# 100-677-01-00_BCB.net
KiCad netlist of a schematic drawn in Altium Designer
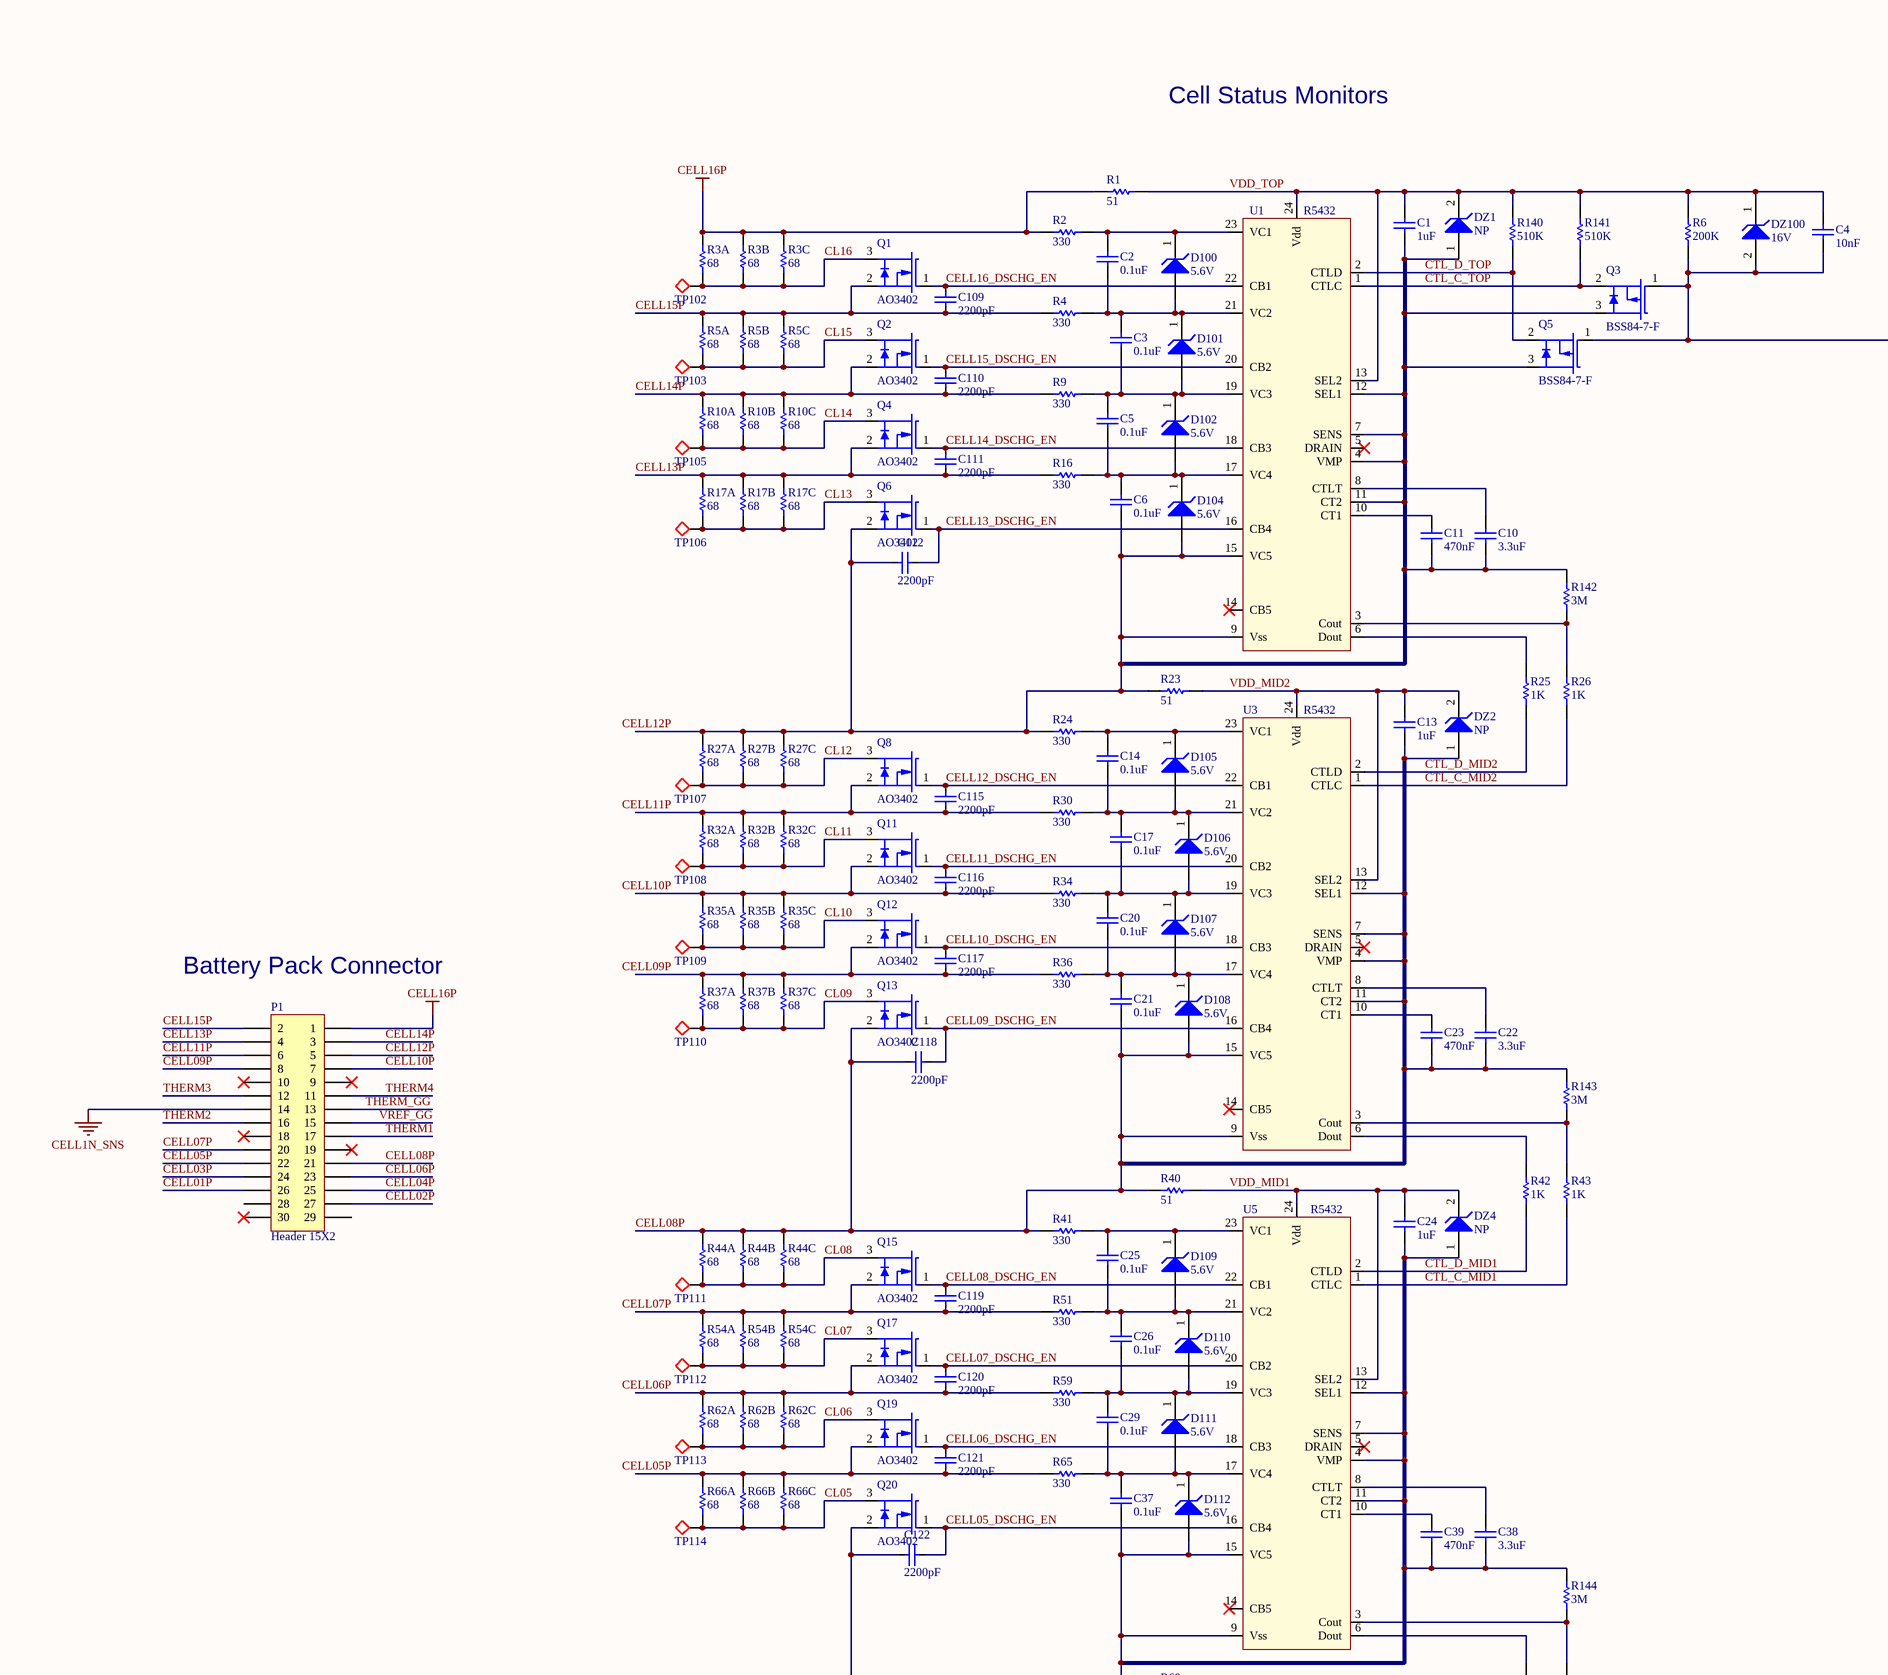
[diagram p0: 100-677-01-00 BCB.SchDoc, top left]
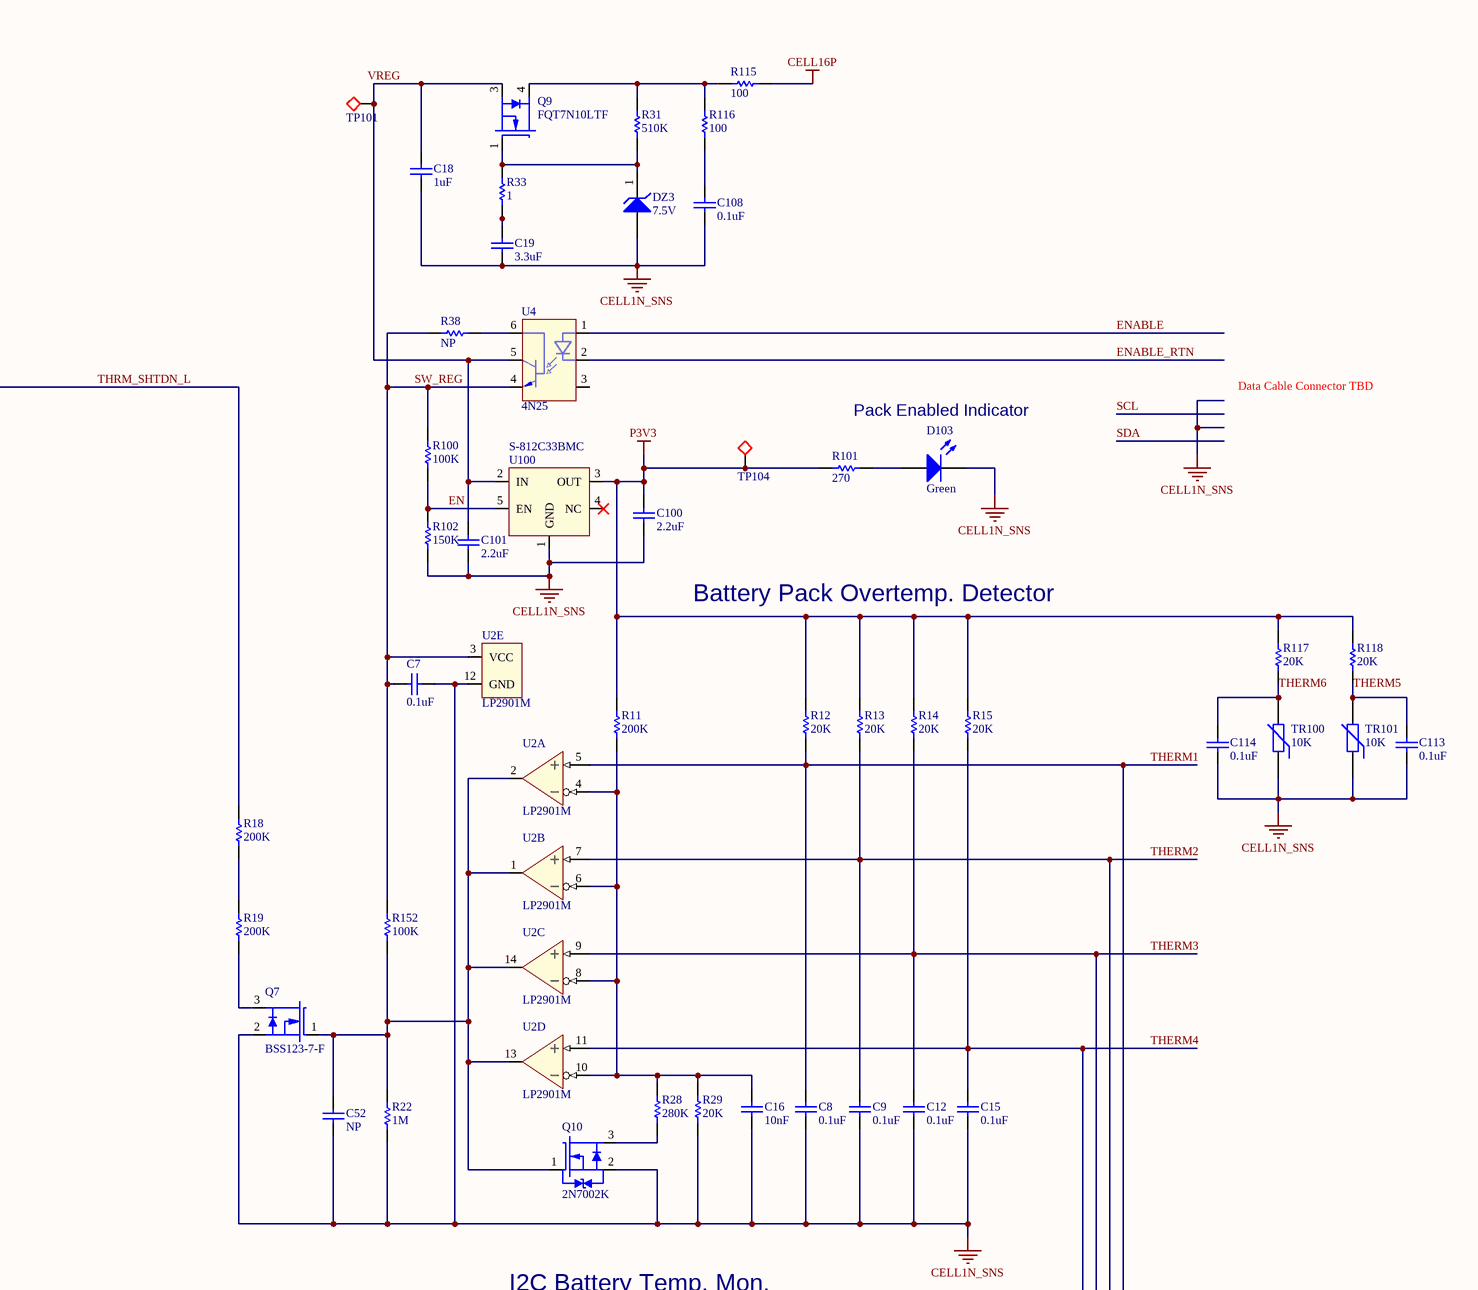
[diagram p1: 100-677-01-00 BCB.SchDoc, top middle]
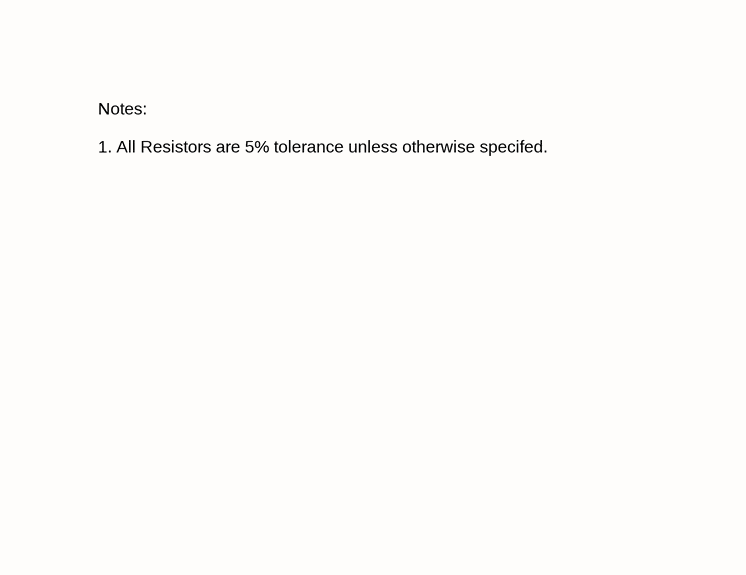
[diagram p2: 100-677-01-00 BCB.SchDoc, top right]
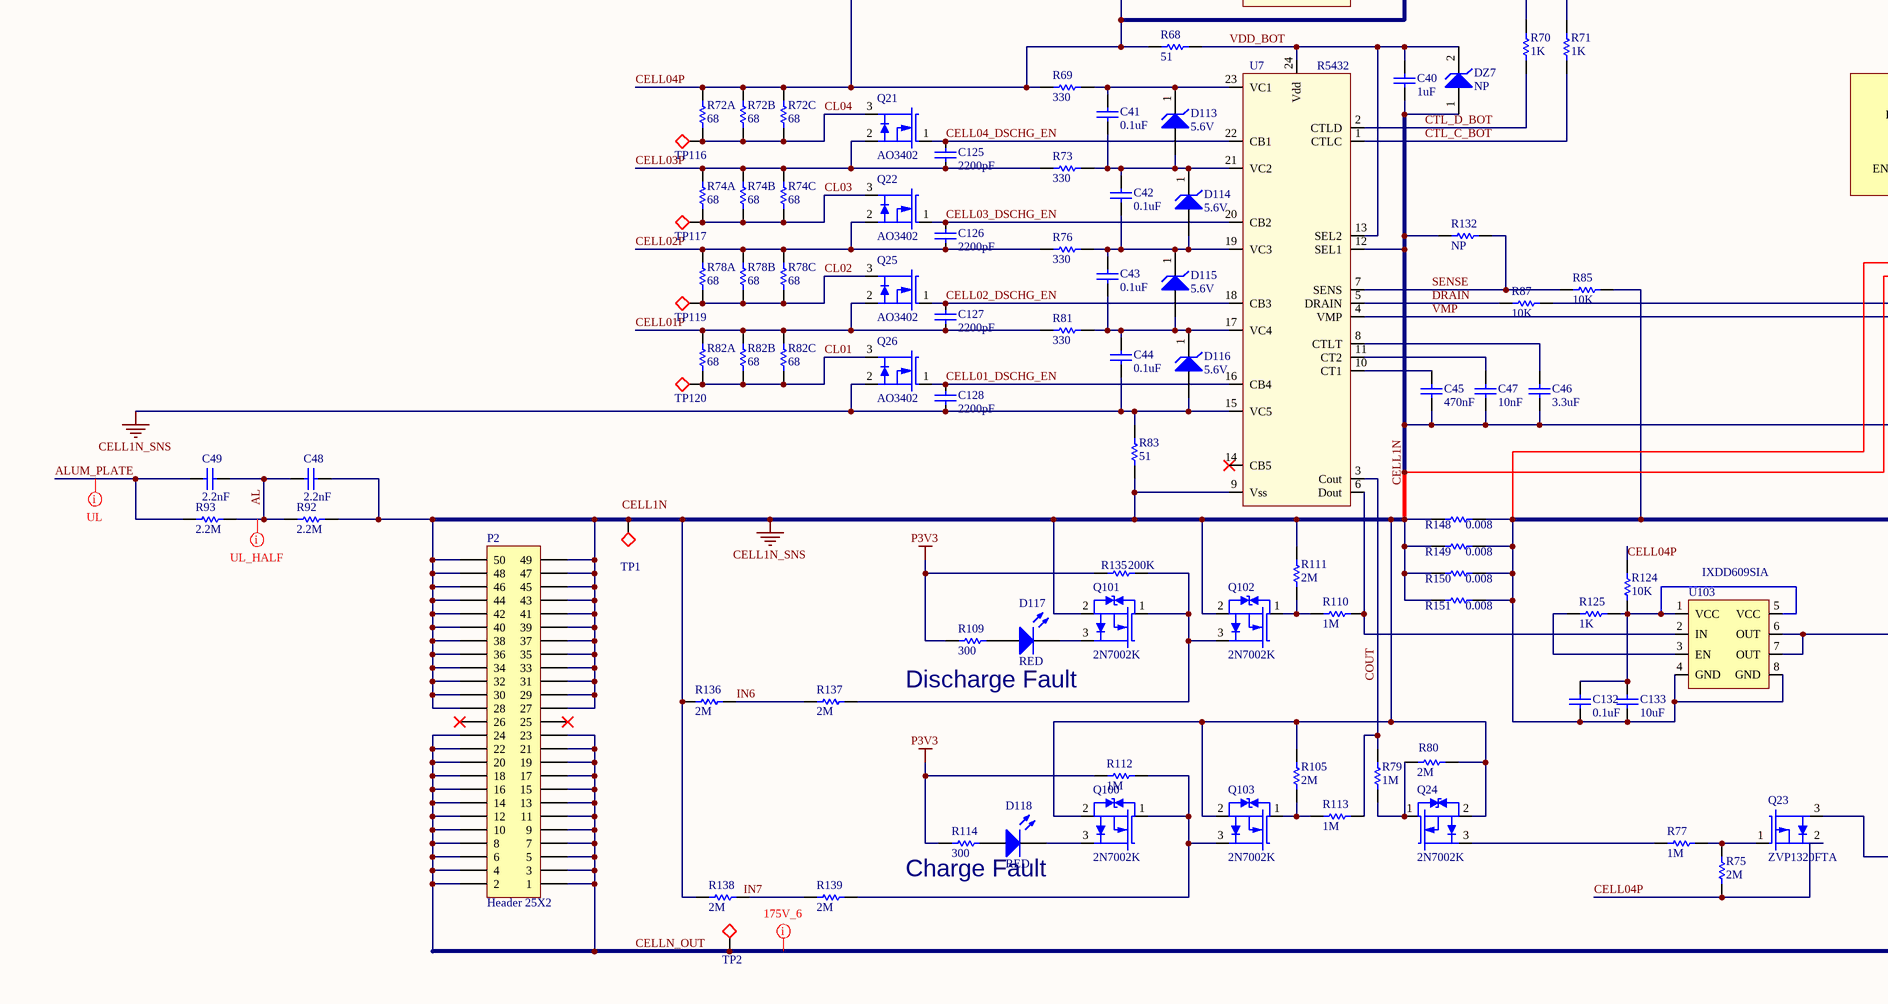
[diagram p3: 100-677-01-00 BCB.SchDoc, bottom left]
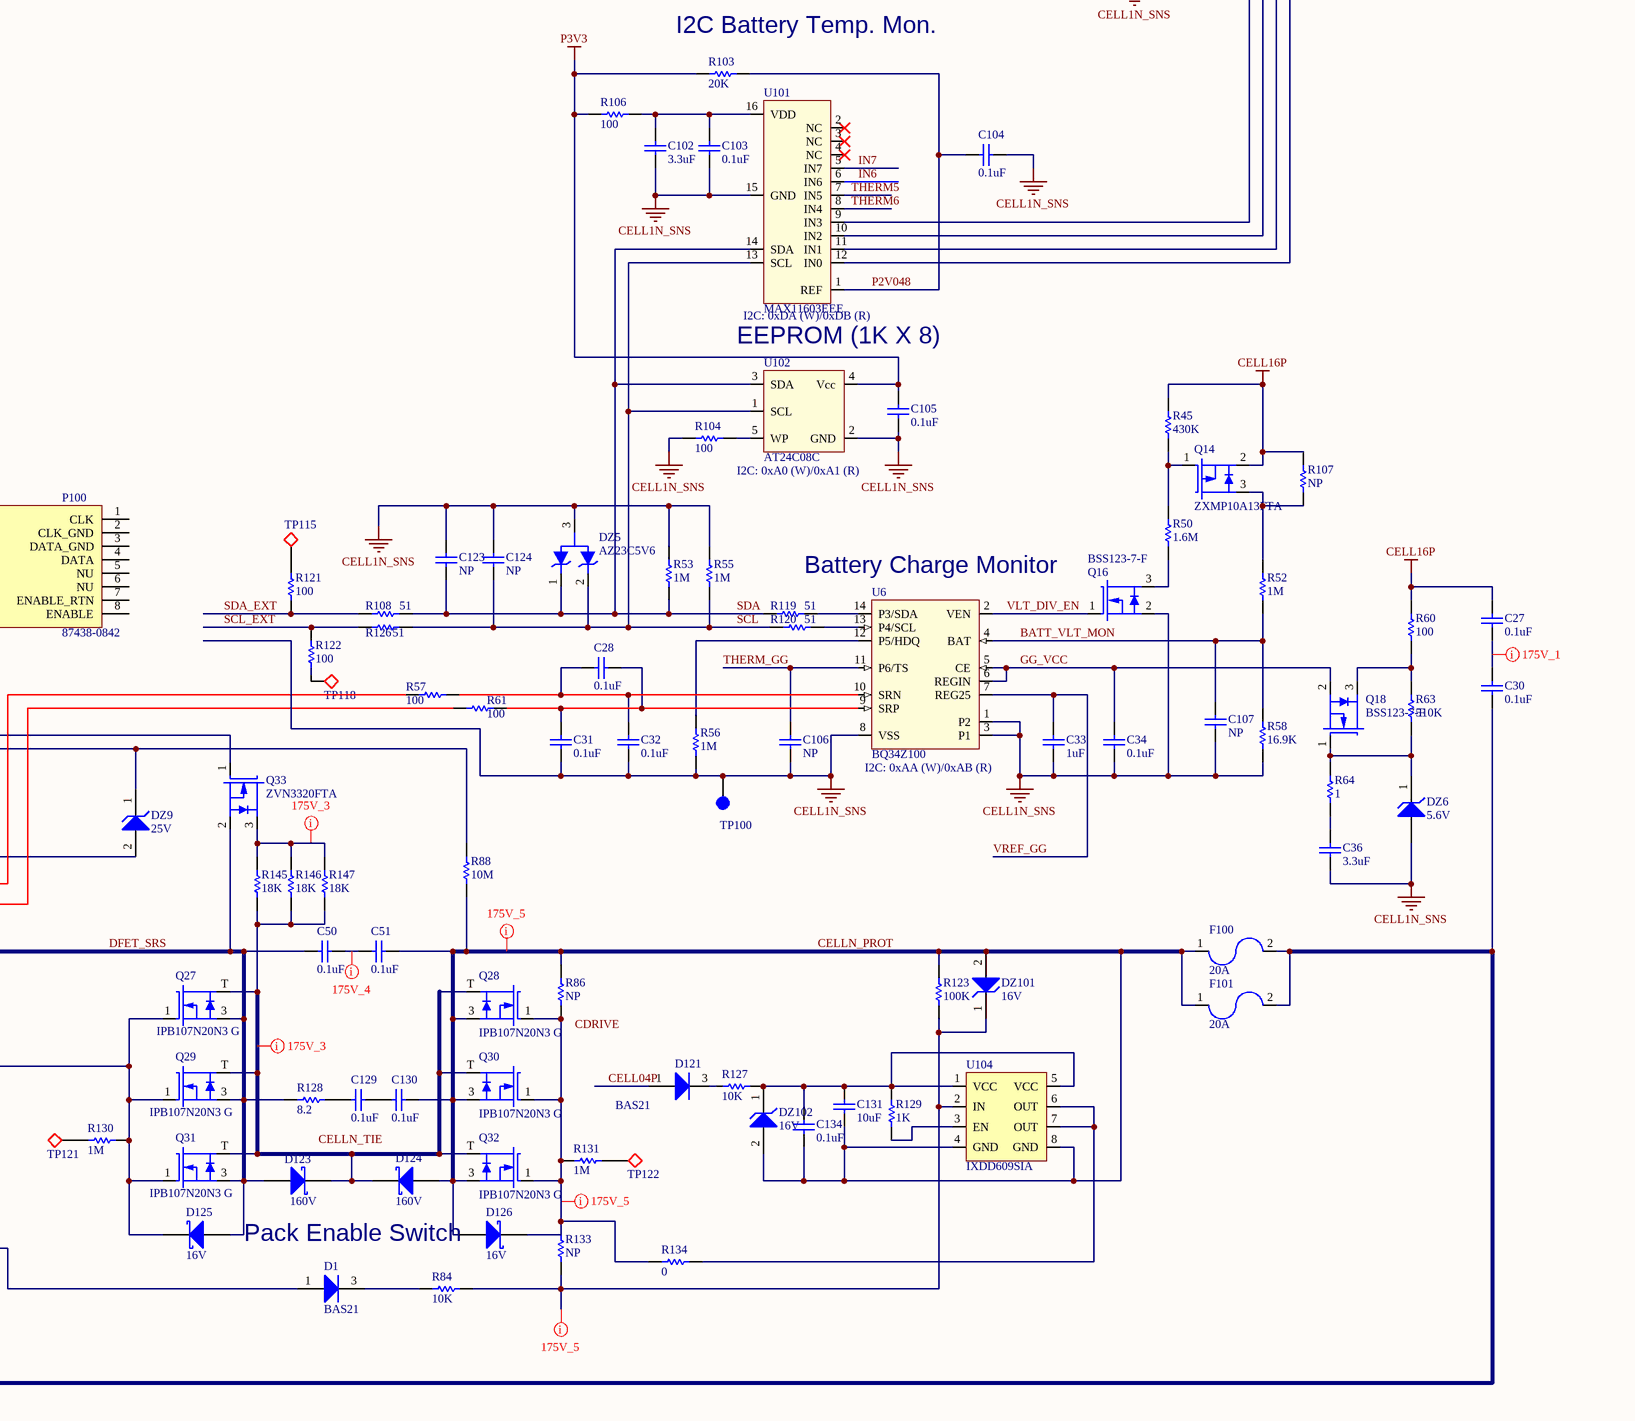
[diagram p4: 100-677-01-00 BCB.SchDoc, bottom middle]

(export (version "E")
  (design (tool "Eeschema 10.0.6"))
  (components
    (comp (ref "C1")
      (value "1uF")
      (footprint "6-0805_N")
      (description "CAP MLCC 1UF 25V X7R 10% SM0805 ROHS")
      (fields
        (field (name "MANUFACTURER") "TDK Corporation")
        (field (name "MANUFACTURER PART NUMBER") "C2012X7R1E105K125AB")
      )
      (libsource (lib "TenergyLibrary") (part "Cap 1uF 0805"))
    )
    (comp (ref "C2")
      (value "0.1uF")
      (footprint "1608[0603]")
      (description "CAP CER 0.1UF 25V 10% X7R 0603")
      (fields (field (name "TOLERANCE") "¡À10%"))
      (libsource (lib "TenergyLibrary") (part "Cap 0.1uF 0603"))
    )
    (comp (ref "C3")
      (value "0.1uF")
      (footprint "1608[0603]")
      (description "CAP CER 0.1UF 25V 10% X7R 0603")
      (fields (field (name "TOLERANCE") "¡À10%"))
      (libsource (lib "TenergyLibrary") (part "Cap 0.1uF 0603"))
    )
    (comp (ref "C4")
      (value "10nF")
      (footprint "1608[0603]")
      (description "CAP MLCC 10NF 25V X7R 10% SM0603 ROHS")
      (fields
        (field (name "MANUFACTURER") "TDK Corporation")
        (field (name "MANUFACTURER PART NUMBER") "C1608X7R1E103K080AA")
      )
      (libsource (lib "TenergyLibrary") (part "Cap 10nF 0603"))
    )
    (comp (ref "C5")
      (value "0.1uF")
      (footprint "1608[0603]")
      (description "CAP CER 0.1UF 25V 10% X7R 0603")
      (fields (field (name "TOLERANCE") "¡À10%"))
      (libsource (lib "TenergyLibrary") (part "Cap 0.1uF 0603"))
    )
    (comp (ref "C6")
      (value "0.1uF")
      (footprint "1608[0603]")
      (description "CAP CER 0.1UF 25V 10% X7R 0603")
      (fields (field (name "TOLERANCE") "¡À10%"))
      (libsource (lib "TenergyLibrary") (part "Cap 0.1uF 0603"))
    )
    (comp (ref "C7")
      (value "0.1uF")
      (footprint "1608[0603]")
      (description "CAP CER 0.1UF 25V 10% X7R 0603")
      (fields (field (name "TOLERANCE") "¡À10%"))
      (libsource (lib "TenergyLibrary") (part "Cap 0.1uF 0603"))
    )
    (comp (ref "C8")
      (value "0.1uF")
      (footprint "1608[0603]")
      (description "CAP CER 0.1UF 25V 10% X7R 0603")
      (fields (field (name "TOLERANCE") "¡À10%"))
      (libsource (lib "TenergyLibrary") (part "Cap 0.1uF 0603"))
    )
    (comp (ref "C9")
      (value "0.1uF")
      (footprint "1608[0603]")
      (description "CAP CER 0.1UF 25V 10% X7R 0603")
      (fields (field (name "TOLERANCE") "¡À10%"))
      (libsource (lib "TenergyLibrary") (part "Cap 0.1uF 0603"))
    )
    (comp (ref "C10")
      (value "3.3uF")
      (footprint "6-0805_M")
      (description "CAP MLCC 3.3UF 16V X5R 20% SM0805 ROHS")
      (fields
        (field (name "MANUFACTURER") "TDK Corporation")
        (field (name "MANUFACTURER PART NUMBER") "C2012X7R1C335K125AB")
      )
      (libsource (lib "TenergyLibrary") (part "Cap 3.3uF 0805"))
    )
    (comp (ref "C11")
      (value "470nF")
      (footprint "1608[0603]")
      (description "CAP MLCC 0.47UF 25V X5R 10% SM0603 ROHS")
      (fields
        (field (name "MANUFACTURER") "TDK Corporation")
        (field (name "MANUFACTURER PART NUMBER") "C1608X5R1E474K080AC")
      )
      (libsource (lib "TenergyLibrary") (part "Cap 0.47uF 0603"))
    )
    (comp (ref "C12")
      (value "0.1uF")
      (footprint "1608[0603]")
      (description "CAP CER 0.1UF 25V 10% X7R 0603")
      (fields (field (name "TOLERANCE") "¡À10%"))
      (libsource (lib "TenergyLibrary") (part "Cap 0.1uF 0603"))
    )
    (comp (ref "C13")
      (value "1uF")
      (footprint "6-0805_N")
      (description "CAP MLCC 1UF 25V X7R 10% SM0805 ROHS")
      (fields
        (field (name "MANUFACTURER") "TDK Corporation")
        (field (name "MANUFACTURER PART NUMBER") "C2012X7R1E105K125AB")
      )
      (libsource (lib "TenergyLibrary") (part "Cap 1uF 0805"))
    )
    (comp (ref "C14")
      (value "0.1uF")
      (footprint "1608[0603]")
      (description "CAP CER 0.1UF 25V 10% X7R 0603")
      (fields (field (name "TOLERANCE") "¡À10%"))
      (libsource (lib "TenergyLibrary") (part "Cap 0.1uF 0603"))
    )
    (comp (ref "C15")
      (value "0.1uF")
      (footprint "1608[0603]")
      (description "CAP CER 0.1UF 25V 10% X7R 0603")
      (fields (field (name "TOLERANCE") "¡À10%"))
      (libsource (lib "TenergyLibrary") (part "Cap 0.1uF 0603"))
    )
    (comp (ref "C16")
      (value "10nF")
      (footprint "1608[0603]")
      (description "CAP MLCC 10NF 25V X7R 10% SM0603 ROHS")
      (fields
        (field (name "MANUFACTURER") "TDK Corporation")
        (field (name "MANUFACTURER PART NUMBER") "C1608X7R1E103K080AA")
      )
      (libsource (lib "TenergyLibrary") (part "Cap 10nF 0603"))
    )
    (comp (ref "C17")
      (value "0.1uF")
      (footprint "1608[0603]")
      (description "CAP CER 0.1UF 25V 10% X7R 0603")
      (fields (field (name "TOLERANCE") "¡À10%"))
      (libsource (lib "TenergyLibrary") (part "Cap 0.1uF 0603"))
    )
    (comp (ref "C18")
      (value "1uF")
      (footprint "1608[0603]")
      (description "CAP, CERAMIC, 1UF, 16V, X7R, 0603")
      (libsource (lib "TenergyLibrary") (part "Cap 1uF 0603"))
    )
    (comp (ref "C19")
      (value "3.3uF")
      (footprint "6-0805_M")
      (description "CAP MLCC 3.3UF 16V X5R 20% SM0805 ROHS")
      (fields
        (field (name "MANUFACTURER") "TDK Corporation")
        (field (name "MANUFACTURER PART NUMBER") "C2012X7R1C335K125AB")
      )
      (libsource (lib "TenergyLibrary") (part "Cap 3.3uF 0805"))
    )
    (comp (ref "C20")
      (value "0.1uF")
      (footprint "1608[0603]")
      (description "CAP CER 0.1UF 25V 10% X7R 0603")
      (fields (field (name "TOLERANCE") "¡À10%"))
      (libsource (lib "TenergyLibrary") (part "Cap 0.1uF 0603"))
    )
    (comp (ref "C21")
      (value "0.1uF")
      (footprint "1608[0603]")
      (description "CAP CER 0.1UF 25V 10% X7R 0603")
      (fields (field (name "TOLERANCE") "¡À10%"))
      (libsource (lib "TenergyLibrary") (part "Cap 0.1uF 0603"))
    )
    (comp (ref "C22")
      (value "3.3uF")
      (footprint "6-0805_M")
      (description "CAP MLCC 3.3UF 16V X5R 20% SM0805 ROHS")
      (fields
        (field (name "MANUFACTURER") "TDK Corporation")
        (field (name "MANUFACTURER PART NUMBER") "C2012X7R1C335K125AB")
      )
      (libsource (lib "TenergyLibrary") (part "Cap 3.3uF 0805"))
    )
    (comp (ref "C23")
      (value "470nF")
      (footprint "1608[0603]")
      (description "CAP MLCC 0.47UF 25V X5R 10% SM0603 ROHS")
      (fields
        (field (name "MANUFACTURER") "TDK Corporation")
        (field (name "MANUFACTURER PART NUMBER") "C1608X5R1E474K080AC")
      )
      (libsource (lib "TenergyLibrary") (part "Cap 0.47uF 0603"))
    )
    (comp (ref "C24")
      (value "1uF")
      (footprint "6-0805_N")
      (description "CAP MLCC 1UF 25V X7R 10% SM0805 ROHS")
      (fields
        (field (name "MANUFACTURER") "TDK Corporation")
        (field (name "MANUFACTURER PART NUMBER") "C2012X7R1E105K125AB")
      )
      (libsource (lib "TenergyLibrary") (part "Cap 1uF 0805"))
    )
    (comp (ref "C25")
      (value "0.1uF")
      (footprint "1608[0603]")
      (description "CAP CER 0.1UF 25V 10% X7R 0603")
      (fields (field (name "TOLERANCE") "¡À10%"))
      (libsource (lib "TenergyLibrary") (part "Cap 0.1uF 0603"))
    )
    (comp (ref "C26")
      (value "0.1uF")
      (footprint "1608[0603]")
      (description "CAP CER 0.1UF 25V 10% X7R 0603")
      (fields (field (name "TOLERANCE") "¡À10%"))
      (libsource (lib "TenergyLibrary") (part "Cap 0.1uF 0603"))
    )
    (comp (ref "C27")
      (value "0.1uF")
      (footprint "C1206")
      (description "CAP MLCC 0.1UF 250V 10% X7R 1206")
      (fields
        (field (name "MANUFACTURER") "TDK Corporation")
        (field (name "MANUFACTURER PART NUMBER") "C3216X7R2E104K160AA")
      )
      (libsource (lib "TenergyLibrary") (part "Cap 0.1uF 1206"))
    )
    (comp (ref "C28")
      (value "0.1uF")
      (footprint "1608[0603]")
      (description "CAP CER 0.1UF 25V 10% X7R 0603")
      (fields (field (name "TOLERANCE") "¡À10%"))
      (libsource (lib "TenergyLibrary") (part "Cap 0.1uF 0603"))
    )
    (comp (ref "C29")
      (value "0.1uF")
      (footprint "1608[0603]")
      (description "CAP CER 0.1UF 25V 10% X7R 0603")
      (fields (field (name "TOLERANCE") "¡À10%"))
      (libsource (lib "TenergyLibrary") (part "Cap 0.1uF 0603"))
    )
    (comp (ref "C30")
      (value "0.1uF")
      (footprint "C1206")
      (description "CAP MLCC 0.1UF 250V 10% X7R 1206")
      (fields
        (field (name "MANUFACTURER") "TDK Corporation")
        (field (name "MANUFACTURER PART NUMBER") "C3216X7R2E104K160AA")
      )
      (libsource (lib "TenergyLibrary") (part "Cap 0.1uF 1206"))
    )
    (comp (ref "C31")
      (value "0.1uF")
      (footprint "1608[0603]")
      (description "CAP CER 0.1UF 25V 10% X7R 0603")
      (fields (field (name "TOLERANCE") "¡À10%"))
      (libsource (lib "TenergyLibrary") (part "Cap 0.1uF 0603"))
    )
    (comp (ref "C32")
      (value "0.1uF")
      (footprint "1608[0603]")
      (description "CAP CER 0.1UF 25V 10% X7R 0603")
      (fields (field (name "TOLERANCE") "¡À10%"))
      (libsource (lib "TenergyLibrary") (part "Cap 0.1uF 0603"))
    )
    (comp (ref "C33")
      (value "1uF")
      (footprint "6-0805_N")
      (description "CAP MLCC 1UF 25V X7R 10% SM0805 ROHS")
      (fields
        (field (name "MANUFACTURER") "TDK Corporation")
        (field (name "MANUFACTURER PART NUMBER") "C2012X7R1E105K125AB")
      )
      (libsource (lib "TenergyLibrary") (part "Cap 1uF 0805"))
    )
    (comp (ref "C34")
      (value "0.1uF")
      (footprint "1608[0603]")
      (description "CAP CER 0.1UF 25V 10% X7R 0603")
      (fields (field (name "TOLERANCE") "¡À10%"))
      (libsource (lib "TenergyLibrary") (part "Cap 0.1uF 0603"))
    )
    (comp (ref "C36")
      (value "3.3uF")
      (footprint "6-0805_M")
      (description "CAP MLCC 3.3UF 16V X5R 20% SM0805 ROHS")
      (fields
        (field (name "MANUFACTURER") "TDK Corporation")
        (field (name "MANUFACTURER PART NUMBER") "C2012X7R1C335K125AB")
      )
      (libsource (lib "TenergyLibrary") (part "Cap 3.3uF 0805"))
    )
    (comp (ref "C37")
      (value "0.1uF")
      (footprint "1608[0603]")
      (description "CAP CER 0.1UF 25V 10% X7R 0603")
      (fields (field (name "TOLERANCE") "¡À10%"))
      (libsource (lib "TenergyLibrary") (part "Cap 0.1uF 0603"))
    )
    (comp (ref "C38")
      (value "3.3uF")
      (footprint "6-0805_M")
      (description "CAP MLCC 3.3UF 16V X5R 20% SM0805 ROHS")
      (fields
        (field (name "MANUFACTURER") "TDK Corporation")
        (field (name "MANUFACTURER PART NUMBER") "C2012X7R1C335K125AB")
      )
      (libsource (lib "TenergyLibrary") (part "Cap 3.3uF 0805"))
    )
    (comp (ref "C39")
      (value "470nF")
      (footprint "1608[0603]")
      (description "CAP MLCC 0.47UF 25V X5R 10% SM0603 ROHS")
      (fields
        (field (name "MANUFACTURER") "TDK Corporation")
        (field (name "MANUFACTURER PART NUMBER") "C1608X5R1E474K080AC")
      )
      (libsource (lib "TenergyLibrary") (part "Cap 0.47uF 0603"))
    )
    (comp (ref "C40")
      (value "1uF")
      (footprint "6-0805_N")
      (description "CAP MLCC 1UF 25V X7R 10% SM0805 ROHS")
      (fields
        (field (name "MANUFACTURER") "TDK Corporation")
        (field (name "MANUFACTURER PART NUMBER") "C2012X7R1E105K125AB")
      )
      (libsource (lib "TenergyLibrary") (part "Cap 1uF 0805"))
    )
    (comp (ref "C41")
      (value "0.1uF")
      (footprint "1608[0603]")
      (description "CAP CER 0.1UF 25V 10% X7R 0603")
      (fields (field (name "TOLERANCE") "¡À10%"))
      (libsource (lib "TenergyLibrary") (part "Cap 0.1uF 0603"))
    )
    (comp (ref "C42")
      (value "0.1uF")
      (footprint "1608[0603]")
      (description "CAP CER 0.1UF 25V 10% X7R 0603")
      (fields (field (name "TOLERANCE") "¡À10%"))
      (libsource (lib "TenergyLibrary") (part "Cap 0.1uF 0603"))
    )
    (comp (ref "C43")
      (value "0.1uF")
      (footprint "1608[0603]")
      (description "CAP CER 0.1UF 25V 10% X7R 0603")
      (fields (field (name "TOLERANCE") "¡À10%"))
      (libsource (lib "TenergyLibrary") (part "Cap 0.1uF 0603"))
    )
    (comp (ref "C44")
      (value "0.1uF")
      (footprint "1608[0603]")
      (description "CAP CER 0.1UF 25V 10% X7R 0603")
      (fields (field (name "TOLERANCE") "¡À10%"))
      (libsource (lib "TenergyLibrary") (part "Cap 0.1uF 0603"))
    )
    (comp (ref "C45")
      (value "470nF")
      (footprint "1608[0603]")
      (description "CAP MLCC 0.47UF 25V X5R 10% SM0603 ROHS")
      (fields
        (field (name "MANUFACTURER") "TDK Corporation")
        (field (name "MANUFACTURER PART NUMBER") "C1608X5R1E474K080AC")
      )
      (libsource (lib "TenergyLibrary") (part "Cap 0.47uF 0603"))
    )
    (comp (ref "C46")
      (value "3.3uF")
      (footprint "6-0805_M")
      (description "CAP MLCC 3.3UF 16V X5R 20% SM0805 ROHS")
      (fields
        (field (name "MANUFACTURER") "TDK Corporation")
        (field (name "MANUFACTURER PART NUMBER") "C2012X7R1C335K125AB")
      )
      (libsource (lib "TenergyLibrary") (part "Cap 3.3uF 0805"))
    )
    (comp (ref "C47")
      (value "10nF")
      (footprint "1608[0603]")
      (description "CAP MLCC 10NF 25V X7R 10% SM0603 ROHS")
      (fields
        (field (name "MANUFACTURER") "TDK Corporation")
        (field (name "MANUFACTURER PART NUMBER") "C1608X7R1E103K080AA")
      )
      (libsource (lib "TenergyLibrary") (part "Cap 10nF 0603"))
    )
    (comp (ref "C48")
      (value "2.2nF")
      (footprint "1812")
      (description "CAP MLCC 2.2NF 2KV 10% SM1812 ROHS")
      (fields
        (field (name "MANUFACTURER") "TDK Corporation")
        (field (name "MANUFACTURER PART NUMBER") "C4532X7R3D222K130KA")
      )
      (libsource (lib "TenergyLibrary") (part "Cap 2.2nF 1812"))
    )
    (comp (ref "C49")
      (value "2.2nF")
      (footprint "1812")
      (description "CAP MLCC 2.2NF 2KV 10% SM1812 ROHS")
      (fields
        (field (name "MANUFACTURER") "TDK Corporation")
        (field (name "MANUFACTURER PART NUMBER") "C4532X7R3D222K130KA")
      )
      (libsource (lib "TenergyLibrary") (part "Cap 2.2nF 1812"))
    )
    (comp (ref "C50")
      (value "0.1uF")
      (footprint "C1206")
      (description "CAP MLCC 0.1UF 250V 10% X7R 1206")
      (fields
        (field (name "MANUFACTURER") "TDK Corporation")
        (field (name "MANUFACTURER PART NUMBER") "C3216X7R2E104K160AA")
      )
      (libsource (lib "TenergyLibrary") (part "Cap 0.1uF 1206"))
    )
    (comp (ref "C51")
      (value "0.1uF")
      (footprint "C1206")
      (description "CAP MLCC 0.1UF 250V 10% X7R 1206")
      (fields
        (field (name "MANUFACTURER") "TDK Corporation")
        (field (name "MANUFACTURER PART NUMBER") "C3216X7R2E104K160AA")
      )
      (libsource (lib "TenergyLibrary") (part "Cap 0.1uF 1206"))
    )
    (comp (ref "C52")
      (value "NP")
      (footprint "1608[0603]")
      (description "Do not Populate")
      (libsource (lib "TenergyLibrary") (part "Cap NP 0603"))
    )
    (comp (ref "C100")
      (value "2.2uF")
      (footprint "6-0805_M")
      (description "CAP CER 2.2UF 6.3V 20% X5R 0805")
      (fields
        (field (name "TOLERANCE") "¡À20%")
        (field (name "MANUFACTURER PART NUMBER") "C2012X5R0J225M085AA")
      )
      (libsource (lib "TenergyLibrary") (part "Cap 2.2uF 0805"))
    )
    (comp (ref "C101")
      (value "2.2uF")
      (footprint "6-0805_M")
      (description "CAP CER 2.2UF 6.3V 20% X5R 0805")
      (fields
        (field (name "TOLERANCE") "¡À20%")
        (field (name "MANUFACTURER PART NUMBER") "C2012X5R0J225M085AA")
      )
      (libsource (lib "TenergyLibrary") (part "Cap 2.2uF 0805"))
    )
    (comp (ref "C102")
      (value "3.3uF")
      (footprint "6-0805_M")
      (description "CAP MLCC 3.3UF 16V X5R 20% SM0805 ROHS")
      (fields
        (field (name "MANUFACTURER") "TDK Corporation")
        (field (name "MANUFACTURER PART NUMBER") "C2012X7R1C335K125AB")
      )
      (libsource (lib "TenergyLibrary") (part "Cap 3.3uF 0805"))
    )
    (comp (ref "C103")
      (value "0.1uF")
      (footprint "1608[0603]")
      (description "CAP CER 0.1UF 25V 10% X7R 0603")
      (fields (field (name "TOLERANCE") "¡À10%"))
      (libsource (lib "TenergyLibrary") (part "Cap 0.1uF 0603"))
    )
    (comp (ref "C104")
      (value "0.1uF")
      (footprint "1608[0603]")
      (description "CAP CER 0.1UF 25V 10% X7R 0603")
      (fields (field (name "TOLERANCE") "¡À10%"))
      (libsource (lib "TenergyLibrary") (part "Cap 0.1uF 0603"))
    )
    (comp (ref "C105")
      (value "0.1uF")
      (footprint "1608[0603]")
      (description "CAP CER 0.1UF 25V 10% X7R 0603")
      (fields (field (name "TOLERANCE") "¡À10%"))
      (libsource (lib "TenergyLibrary") (part "Cap 0.1uF 0603"))
    )
    (comp (ref "C106")
      (value "NP")
      (footprint "1608[0603]")
      (description "Do not Populate")
      (libsource (lib "TenergyLibrary") (part "Cap NP 0603"))
    )
    (comp (ref "C107")
      (value "NP")
      (footprint "1608[0603]")
      (description "Do not Populate")
      (libsource (lib "TenergyLibrary") (part "Cap NP 0603"))
    )
    (comp (ref "C108")
      (value "0.1uF")
      (footprint "1608[0603]")
      (description "CAP CER 0.1UF 25V 10% X7R 0603")
      (fields (field (name "TOLERANCE") "¡À10%"))
      (libsource (lib "TenergyLibrary") (part "Cap 0.1uF 0603"))
    )
    (comp (ref "C109")
      (value "2200pF")
      (footprint "1608[0603]")
      (description "ACap 2200PF 100V, X7R, 10%, 0603")
      (fields (field (name "MANUFACTURER PART NUMBER") "06031C222KAT2A"))
      (libsource (lib "TenergyLibrary") (part "Cap 2200pF 0603"))
    )
    (comp (ref "C110")
      (value "2200pF")
      (footprint "1608[0603]")
      (description "ACap 2200PF 100V, X7R, 10%, 0603")
      (fields (field (name "MANUFACTURER PART NUMBER") "06031C222KAT2A"))
      (libsource (lib "TenergyLibrary") (part "Cap 2200pF 0603"))
    )
    (comp (ref "C111")
      (value "2200pF")
      (footprint "1608[0603]")
      (description "ACap 2200PF 100V, X7R, 10%, 0603")
      (fields (field (name "MANUFACTURER PART NUMBER") "06031C222KAT2A"))
      (libsource (lib "TenergyLibrary") (part "Cap 2200pF 0603"))
    )
    (comp (ref "C112")
      (value "2200pF")
      (footprint "1608[0603]")
      (description "ACap 2200PF 100V, X7R, 10%, 0603")
      (fields (field (name "MANUFACTURER PART NUMBER") "06031C222KAT2A"))
      (libsource (lib "TenergyLibrary") (part "Cap 2200pF 0603"))
    )
    (comp (ref "C113")
      (value "0.1uF")
      (footprint "1608[0603]")
      (description "CAP CER 0.1UF 25V 10% X7R 0603")
      (fields (field (name "TOLERANCE") "¡À10%"))
      (libsource (lib "TenergyLibrary") (part "Cap 0.1uF 0603"))
    )
    (comp (ref "C114")
      (value "0.1uF")
      (footprint "1608[0603]")
      (description "CAP CER 0.1UF 25V 10% X7R 0603")
      (fields (field (name "TOLERANCE") "¡À10%"))
      (libsource (lib "TenergyLibrary") (part "Cap 0.1uF 0603"))
    )
    (comp (ref "C115")
      (value "2200pF")
      (footprint "1608[0603]")
      (description "ACap 2200PF 100V, X7R, 10%, 0603")
      (fields (field (name "MANUFACTURER PART NUMBER") "06031C222KAT2A"))
      (libsource (lib "TenergyLibrary") (part "Cap 2200pF 0603"))
    )
    (comp (ref "C116")
      (value "2200pF")
      (footprint "1608[0603]")
      (description "ACap 2200PF 100V, X7R, 10%, 0603")
      (fields (field (name "MANUFACTURER PART NUMBER") "06031C222KAT2A"))
      (libsource (lib "TenergyLibrary") (part "Cap 2200pF 0603"))
    )
    (comp (ref "C117")
      (value "2200pF")
      (footprint "1608[0603]")
      (description "ACap 2200PF 100V, X7R, 10%, 0603")
      (fields (field (name "MANUFACTURER PART NUMBER") "06031C222KAT2A"))
      (libsource (lib "TenergyLibrary") (part "Cap 2200pF 0603"))
    )
    (comp (ref "C118")
      (value "2200pF")
      (footprint "1608[0603]")
      (description "ACap 2200PF 100V, X7R, 10%, 0603")
      (fields (field (name "MANUFACTURER PART NUMBER") "06031C222KAT2A"))
      (libsource (lib "TenergyLibrary") (part "Cap 2200pF 0603"))
    )
    (comp (ref "C119")
      (value "2200pF")
      (footprint "1608[0603]")
      (description "ACap 2200PF 100V, X7R, 10%, 0603")
      (fields (field (name "MANUFACTURER PART NUMBER") "06031C222KAT2A"))
      (libsource (lib "TenergyLibrary") (part "Cap 2200pF 0603"))
    )
    (comp (ref "C120")
      (value "2200pF")
      (footprint "1608[0603]")
      (description "ACap 2200PF 100V, X7R, 10%, 0603")
      (fields (field (name "MANUFACTURER PART NUMBER") "06031C222KAT2A"))
      (libsource (lib "TenergyLibrary") (part "Cap 2200pF 0603"))
    )
    (comp (ref "C121")
      (value "2200pF")
      (footprint "1608[0603]")
      (description "ACap 2200PF 100V, X7R, 10%, 0603")
      (fields (field (name "MANUFACTURER PART NUMBER") "06031C222KAT2A"))
      (libsource (lib "TenergyLibrary") (part "Cap 2200pF 0603"))
    )
    (comp (ref "C122")
      (value "2200pF")
      (footprint "1608[0603]")
      (description "ACap 2200PF 100V, X7R, 10%, 0603")
      (fields (field (name "MANUFACTURER PART NUMBER") "06031C222KAT2A"))
      (libsource (lib "TenergyLibrary") (part "Cap 2200pF 0603"))
    )
    (comp (ref "C123")
      (value "NP")
      (footprint "1608[0603]")
      (description "Do not Populate")
      (libsource (lib "TenergyLibrary") (part "Cap NP 0603"))
    )
    (comp (ref "C124")
      (value "NP")
      (footprint "1608[0603]")
      (description "Do not Populate")
      (libsource (lib "TenergyLibrary") (part "Cap NP 0603"))
    )
    (comp (ref "C125")
      (value "2200pF")
      (footprint "1608[0603]")
      (description "ACap 2200PF 100V, X7R, 10%, 0603")
      (fields (field (name "MANUFACTURER PART NUMBER") "06031C222KAT2A"))
      (libsource (lib "TenergyLibrary") (part "Cap 2200pF 0603"))
    )
    (comp (ref "C126")
      (value "2200pF")
      (footprint "1608[0603]")
      (description "ACap 2200PF 100V, X7R, 10%, 0603")
      (fields (field (name "MANUFACTURER PART NUMBER") "06031C222KAT2A"))
      (libsource (lib "TenergyLibrary") (part "Cap 2200pF 0603"))
    )
    (comp (ref "C127")
      (value "2200pF")
      (footprint "1608[0603]")
      (description "ACap 2200PF 100V, X7R, 10%, 0603")
      (fields (field (name "MANUFACTURER PART NUMBER") "06031C222KAT2A"))
      (libsource (lib "TenergyLibrary") (part "Cap 2200pF 0603"))
    )
    (comp (ref "C128")
      (value "2200pF")
      (footprint "1608[0603]")
      (description "ACap 2200PF 100V, X7R, 10%, 0603")
      (fields (field (name "MANUFACTURER PART NUMBER") "06031C222KAT2A"))
      (libsource (lib "TenergyLibrary") (part "Cap 2200pF 0603"))
    )
    (comp (ref "C129")
      (value "0.1uF")
      (footprint "C1206")
      (description "CAP MLCC 0.1UF 250V 10% X7R 1206")
      (fields (field (name "MANUFACTURER") "TDK Corporation") (field (name "TOLERANCE") "?0%"))
      (libsource (lib "TenergyLibrary") (part "Cap 0.1uF 1206"))
    )
    (comp (ref "C130")
      (value "0.1uF")
      (footprint "C1206")
      (description "CAP MLCC 0.1UF 250V 10% X7R 1206")
      (fields (field (name "MANUFACTURER") "TDK Corporation") (field (name "TOLERANCE") "?0%"))
      (libsource (lib "TenergyLibrary") (part "Cap 0.1uF 1206"))
    )
    (comp (ref "C131")
      (value "10uF")
      (footprint "C1206")
      (description "CAP CER 10UF 25V 10% X5R 1206")
      (fields (field (name "TOLERANCE") "¡À10%") (field (name "MANUFACTURER PART NUMBER") "C1206C106K3PACTU"))
      (libsource (lib "TenergyLibrary") (part "Cap 10uF 1206"))
    )
    (comp (ref "C132")
      (value "0.1uF")
      (footprint "1608[0603]")
      (description "CAP CER 0.1UF 25V 10% X7R 0603")
      (fields (field (name "TOLERANCE") "¡À10%"))
      (libsource (lib "TenergyLibrary") (part "Cap 0.1uF 0603"))
    )
    (comp (ref "C133")
      (value "10uF")
      (footprint "C1206")
      (description "CAP CER 10UF 25V 10% X5R 1206")
      (fields (field (name "TOLERANCE") "¡À10%") (field (name "MANUFACTURER PART NUMBER") "C1206C106K3PACTU"))
      (libsource (lib "TenergyLibrary") (part "Cap 10uF 1206"))
    )
    (comp (ref "C134")
      (value "0.1uF")
      (footprint "1608[0603]")
      (description "CAP CER 0.1UF 25V 10% X7R 0603")
      (fields (field (name "TOLERANCE") "¡À10%"))
      (libsource (lib "TenergyLibrary") (part "Cap 0.1uF 0603"))
    )
    (comp (ref "D1")
      (value "BAS21")
      (footprint "SOT23_N")
      (description "DIODE, 200mA, 250V, SOT-23")
      (libsource (lib "TenergyLibrary") (part "Diode Standard SOT-23"))
    )
    (comp (ref "D100")
      (value "5.6V")
      (footprint "BZT52H (SOD123F)")
      (description "DIODE ZENER 5.6V 500MW SOD-123")
      (fields (field (name "MANUFACTURER PART NUMBER") "MMSZ4690T1G") (field (name "TOLERANCE") "±5%"))
      (libsource (lib "TenergyLibrary") (part "Diode Zener 5.6V SOD123"))
    )
    (comp (ref "D101")
      (value "5.6V")
      (footprint "BZT52H (SOD123F)")
      (description "DIODE ZENER 5.6V 500MW SOD-123")
      (fields (field (name "MANUFACTURER PART NUMBER") "MMSZ4690T1G") (field (name "TOLERANCE") "±5%"))
      (libsource (lib "TenergyLibrary") (part "Diode Zener 5.6V SOD123"))
    )
    (comp (ref "D102")
      (value "5.6V")
      (footprint "BZT52H (SOD123F)")
      (description "DIODE ZENER 5.6V 500MW SOD-123")
      (fields (field (name "MANUFACTURER PART NUMBER") "MMSZ4690T1G") (field (name "TOLERANCE") "±5%"))
      (libsource (lib "TenergyLibrary") (part "Diode Zener 5.6V SOD123"))
    )
    (comp (ref "D103")
      (value "Green")
      (footprint "LED SM REVERSE-GRN")
      (description "LED YELLOW-GREEN CLR 572NM 1206")
      (fields (field (name "MANUFACTURER PART NUMBER") "597-6501-607F"))
      (libsource (lib "TenergyLibrary") (part "LED Green"))
    )
    (comp (ref "D104")
      (value "5.6V")
      (footprint "BZT52H (SOD123F)")
      (description "DIODE ZENER 5.6V 500MW SOD-123")
      (fields (field (name "MANUFACTURER PART NUMBER") "MMSZ4690T1G") (field (name "TOLERANCE") "±5%"))
      (libsource (lib "TenergyLibrary") (part "Diode Zener 5.6V SOD123"))
    )
    (comp (ref "D105")
      (value "5.6V")
      (footprint "BZT52H (SOD123F)")
      (description "DIODE ZENER 5.6V 500MW SOD-123")
      (fields (field (name "MANUFACTURER PART NUMBER") "MMSZ4690T1G") (field (name "TOLERANCE") "±5%"))
      (libsource (lib "TenergyLibrary") (part "Diode Zener 5.6V SOD123"))
    )
    (comp (ref "D106")
      (value "5.6V")
      (footprint "BZT52H (SOD123F)")
      (description "DIODE ZENER 5.6V 500MW SOD-123")
      (fields (field (name "MANUFACTURER PART NUMBER") "MMSZ4690T1G") (field (name "TOLERANCE") "±5%"))
      (libsource (lib "TenergyLibrary") (part "Diode Zener 5.6V SOD123"))
    )
    (comp (ref "D107")
      (value "5.6V")
      (footprint "BZT52H (SOD123F)")
      (description "DIODE ZENER 5.6V 500MW SOD-123")
      (fields (field (name "MANUFACTURER PART NUMBER") "MMSZ4690T1G") (field (name "TOLERANCE") "±5%"))
      (libsource (lib "TenergyLibrary") (part "Diode Zener 5.6V SOD123"))
    )
    (comp (ref "D108")
      (value "5.6V")
      (footprint "BZT52H (SOD123F)")
      (description "DIODE ZENER 5.6V 500MW SOD-123")
      (fields (field (name "MANUFACTURER PART NUMBER") "MMSZ4690T1G") (field (name "TOLERANCE") "±5%"))
      (libsource (lib "TenergyLibrary") (part "Diode Zener 5.6V SOD123"))
    )
    (comp (ref "D109")
      (value "5.6V")
      (footprint "BZT52H (SOD123F)")
      (description "DIODE ZENER 5.6V 500MW SOD-123")
      (fields (field (name "MANUFACTURER PART NUMBER") "MMSZ4690T1G") (field (name "TOLERANCE") "±5%"))
      (libsource (lib "TenergyLibrary") (part "Diode Zener 5.6V SOD123"))
    )
    (comp (ref "D110")
      (value "5.6V")
      (footprint "BZT52H (SOD123F)")
      (description "DIODE ZENER 5.6V 500MW SOD-123")
      (fields (field (name "MANUFACTURER PART NUMBER") "MMSZ4690T1G") (field (name "TOLERANCE") "±5%"))
      (libsource (lib "TenergyLibrary") (part "Diode Zener 5.6V SOD123"))
    )
    (comp (ref "D111")
      (value "5.6V")
      (footprint "BZT52H (SOD123F)")
      (description "DIODE ZENER 5.6V 500MW SOD-123")
      (fields (field (name "MANUFACTURER PART NUMBER") "MMSZ4690T1G") (field (name "TOLERANCE") "±5%"))
      (libsource (lib "TenergyLibrary") (part "Diode Zener 5.6V SOD123"))
    )
    (comp (ref "D112")
      (value "5.6V")
      (footprint "BZT52H (SOD123F)")
      (description "DIODE ZENER 5.6V 500MW SOD-123")
      (fields (field (name "MANUFACTURER PART NUMBER") "MMSZ4690T1G") (field (name "TOLERANCE") "±5%"))
      (libsource (lib "TenergyLibrary") (part "Diode Zener 5.6V SOD123"))
    )
    (comp (ref "D113")
      (value "5.6V")
      (footprint "BZT52H (SOD123F)")
      (description "DIODE ZENER 5.6V 500MW SOD-123")
      (fields (field (name "MANUFACTURER PART NUMBER") "MMSZ4690T1G") (field (name "TOLERANCE") "±5%"))
      (libsource (lib "TenergyLibrary") (part "Diode Zener 5.6V SOD123"))
    )
    (comp (ref "D114")
      (value "5.6V")
      (footprint "BZT52H (SOD123F)")
      (description "DIODE ZENER 5.6V 500MW SOD-123")
      (fields (field (name "MANUFACTURER PART NUMBER") "MMSZ4690T1G") (field (name "TOLERANCE") "±5%"))
      (libsource (lib "TenergyLibrary") (part "Diode Zener 5.6V SOD123"))
    )
    (comp (ref "D115")
      (value "5.6V")
      (footprint "BZT52H (SOD123F)")
      (description "DIODE ZENER 5.6V 500MW SOD-123")
      (fields (field (name "MANUFACTURER PART NUMBER") "MMSZ4690T1G") (field (name "TOLERANCE") "±5%"))
      (libsource (lib "TenergyLibrary") (part "Diode Zener 5.6V SOD123"))
    )
    (comp (ref "D116")
      (value "5.6V")
      (footprint "BZT52H (SOD123F)")
      (description "DIODE ZENER 5.6V 500MW SOD-123")
      (fields (field (name "MANUFACTURER PART NUMBER") "MMSZ4690T1G") (field (name "TOLERANCE") "±5%"))
      (libsource (lib "TenergyLibrary") (part "Diode Zener 5.6V SOD123"))
    )
    (comp (ref "D117")
      (value "RED")
      (footprint "LED SM REVERSE-RED")
      (description "LED RED CLR SM1206 REVERSE")
      (fields
        (field (name "MANUFACTURER") "Dialight")
        (field (name "MANUFACTURER PART NUMBER") "597-6001-607F")
      )
      (libsource (lib "TenergyLibrary") (part "LED Red"))
    )
    (comp (ref "D118")
      (value "RED")
      (footprint "LED SM REVERSE-RED")
      (description "LED RED CLR SM1206 REVERSE")
      (fields
        (field (name "MANUFACTURER") "Dialight")
        (field (name "MANUFACTURER PART NUMBER") "597-6001-607F")
      )
      (libsource (lib "TenergyLibrary") (part "LED Red"))
    )
    (comp (ref "D121")
      (value "BAS21")
      (footprint "SOT23_N")
      (description "DIODE, 200mA, 250V, SOT-23")
      (libsource (lib "TenergyLibrary") (part "Diode Standard SOT-23"))
    )
    (comp (ref "D123")
      (value "160V")
      (footprint "SMB")
      (description "DIODE TVS 160V 600W UNI 5% SMB")
      (fields (field (name "MANUFACTURER PART NUMBER") "SMBJ160A"))
      (libsource (lib "TenergyLibrary") (part "Diode TVS 160V SMB"))
    )
    (comp (ref "D124")
      (value "160V")
      (footprint "SMB")
      (description "DIODE TVS 160V 600W UNI 5% SMB")
      (fields (field (name "MANUFACTURER PART NUMBER") "SMBJ160A"))
      (libsource (lib "TenergyLibrary") (part "Diode TVS 160V SMB"))
    )
    (comp (ref "D125")
      (value "16V")
      (footprint "SMB")
      (description "DIODE TVS 16V 600W UNIDIR 5% SMB")
      (libsource (lib "TenergyLibrary") (part "Diode TVS 16V SMB"))
    )
    (comp (ref "D126")
      (value "16V")
      (footprint "SMB")
      (description "DIODE TVS 16V 600W UNIDIR 5% SMB")
      (libsource (lib "TenergyLibrary") (part "Diode TVS 16V SMB"))
    )
    (comp (ref "DZ1")
      (value "NP")
      (footprint "BZT52H (SOD123F)")
      (description "DIODE DNP SOD123")
      (libsource (lib "TenergyLibrary") (part "Diode Zener DNP SOD123"))
    )
    (comp (ref "DZ2")
      (value "NP")
      (footprint "BZT52H (SOD123F)")
      (description "DIODE DNP SOD123")
      (libsource (lib "TenergyLibrary") (part "Diode Zener DNP SOD123"))
    )
    (comp (ref "DZ3")
      (value "7.5V")
      (footprint "BZT52H (SOD123F)")
      (description "DIODE ZENER 7.5V 500MW SOD123")
      (fields (field (name "TOLERANCE") "±5%") (field (name "MANUFACTURER PART NUMBER") "MMSZ4693T1G"))
      (libsource (lib "TenergyLibrary") (part "Diode Zener 7.5V SOD123"))
    )
    (comp (ref "DZ4")
      (value "NP")
      (footprint "BZT52H (SOD123F)")
      (description "DIODE DNP SOD123")
      (libsource (lib "TenergyLibrary") (part "Diode Zener DNP SOD123"))
    )
    (comp (ref "DZ5")
      (value "AZ23C5V6")
      (footprint "AZ23C5V6 SOT23-3")
      (description "DIODE ZENER DUAL 5.6V SOT23")
      (fields
        (field (name "MANUFACTURER") "Diodes Inc")
        (field (name "MANUFACTURER PART NUMBER") "AZ23C5V6-7-F")
      )
      (libsource (lib "TenergyLibrary") (part "Diode Zener 5.6V Dual SOT23"))
    )
    (comp (ref "DZ6")
      (value "5.6V")
      (footprint "BZT52H (SOD123F)")
      (description "DIODE ZENER 5.6V 500MW SOD-123")
      (fields (field (name "TOLERANCE") "±5%") (field (name "MANUFACTURER PART NUMBER") "MMSZ4690T1G"))
      (libsource (lib "TenergyLibrary") (part "Diode Zener 5.6V SOD123"))
    )
    (comp (ref "DZ7")
      (value "NP")
      (footprint "BZT52H (SOD123F)")
      (description "DIODE DNP SOD123")
      (libsource (lib "TenergyLibrary") (part "Diode Zener DNP SOD123"))
    )
    (comp (ref "DZ9")
      (value "25V")
      (footprint "MMS52xxxT1G (SOD-123)")
      (description "DIODE ZENER 25V 500MW SOD-123")
      (fields (field (name "TOLERANCE") "±5%"))
      (libsource (lib "TenergyLibrary") (part "Diode Zener 25V SOD123"))
    )
    (comp (ref "DZ100")
      (value "16V")
      (footprint "MMS52xxxT1G (SOD-123)")
      (description "DIODE ZENER 16V 500MW SOD123")
      (fields (field (name "MANUFACTURER PART NUMBER") "MMSZ4703T1G"))
      (libsource (lib "TenergyLibrary") (part "Diode Zener 16V SOD123"))
    )
    (comp (ref "DZ101")
      (value "16V")
      (footprint "MMS52xxxT1G (SOD-123)")
      (description "DIODE ZENER 16V 500MW SOD123")
      (fields (field (name "MANUFACTURER PART NUMBER") "MMSZ4703T1G"))
      (libsource (lib "TenergyLibrary") (part "Diode Zener 16V SOD123"))
    )
    (comp (ref "DZ102")
      (value "16V")
      (footprint "MMS52xxxT1G (SOD-123)")
      (description "DIODE ZENER 16V 500MW SOD123")
      (fields (field (name "MANUFACTURER PART NUMBER") "MMSZ4703T1G"))
      (libsource (lib "TenergyLibrary") (part "Diode Zener 16V SOD123"))
    )
    (comp (ref "F100")
      (value "20A")
      (footprint "FUSE 3AB W/PIGTAIL-SURFACE MOUNT 90DEG")
      (description "FUSE 20A 3AB CARTRIDGE")
      (fields
        (field (name "MANUFACTURER") "Littelfuse Inc")
        (field (name "MANUFACTURER PART NUMBER") "0324020.HXP")
      )
      (libsource (lib "TenergyLibrary") (part "FUSE 25A M-BLOW 72VDC SM3812"))
    )
    (comp (ref "F101")
      (value "20A")
      (footprint "FUSE 3AB W/PIGTAIL-SURFACE MOUNT 90DEG")
      (description "FUSE 20A 3AB CARTRIDGE")
      (fields
        (field (name "MANUFACTURER") "Littelfuse Inc")
        (field (name "MANUFACTURER PART NUMBER") "0324020.HXP")
      )
      (libsource (lib "TenergyLibrary") (part "FUSE 25A M-BLOW 72VDC SM3812"))
    )
    (comp (ref "P1")
      (value "Header 15X2")
      (footprint "HDR 2X15 0.1\" CTRS TH SHROUDED W/PCB ALG PIN")
      (description "CONN, HDR 2X15P 0.1\" SHROUDED SM W/PCB ALGN")
      (fields
        (field (name "MANUFACTURER") "SAMTEC")
        (field (name "MANUFACTURER PART NUMBER") "TSSH-115-01-L-DV-A")
      )
      (libsource (lib "TenergyLibrary") (part "Header 15X2"))
    )
    (comp (ref "P2")
      (value "Header 25X2")
      (footprint "HDR 2X25 0.1\" CTRS TH SHROUDED W/PCB LOC PIN")
      (description "CONN, HDR 2X25 0.1\" SHROUDED SM W/PCB ALGN")
      (fields
        (field (name "MANUFACTURER") "SAMTEC")
        (field (name "MANUFACTURER PART NUMBER") "TSSH-125-01-L-DV-A")
      )
      (libsource (lib "TenergyLibrary") (part "Header 25X2"))
    )
    (comp (ref "P100")
      (value "87438-0842")
      (footprint "HDR1X8")
      (description "MOLEX - 87438-0842 - HEADER, 1.5MM, R/A, 8WAY")
      (libsource (lib "TenergyLibrary") (part "Header 8x1 1.55mm"))
    )
    (comp (ref "Q1")
      (value "AO3402")
      (footprint "NDS331N (SOT23-3)")
      (description "XSTR, MOSFET, N-CH, 20V, 1.3A, SOT-23")
      (libsource (lib "TenergyLibrary") (part "MOSFET N 20V 1.3A"))
    )
    (comp (ref "Q2")
      (value "AO3402")
      (footprint "NDS331N (SOT23-3)")
      (description "XSTR, MOSFET, N-CH, 20V, 1.3A, SOT-23")
      (libsource (lib "TenergyLibrary") (part "MOSFET N 20V 1.3A"))
    )
    (comp (ref "Q3")
      (value "BSS84-7-F")
      (footprint "ZVP1320F (SOT23-3)")
      (description "MOSFET P-CH 50V 130MA SOT23-3")
      (libsource (lib "TenergyLibrary") (part "MOSFET P 50V 130MA SOT23-3"))
    )
    (comp (ref "Q4")
      (value "AO3402")
      (footprint "NDS331N (SOT23-3)")
      (description "XSTR, MOSFET, N-CH, 20V, 1.3A, SOT-23")
      (libsource (lib "TenergyLibrary") (part "MOSFET N 20V 1.3A"))
    )
    (comp (ref "Q5")
      (value "BSS84-7-F")
      (footprint "ZVP1320F (SOT23-3)")
      (description "MOSFET P-CH 50V 130MA SOT23-3")
      (libsource (lib "TenergyLibrary") (part "MOSFET P 50V 130MA SOT23-3"))
    )
    (comp (ref "Q6")
      (value "AO3402")
      (footprint "NDS331N (SOT23-3)")
      (description "XSTR, MOSFET, N-CH, 20V, 1.3A, SOT-23")
      (libsource (lib "TenergyLibrary") (part "MOSFET N 20V 1.3A"))
    )
    (comp (ref "Q7")
      (value "BSS123-7-F")
      (footprint "BSS123-7-F (SOT23-3)")
      (description "XSTR, MOSFET, N-CH, 100V, 0.17A, SOT-23")
      (fields (field (name "MANUFACTURER") "Diodes Inc"))
      (libsource (lib "TenergyLibrary") (part "BSS123-7-F"))
    )
    (comp (ref "Q8")
      (value "AO3402")
      (footprint "NDS331N (SOT23-3)")
      (description "XSTR, MOSFET, N-CH, 20V, 1.3A, SOT-23")
      (libsource (lib "TenergyLibrary") (part "MOSFET N 20V 1.3A"))
    )
    (comp (ref "Q9")
      (value "FQT7N10LTF")
      (footprint "FT7N10L (SOT230P700X180-4N)")
      (description "XSTR, MOSFET, N-CH, 100V, 1.7A, SOT-223")
      (fields (field (name "MANUFACTURER") "Fairchild Semiconductor"))
      (libsource (lib "TenergyLibrary") (part "MOSFET N 100V 1.7A SOT223"))
    )
    (comp (ref "Q10")
      (value "2N7002K")
      (footprint "2N7002K (SOT23-3)")
      (description "XSTR, MOSFET, N-CH, 60V, 115MA, SOT-23")
      (fields
        (field (name "MANUFACTURER") "ON Semiconductor")
        (field (name "MANUFACTURER PART NUMBER") "2N7002LT3G")
      )
      (libsource (lib "TenergyLibrary") (part "MOSFET N 60V 115MA SOT-23"))
    )
    (comp (ref "Q11")
      (value "AO3402")
      (footprint "NDS331N (SOT23-3)")
      (description "XSTR, MOSFET, N-CH, 20V, 1.3A, SOT-23")
      (libsource (lib "TenergyLibrary") (part "MOSFET N 20V 1.3A"))
    )
    (comp (ref "Q12")
      (value "AO3402")
      (footprint "NDS331N (SOT23-3)")
      (description "XSTR, MOSFET, N-CH, 20V, 1.3A, SOT-23")
      (libsource (lib "TenergyLibrary") (part "MOSFET N 20V 1.3A"))
    )
    (comp (ref "Q13")
      (value "AO3402")
      (footprint "NDS331N (SOT23-3)")
      (description "XSTR, MOSFET, N-CH, 20V, 1.3A, SOT-23")
      (libsource (lib "TenergyLibrary") (part "MOSFET N 20V 1.3A"))
    )
    (comp (ref "Q14")
      (value "ZXMP10A13FTA")
      (footprint "BSS84 (SOT23-3)")
      (description "MOSFET P-CH 100V 600MA SOT23-3")
      (fields (field (name "MANUFACTURER") "Diodes Inc"))
      (libsource (lib "TenergyLibrary") (part "MOSFET P 100V 600MA"))
    )
    (comp (ref "Q15")
      (value "AO3402")
      (footprint "NDS331N (SOT23-3)")
      (description "XSTR, MOSFET, N-CH, 20V, 1.3A, SOT-23")
      (libsource (lib "TenergyLibrary") (part "MOSFET N 20V 1.3A"))
    )
    (comp (ref "Q16")
      (value "BSS123-7-F")
      (footprint "BSS123-7-F (SOT23-3)")
      (description "XSTR, MOSFET, N-CH, 100V, 0.17A, SOT-23")
      (fields (field (name "MANUFACTURER") "Diodes Inc"))
      (libsource (lib "TenergyLibrary") (part "BSS123-7-F"))
    )
    (comp (ref "Q17")
      (value "AO3402")
      (footprint "NDS331N (SOT23-3)")
      (description "XSTR, MOSFET, N-CH, 20V, 1.3A, SOT-23")
      (libsource (lib "TenergyLibrary") (part "MOSFET N 20V 1.3A"))
    )
    (comp (ref "Q18")
      (value "BSS123-7-F")
      (footprint "BSS123-7-F (SOT23-3)")
      (description "XSTR, MOSFET, N-CH, 100V, 0.17A, SOT-23")
      (fields (field (name "MANUFACTURER") "Diodes Inc"))
      (libsource (lib "TenergyLibrary") (part "BSS123-7-F"))
    )
    (comp (ref "Q19")
      (value "AO3402")
      (footprint "NDS331N (SOT23-3)")
      (description "XSTR, MOSFET, N-CH, 20V, 1.3A, SOT-23")
      (libsource (lib "TenergyLibrary") (part "MOSFET N 20V 1.3A"))
    )
    (comp (ref "Q20")
      (value "AO3402")
      (footprint "NDS331N (SOT23-3)")
      (description "XSTR, MOSFET, N-CH, 20V, 1.3A, SOT-23")
      (libsource (lib "TenergyLibrary") (part "MOSFET N 20V 1.3A"))
    )
    (comp (ref "Q21")
      (value "AO3402")
      (footprint "NDS331N (SOT23-3)")
      (description "XSTR, MOSFET, N-CH, 20V, 1.3A, SOT-23")
      (libsource (lib "TenergyLibrary") (part "MOSFET N 20V 1.3A"))
    )
    (comp (ref "Q22")
      (value "AO3402")
      (footprint "NDS331N (SOT23-3)")
      (description "XSTR, MOSFET, N-CH, 20V, 1.3A, SOT-23")
      (libsource (lib "TenergyLibrary") (part "MOSFET N 20V 1.3A"))
    )
    (comp (ref "Q23")
      (value "ZVP1320FTA")
      (footprint "ZVP1320F (SOT23-3)")
      (description "XSTR MOSFET P-CH 200V 35MA SOT23-3")
      (fields (field (name "MANUFACTURER") "Diodes Inc"))
      (libsource (lib "TenergyLibrary") (part "MOSFET P 200V 35MA"))
    )
    (comp (ref "Q24")
      (value "2N7002K")
      (footprint "2N7002K (SOT23-3)")
      (description "XSTR, MOSFET, N-CH, 60V, 115MA, SOT-23")
      (fields
        (field (name "MANUFACTURER") "ON Semiconductor")
        (field (name "MANUFACTURER PART NUMBER") "2N7002LT3G")
      )
      (libsource (lib "TenergyLibrary") (part "MOSFET N 60V 115MA SOT-23"))
    )
    (comp (ref "Q25")
      (value "AO3402")
      (footprint "NDS331N (SOT23-3)")
      (description "XSTR, MOSFET, N-CH, 20V, 1.3A, SOT-23")
      (libsource (lib "TenergyLibrary") (part "MOSFET N 20V 1.3A"))
    )
    (comp (ref "Q26")
      (value "AO3402")
      (footprint "NDS331N (SOT23-3)")
      (description "XSTR, MOSFET, N-CH, 20V, 1.3A, SOT-23")
      (libsource (lib "TenergyLibrary") (part "MOSFET N 20V 1.3A"))
    )
    (comp (ref "Q27")
      (value "IPB107N20N3 G")
      (footprint "IPB107N20N3 G (PG-TO263-3)")
      (description "XSTR, MOSFET, N-CH, 200V, 88A, SM TO-263-3")
      (fields (field (name "MANUFACTURER") "Infineon Technologies"))
      (libsource (lib "TenergyLibrary") (part "MOSFET N 200V 88A SM-TO263-3"))
    )
    (comp (ref "Q28")
      (value "IPB107N20N3 G")
      (footprint "IPB107N20N3 G (PG-TO263-3)")
      (description "XSTR, MOSFET, N-CH, 200V, 88A, SM TO-263-3")
      (fields (field (name "MANUFACTURER") "Infineon Technologies"))
      (libsource (lib "TenergyLibrary") (part "MOSFET N 200V 88A SM-TO263-3"))
    )
    (comp (ref "Q29")
      (value "IPB107N20N3 G")
      (footprint "IPB107N20N3 G (PG-TO263-3)")
      (description "XSTR, MOSFET, N-CH, 200V, 88A, SM TO-263-3")
      (fields (field (name "MANUFACTURER") "Infineon Technologies"))
      (libsource (lib "TenergyLibrary") (part "MOSFET N 200V 88A SM-TO263-3"))
    )
    (comp (ref "Q30")
      (value "IPB107N20N3 G")
      (footprint "IPB107N20N3 G (PG-TO263-3)")
      (description "XSTR, MOSFET, N-CH, 200V, 88A, SM TO-263-3")
      (fields (field (name "MANUFACTURER") "Infineon Technologies"))
      (libsource (lib "TenergyLibrary") (part "MOSFET N 200V 88A SM-TO263-3"))
    )
    (comp (ref "Q31")
      (value "IPB107N20N3 G")
      (footprint "IPB107N20N3 G (PG-TO263-3)")
      (description "XSTR, MOSFET, N-CH, 200V, 88A, SM TO-263-3")
      (fields (field (name "MANUFACTURER") "Infineon Technologies"))
      (libsource (lib "TenergyLibrary") (part "MOSFET N 200V 88A SM-TO263-3"))
    )
    (comp (ref "Q32")
      (value "IPB107N20N3 G")
      (footprint "IPB107N20N3 G (PG-TO263-3)")
      (description "XSTR, MOSFET, N-CH, 200V, 88A, SM TO-263-3")
      (fields (field (name "MANUFACTURER") "Infineon Technologies"))
      (libsource (lib "TenergyLibrary") (part "MOSFET N 200V 88A SM-TO263-3"))
    )
    (comp (ref "Q33")
      (value "ZVN3320FTA")
      (footprint "BSS123-7-F (SOT23-3)")
      (description "XSTR MOSFET N-CH 200V 60MA SOT23-3")
      (fields (field (name "MANUFACTURER") "Diodes Inc"))
      (libsource (lib "TenergyLibrary") (part "MOSFET N 200V 60MA"))
    )
    (comp (ref "Q100")
      (value "2N7002K")
      (footprint "2N7002K (SOT23-3)")
      (description "XSTR, MOSFET, N-CH, 60V, 115MA, SOT-23")
      (fields
        (field (name "MANUFACTURER") "ON Semiconductor")
        (field (name "MANUFACTURER PART NUMBER") "2N7002LT3G")
      )
      (libsource (lib "TenergyLibrary") (part "MOSFET N 60V 115MA SOT-23"))
    )
    (comp (ref "Q101")
      (value "2N7002K")
      (footprint "2N7002K (SOT23-3)")
      (description "XSTR, MOSFET, N-CH, 60V, 115MA, SOT-23")
      (fields
        (field (name "MANUFACTURER") "ON Semiconductor")
        (field (name "MANUFACTURER PART NUMBER") "2N7002LT3G")
      )
      (libsource (lib "TenergyLibrary") (part "MOSFET N 60V 115MA SOT-23"))
    )
    (comp (ref "Q102")
      (value "2N7002K")
      (footprint "2N7002K (SOT23-3)")
      (description "XSTR, MOSFET, N-CH, 60V, 115MA, SOT-23")
      (fields
        (field (name "MANUFACTURER") "ON Semiconductor")
        (field (name "MANUFACTURER PART NUMBER") "2N7002LT3G")
      )
      (libsource (lib "TenergyLibrary") (part "MOSFET N 60V 115MA SOT-23"))
    )
    (comp (ref "Q103")
      (value "2N7002K")
      (footprint "2N7002K (SOT23-3)")
      (description "XSTR, MOSFET, N-CH, 60V, 115MA, SOT-23")
      (fields
        (field (name "MANUFACTURER") "ON Semiconductor")
        (field (name "MANUFACTURER PART NUMBER") "2N7002LT3G")
      )
      (libsource (lib "TenergyLibrary") (part "MOSFET N 60V 115MA SOT-23"))
    )
    (comp (ref "R1")
      (value "51")
      (footprint "1608[0603]")
      (description "RES 51 OHM 1/10W 5% SM0603")
      (fields
        (field (name "MANUFACTURER") "Yageo")
        (field (name "MANUFACTURER PART NUMBER") "RC0603JR-0751RL")
      )
      (libsource (lib "TenergyLibrary") (part "Res 51 0603"))
    )
    (comp (ref "R2")
      (value "330")
      (footprint "1608[0603]")
      (description "RES 330 OHM 1/10W 5% 0603 SMD")
      (fields
        (field (name "MANUFACTURER") "Yageo")
        (field (name "MANUFACTURER PART NUMBER") "RC0603JR-07330RL")
      )
      (libsource (lib "TenergyLibrary") (part "Res 330 0603"))
    )
    (comp (ref "R3A")
      (value "68")
      (footprint "RES SM2512 W/ HEATSINK")
      (description "RES 68 OHM 1W 5% 2512 SMD")
      (fields
        (field (name "MANUFACTURER") "Panasonic Electronic Components")
        (field (name "MANUFACTURER PART NUMBER") "ERJ-1TYJ680U")
      )
      (libsource (lib "TenergyLibrary") (part "Res 68 2512"))
    )
    (comp (ref "R3B")
      (value "68")
      (footprint "RES SM2512 W/ HEATSINK")
      (description "RES 68 OHM 1W 5% 2512 SMD")
      (fields
        (field (name "MANUFACTURER") "Panasonic Electronic Components")
        (field (name "MANUFACTURER PART NUMBER") "ERJ-1TYJ680U")
      )
      (libsource (lib "TenergyLibrary") (part "Res 68 2512"))
    )
    (comp (ref "R3C")
      (value "68")
      (footprint "RES SM2512 W/ HEATSINK")
      (description "RES 68 OHM 1W 5% 2512 SMD")
      (fields
        (field (name "MANUFACTURER") "Panasonic Electronic Components")
        (field (name "MANUFACTURER PART NUMBER") "ERJ-1TYJ680U")
      )
      (libsource (lib "TenergyLibrary") (part "Res 68 2512"))
    )
    (comp (ref "R4")
      (value "330")
      (footprint "1608[0603]")
      (description "RES 330 OHM 1/10W 5% 0603 SMD")
      (fields
        (field (name "MANUFACTURER") "Yageo")
        (field (name "MANUFACTURER PART NUMBER") "RC0603JR-07330RL")
      )
      (libsource (lib "TenergyLibrary") (part "Res 330 0603"))
    )
    (comp (ref "R5A")
      (value "68")
      (footprint "RES SM2512 W/ HEATSINK")
      (description "RES 68 OHM 1W 5% 2512 SMD")
      (fields
        (field (name "MANUFACTURER") "Panasonic Electronic Components")
        (field (name "MANUFACTURER PART NUMBER") "ERJ-1TYJ680U")
      )
      (libsource (lib "TenergyLibrary") (part "Res 68 2512"))
    )
    (comp (ref "R5B")
      (value "68")
      (footprint "RES SM2512 W/ HEATSINK")
      (description "RES 68 OHM 1W 5% 2512 SMD")
      (fields
        (field (name "MANUFACTURER") "Panasonic Electronic Components")
        (field (name "MANUFACTURER PART NUMBER") "ERJ-1TYJ680U")
      )
      (libsource (lib "TenergyLibrary") (part "Res 68 2512"))
    )
    (comp (ref "R5C")
      (value "68")
      (footprint "RES SM2512 W/ HEATSINK")
      (description "RES 68 OHM 1W 5% 2512 SMD")
      (fields
        (field (name "MANUFACTURER") "Panasonic Electronic Components")
        (field (name "MANUFACTURER PART NUMBER") "ERJ-1TYJ680U")
      )
      (libsource (lib "TenergyLibrary") (part "Res 68 2512"))
    )
    (comp (ref "R6")
      (value "200K")
      (footprint "1608[0603]")
      (description "RES 200K OHM 1/10W 1% 0603 SMD")
      (fields (field (name "TOLERANCE") "¡À1%"))
      (libsource (lib "TenergyLibrary") (part "Res 200K 0603"))
    )
    (comp (ref "R9")
      (value "330")
      (footprint "1608[0603]")
      (description "RES 330 OHM 1/10W 5% 0603 SMD")
      (fields
        (field (name "MANUFACTURER") "Yageo")
        (field (name "MANUFACTURER PART NUMBER") "RC0603JR-07330RL")
      )
      (libsource (lib "TenergyLibrary") (part "Res 330 0603"))
    )
    (comp (ref "R10A")
      (value "68")
      (footprint "RES SM2512 W/ HEATSINK")
      (description "RES 68 OHM 1W 5% 2512 SMD")
      (fields
        (field (name "MANUFACTURER") "Panasonic Electronic Components")
        (field (name "MANUFACTURER PART NUMBER") "ERJ-1TYJ680U")
      )
      (libsource (lib "TenergyLibrary") (part "Res 68 2512"))
    )
    (comp (ref "R10B")
      (value "68")
      (footprint "RES SM2512 W/ HEATSINK")
      (description "RES 68 OHM 1W 5% 2512 SMD")
      (fields
        (field (name "MANUFACTURER") "Panasonic Electronic Components")
        (field (name "MANUFACTURER PART NUMBER") "ERJ-1TYJ680U")
      )
      (libsource (lib "TenergyLibrary") (part "Res 68 2512"))
    )
    (comp (ref "R10C")
      (value "68")
      (footprint "RES SM2512 W/ HEATSINK")
      (description "RES 68 OHM 1W 5% 2512 SMD")
      (fields
        (field (name "MANUFACTURER") "Panasonic Electronic Components")
        (field (name "MANUFACTURER PART NUMBER") "ERJ-1TYJ680U")
      )
      (libsource (lib "TenergyLibrary") (part "Res 68 2512"))
    )
    (comp (ref "R11")
      (value "200K")
      (footprint "1608[0603]")
      (description "RES 200K OHM 1/10W 1% 0603 SMD")
      (fields (field (name "TOLERANCE") "¡À1%"))
      (libsource (lib "TenergyLibrary") (part "Res 200K 0603"))
    )
    (comp (ref "R12")
      (value "20K")
      (footprint "1608[0603]")
      (description "RES 20.0K OHM 1/10W 1% 0603 SMD")
      (fields (field (name "TOLERANCE") "¡À1%"))
      (libsource (lib "TenergyLibrary") (part "Res 20K 0603"))
    )
    (comp (ref "R13")
      (value "20K")
      (footprint "1608[0603]")
      (description "RES 20.0K OHM 1/10W 1% 0603 SMD")
      (fields (field (name "TOLERANCE") "¡À1%"))
      (libsource (lib "TenergyLibrary") (part "Res 20K 0603"))
    )
    (comp (ref "R14")
      (value "20K")
      (footprint "1608[0603]")
      (description "RES 20.0K OHM 1/10W 1% 0603 SMD")
      (fields (field (name "TOLERANCE") "¡À1%"))
      (libsource (lib "TenergyLibrary") (part "Res 20K 0603"))
    )
    (comp (ref "R15")
      (value "20K")
      (footprint "1608[0603]")
      (description "RES 20.0K OHM 1/10W 1% 0603 SMD")
      (fields (field (name "TOLERANCE") "¡À1%"))
      (libsource (lib "TenergyLibrary") (part "Res 20K 0603"))
    )
    (comp (ref "R16")
      (value "330")
      (footprint "1608[0603]")
      (description "RES 330 OHM 1/10W 5% 0603 SMD")
      (fields
        (field (name "MANUFACTURER") "Yageo")
        (field (name "MANUFACTURER PART NUMBER") "RC0603JR-07330RL")
      )
      (libsource (lib "TenergyLibrary") (part "Res 330 0603"))
    )
    (comp (ref "R17A")
      (value "68")
      (footprint "RES SM2512 W/ HEATSINK")
      (description "RES 68 OHM 1W 5% 2512 SMD")
      (fields
        (field (name "MANUFACTURER") "Panasonic Electronic Components")
        (field (name "MANUFACTURER PART NUMBER") "ERJ-1TYJ680U")
      )
      (libsource (lib "TenergyLibrary") (part "Res 68 2512"))
    )
    (comp (ref "R17B")
      (value "68")
      (footprint "RES SM2512 W/ HEATSINK")
      (description "RES 68 OHM 1W 5% 2512 SMD")
      (fields
        (field (name "MANUFACTURER") "Panasonic Electronic Components")
        (field (name "MANUFACTURER PART NUMBER") "ERJ-1TYJ680U")
      )
      (libsource (lib "TenergyLibrary") (part "Res 68 2512"))
    )
    (comp (ref "R17C")
      (value "68")
      (footprint "RES SM2512 W/ HEATSINK")
      (description "RES 68 OHM 1W 5% 2512 SMD")
      (fields
        (field (name "MANUFACTURER") "Panasonic Electronic Components")
        (field (name "MANUFACTURER PART NUMBER") "ERJ-1TYJ680U")
      )
      (libsource (lib "TenergyLibrary") (part "Res 68 2512"))
    )
    (comp (ref "R18")
      (value "200K")
      (footprint "1608[0603]")
      (description "RES 200K OHM 1/10W 1% 0603 SMD")
      (fields (field (name "TOLERANCE") "¡À1%"))
      (libsource (lib "TenergyLibrary") (part "Res 200K 0603"))
    )
    (comp (ref "R19")
      (value "200K")
      (footprint "1608[0603]")
      (description "RES 200K OHM 1/10W 1% 0603 SMD")
      (fields (field (name "TOLERANCE") "¡À1%"))
      (libsource (lib "TenergyLibrary") (part "Res 200K 0603"))
    )
    (comp (ref "R22")
      (value "1M")
      (footprint "1608[0603]")
      (description "RES 1.0M OHM 1/10W 5% 0603 SMD")
      (fields (field (name "TOLERANCE") "±5%"))
      (libsource (lib "TenergyLibrary") (part "Res 1M 0603 5%"))
    )
    (comp (ref "R23")
      (value "51")
      (footprint "1608[0603]")
      (description "RES 51 OHM 1/10W 5% SM0603")
      (fields
        (field (name "MANUFACTURER") "Yageo")
        (field (name "MANUFACTURER PART NUMBER") "RC0603JR-0751RL")
      )
      (libsource (lib "TenergyLibrary") (part "Res 51 0603"))
    )
    (comp (ref "R24")
      (value "330")
      (footprint "1608[0603]")
      (description "RES 330 OHM 1/10W 5% 0603 SMD")
      (fields
        (field (name "MANUFACTURER") "Yageo")
        (field (name "MANUFACTURER PART NUMBER") "RC0603JR-07330RL")
      )
      (libsource (lib "TenergyLibrary") (part "Res 330 0603"))
    )
    (comp (ref "R25")
      (value "1K")
      (footprint "1608[0603]")
      (description "RES 1.00K OHM 1/10W 1% 0603 SMD")
      (fields (field (name "TOLERANCE") "¡À1%") (field (name "MANUFACTURER PART NUMBER") "RC0603FR-071KL"))
      (libsource (lib "TenergyLibrary") (part "Res 1K 0603"))
    )
    (comp (ref "R26")
      (value "1K")
      (footprint "1608[0603]")
      (description "RES 1.00K OHM 1/10W 1% 0603 SMD")
      (fields (field (name "TOLERANCE") "¡À1%") (field (name "MANUFACTURER PART NUMBER") "RC0603FR-071KL"))
      (libsource (lib "TenergyLibrary") (part "Res 1K 0603"))
    )
    (comp (ref "R27A")
      (value "68")
      (footprint "RES SM2512 W/ HEATSINK")
      (description "RES 68 OHM 1W 5% 2512 SMD")
      (fields
        (field (name "MANUFACTURER") "Panasonic Electronic Components")
        (field (name "MANUFACTURER PART NUMBER") "ERJ-1TYJ680U")
      )
      (libsource (lib "TenergyLibrary") (part "Res 68 2512"))
    )
    (comp (ref "R27B")
      (value "68")
      (footprint "RES SM2512 W/ HEATSINK")
      (description "RES 68 OHM 1W 5% 2512 SMD")
      (fields
        (field (name "MANUFACTURER") "Panasonic Electronic Components")
        (field (name "MANUFACTURER PART NUMBER") "ERJ-1TYJ680U")
      )
      (libsource (lib "TenergyLibrary") (part "Res 68 2512"))
    )
    (comp (ref "R27C")
      (value "68")
      (footprint "RES SM2512 W/ HEATSINK")
      (description "RES 68 OHM 1W 5% 2512 SMD")
      (fields
        (field (name "MANUFACTURER") "Panasonic Electronic Components")
        (field (name "MANUFACTURER PART NUMBER") "ERJ-1TYJ680U")
      )
      (libsource (lib "TenergyLibrary") (part "Res 68 2512"))
    )
    (comp (ref "R28")
      (value "280K")
      (footprint "1608[0603]")
      (description "RES 280K OHM 1/10W 1% 0603 SMD")
      (fields (field (name "TOLERANCE") "¡À1%"))
      (libsource (lib "TenergyLibrary") (part "Res 280K  0603"))
    )
    (comp (ref "R29")
      (value "20K")
      (footprint "1608[0603]")
      (description "RES 20.0K OHM 1/10W 1% 0603 SMD")
      (fields (field (name "TOLERANCE") "¡À1%"))
      (libsource (lib "TenergyLibrary") (part "Res 20K 0603"))
    )
    (comp (ref "R30")
      (value "330")
      (footprint "1608[0603]")
      (description "RES 330 OHM 1/10W 5% 0603 SMD")
      (fields
        (field (name "MANUFACTURER") "Yageo")
        (field (name "MANUFACTURER PART NUMBER") "RC0603JR-07330RL")
      )
      (libsource (lib "TenergyLibrary") (part "Res 330 0603"))
    )
    (comp (ref "R31")
      (value "510K")
      (footprint "6-0805_N")
      (description "RES 510K OHM 1/8W 5% SM0805")
      (fields
        (field (name "MANUFACTURER") "Yageo")
        (field (name "MANUFACTURER PART NUMBER") "RC0805JR-07510KL")
      )
      (libsource (lib "TenergyLibrary") (part "Res 510K 0805"))
    )
    (comp (ref "R32A")
      (value "68")
      (footprint "RES SM2512 W/ HEATSINK")
      (description "RES 68 OHM 1W 5% 2512 SMD")
      (fields
        (field (name "MANUFACTURER") "Panasonic Electronic Components")
        (field (name "MANUFACTURER PART NUMBER") "ERJ-1TYJ680U")
      )
      (libsource (lib "TenergyLibrary") (part "Res 68 2512"))
    )
    (comp (ref "R32B")
      (value "68")
      (footprint "RES SM2512 W/ HEATSINK")
      (description "RES 68 OHM 1W 5% 2512 SMD")
      (fields
        (field (name "MANUFACTURER") "Panasonic Electronic Components")
        (field (name "MANUFACTURER PART NUMBER") "ERJ-1TYJ680U")
      )
      (libsource (lib "TenergyLibrary") (part "Res 68 2512"))
    )
    (comp (ref "R32C")
      (value "68")
      (footprint "RES SM2512 W/ HEATSINK")
      (description "RES 68 OHM 1W 5% 2512 SMD")
      (fields
        (field (name "MANUFACTURER") "Panasonic Electronic Components")
        (field (name "MANUFACTURER PART NUMBER") "ERJ-1TYJ680U")
      )
      (libsource (lib "TenergyLibrary") (part "Res 68 2512"))
    )
    (comp (ref "R33")
      (value "1")
      (footprint "1608[0603]")
      (description "RESISTOR, 1R, 100MW, 5%")
      (libsource (lib "TenergyLibrary") (part "Res 1 0603"))
    )
    (comp (ref "R34")
      (value "330")
      (footprint "1608[0603]")
      (description "RES 330 OHM 1/10W 5% 0603 SMD")
      (fields
        (field (name "MANUFACTURER") "Yageo")
        (field (name "MANUFACTURER PART NUMBER") "RC0603JR-07330RL")
      )
      (libsource (lib "TenergyLibrary") (part "Res 330 0603"))
    )
    (comp (ref "R35A")
      (value "68")
      (footprint "RES SM2512 W/ HEATSINK")
      (description "RES 68 OHM 1W 5% 2512 SMD")
      (fields
        (field (name "MANUFACTURER") "Panasonic Electronic Components")
        (field (name "MANUFACTURER PART NUMBER") "ERJ-1TYJ680U")
      )
      (libsource (lib "TenergyLibrary") (part "Res 68 2512"))
    )
    (comp (ref "R35B")
      (value "68")
      (footprint "RES SM2512 W/ HEATSINK")
      (description "RES 68 OHM 1W 5% 2512 SMD")
      (fields
        (field (name "MANUFACTURER") "Panasonic Electronic Components")
        (field (name "MANUFACTURER PART NUMBER") "ERJ-1TYJ680U")
      )
      (libsource (lib "TenergyLibrary") (part "Res 68 2512"))
    )
    (comp (ref "R35C")
      (value "68")
      (footprint "RES SM2512 W/ HEATSINK")
      (description "RES 68 OHM 1W 5% 2512 SMD")
      (fields
        (field (name "MANUFACTURER") "Panasonic Electronic Components")
        (field (name "MANUFACTURER PART NUMBER") "ERJ-1TYJ680U")
      )
      (libsource (lib "TenergyLibrary") (part "Res 68 2512"))
    )
    (comp (ref "R36")
      (value "330")
      (footprint "1608[0603]")
      (description "RES 330 OHM 1/10W 5% 0603 SMD")
      (fields
        (field (name "MANUFACTURER") "Yageo")
        (field (name "MANUFACTURER PART NUMBER") "RC0603JR-07330RL")
      )
      (libsource (lib "TenergyLibrary") (part "Res 330 0603"))
    )
    (comp (ref "R37A")
      (value "68")
      (footprint "RES SM2512 W/ HEATSINK")
      (description "RES 68 OHM 1W 5% 2512 SMD")
      (fields
        (field (name "MANUFACTURER") "Panasonic Electronic Components")
        (field (name "MANUFACTURER PART NUMBER") "ERJ-1TYJ680U")
      )
      (libsource (lib "TenergyLibrary") (part "Res 68 2512"))
    )
    (comp (ref "R37B")
      (value "68")
      (footprint "RES SM2512 W/ HEATSINK")
      (description "RES 68 OHM 1W 5% 2512 SMD")
      (fields
        (field (name "MANUFACTURER") "Panasonic Electronic Components")
        (field (name "MANUFACTURER PART NUMBER") "ERJ-1TYJ680U")
      )
      (libsource (lib "TenergyLibrary") (part "Res 68 2512"))
    )
    (comp (ref "R37C")
      (value "68")
      (footprint "RES SM2512 W/ HEATSINK")
      (description "RES 68 OHM 1W 5% 2512 SMD")
      (fields
        (field (name "MANUFACTURER") "Panasonic Electronic Components")
        (field (name "MANUFACTURER PART NUMBER") "ERJ-1TYJ680U")
      )
      (libsource (lib "TenergyLibrary") (part "Res 68 2512"))
    )
    (comp (ref "R38")
      (value "NP")
      (footprint "1608[0603]")
      (description "Do not Populate")
      (libsource (lib "TenergyLibrary") (part "Res NP 0603"))
    )
    (comp (ref "R40")
      (value "51")
      (footprint "1608[0603]")
      (description "RES 51 OHM 1/10W 5% SM0603")
      (fields
        (field (name "MANUFACTURER") "Yageo")
        (field (name "MANUFACTURER PART NUMBER") "RC0603JR-0751RL")
      )
      (libsource (lib "TenergyLibrary") (part "Res 51 0603"))
    )
    (comp (ref "R41")
      (value "330")
      (footprint "1608[0603]")
      (description "RES 330 OHM 1/10W 5% 0603 SMD")
      (fields
        (field (name "MANUFACTURER") "Yageo")
        (field (name "MANUFACTURER PART NUMBER") "RC0603JR-07330RL")
      )
      (libsource (lib "TenergyLibrary") (part "Res 330 0603"))
    )
    (comp (ref "R42")
      (value "1K")
      (footprint "1608[0603]")
      (description "RES 1.00K OHM 1/10W 1% 0603 SMD")
      (fields (field (name "TOLERANCE") "¡À1%") (field (name "MANUFACTURER PART NUMBER") "RC0603FR-071KL"))
      (libsource (lib "TenergyLibrary") (part "Res 1K 0603"))
    )
    (comp (ref "R43")
      (value "1K")
      (footprint "1608[0603]")
      (description "RES 1.00K OHM 1/10W 1% 0603 SMD")
      (fields (field (name "TOLERANCE") "¡À1%") (field (name "MANUFACTURER PART NUMBER") "RC0603FR-071KL"))
      (libsource (lib "TenergyLibrary") (part "Res 1K 0603"))
    )
    (comp (ref "R44A")
      (value "68")
      (footprint "RES SM2512 W/ HEATSINK")
      (description "RES 68 OHM 1W 5% 2512 SMD")
      (fields
        (field (name "MANUFACTURER") "Panasonic Electronic Components")
        (field (name "MANUFACTURER PART NUMBER") "ERJ-1TYJ680U")
      )
      (libsource (lib "TenergyLibrary") (part "Res 68 2512"))
    )
    (comp (ref "R44B")
      (value "68")
      (footprint "RES SM2512 W/ HEATSINK")
      (description "RES 68 OHM 1W 5% 2512 SMD")
      (fields
        (field (name "MANUFACTURER") "Panasonic Electronic Components")
        (field (name "MANUFACTURER PART NUMBER") "ERJ-1TYJ680U")
      )
      (libsource (lib "TenergyLibrary") (part "Res 68 2512"))
    )
    (comp (ref "R44C")
      (value "68")
      (footprint "RES SM2512 W/ HEATSINK")
      (description "RES 68 OHM 1W 5% 2512 SMD")
      (fields
        (field (name "MANUFACTURER") "Panasonic Electronic Components")
        (field (name "MANUFACTURER PART NUMBER") "ERJ-1TYJ680U")
      )
      (libsource (lib "TenergyLibrary") (part "Res 68 2512"))
    )
    (comp (ref "R45")
      (value "430K")
      (footprint "1608[0603]")
      (description "RES 430K OHM 1/10W 1% 0603 SMD")
      (fields (field (name "TOLERANCE") "¡À1%"))
      (libsource (lib "TenergyLibrary") (part "Res 430K 0603"))
    )
    (comp (ref "R50")
      (value "1.6M")
      (footprint "6-0805_N")
      (description "RES 1.6M OHM 1/8W 5% 0805 SMD")
      (fields (field (name "TOLERANCE") "±5%"))
      (libsource (lib "TenergyLibrary") (part "Res 1.6M 0805"))
    )
    (comp (ref "R51")
      (value "330")
      (footprint "1608[0603]")
      (description "RES 330 OHM 1/10W 5% 0603 SMD")
      (fields
        (field (name "MANUFACTURER") "Yageo")
        (field (name "MANUFACTURER PART NUMBER") "RC0603JR-07330RL")
      )
      (libsource (lib "TenergyLibrary") (part "Res 330 0603"))
    )
    (comp (ref "R52")
      (value "1M")
      (footprint "6-0805_N")
      (description "RES 1M OHM 1/8W .1% 0805 SMD")
      (fields (field (name "TOLERANCE") "±0.1%"))
      (libsource (lib "TenergyLibrary") (part "Res 1M 0805 .1%"))
    )
    (comp (ref "R53")
      (value "1M")
      (footprint "1608[0603]")
      (description "RES 1.0M OHM 1/10W 5% 0603 SMD")
      (fields (field (name "TOLERANCE") "±5%"))
      (libsource (lib "TenergyLibrary") (part "Res 1M 0603 5%"))
    )
    (comp (ref "R54A")
      (value "68")
      (footprint "RES SM2512 W/ HEATSINK")
      (description "RES 68 OHM 1W 5% 2512 SMD")
      (fields
        (field (name "MANUFACTURER") "Panasonic Electronic Components")
        (field (name "MANUFACTURER PART NUMBER") "ERJ-1TYJ680U")
      )
      (libsource (lib "TenergyLibrary") (part "Res 68 2512"))
    )
    (comp (ref "R54B")
      (value "68")
      (footprint "RES SM2512 W/ HEATSINK")
      (description "RES 68 OHM 1W 5% 2512 SMD")
      (fields
        (field (name "MANUFACTURER") "Panasonic Electronic Components")
        (field (name "MANUFACTURER PART NUMBER") "ERJ-1TYJ680U")
      )
      (libsource (lib "TenergyLibrary") (part "Res 68 2512"))
    )
    (comp (ref "R54C")
      (value "68")
      (footprint "RES SM2512 W/ HEATSINK")
      (description "RES 68 OHM 1W 5% 2512 SMD")
      (fields
        (field (name "MANUFACTURER") "Panasonic Electronic Components")
        (field (name "MANUFACTURER PART NUMBER") "ERJ-1TYJ680U")
      )
      (libsource (lib "TenergyLibrary") (part "Res 68 2512"))
    )
    (comp (ref "R55")
      (value "1M")
      (footprint "1608[0603]")
      (description "RES 1.0M OHM 1/10W 5% 0603 SMD")
      (fields (field (name "TOLERANCE") "±5%"))
      (libsource (lib "TenergyLibrary") (part "Res 1M 0603 5%"))
    )
    (comp (ref "R56")
      (value "1M")
      (footprint "1608[0603]")
      (description "RES 1.0M OHM 1/10W 5% 0603 SMD")
      (fields (field (name "TOLERANCE") "±5%"))
      (libsource (lib "TenergyLibrary") (part "Res 1M 0603 5%"))
    )
    (comp (ref "R57")
      (value "100")
      (footprint "1608[0603]")
      (description "RES 100 OHM 1/10W 5% 0603 SMD")
      (fields (field (name "TOLERANCE") "±5%"))
      (libsource (lib "TenergyLibrary") (part "Res 100 0603"))
    )
    (comp (ref "R58")
      (value "16.9K")
      (footprint "1608[0603]")
      (description "RES 16.9K OHM 1/10W .1% 0603 SMD")
      (fields (field (name "TOLERANCE") "±0.1%"))
      (libsource (lib "TenergyLibrary") (part "Res 16.9K 0603"))
    )
    (comp (ref "R59")
      (value "330")
      (footprint "1608[0603]")
      (description "RES 330 OHM 1/10W 5% 0603 SMD")
      (fields
        (field (name "MANUFACTURER") "Yageo")
        (field (name "MANUFACTURER PART NUMBER") "RC0603JR-07330RL")
      )
      (libsource (lib "TenergyLibrary") (part "Res 330 0603"))
    )
    (comp (ref "R60")
      (value "100")
      (footprint "6-0805_N")
      (description "RES 100 OHM 1/8W 5% 0805 SMD")
      (fields (field (name "TOLERANCE") "±5%"))
      (libsource (lib "TenergyLibrary") (part "Res 100 0805"))
    )
    (comp (ref "R61")
      (value "100")
      (footprint "1608[0603]")
      (description "RES 100 OHM 1/10W 5% 0603 SMD")
      (fields (field (name "TOLERANCE") "±5%"))
      (libsource (lib "TenergyLibrary") (part "Res 100 0603"))
    )
    (comp (ref "R62A")
      (value "68")
      (footprint "RES SM2512 W/ HEATSINK")
      (description "RES 68 OHM 1W 5% 2512 SMD")
      (fields
        (field (name "MANUFACTURER") "Panasonic Electronic Components")
        (field (name "MANUFACTURER PART NUMBER") "ERJ-1TYJ680U")
      )
      (libsource (lib "TenergyLibrary") (part "Res 68 2512"))
    )
    (comp (ref "R62B")
      (value "68")
      (footprint "RES SM2512 W/ HEATSINK")
      (description "RES 68 OHM 1W 5% 2512 SMD")
      (fields
        (field (name "MANUFACTURER") "Panasonic Electronic Components")
        (field (name "MANUFACTURER PART NUMBER") "ERJ-1TYJ680U")
      )
      (libsource (lib "TenergyLibrary") (part "Res 68 2512"))
    )
    (comp (ref "R62C")
      (value "68")
      (footprint "RES SM2512 W/ HEATSINK")
      (description "RES 68 OHM 1W 5% 2512 SMD")
      (fields
        (field (name "MANUFACTURER") "Panasonic Electronic Components")
        (field (name "MANUFACTURER PART NUMBER") "ERJ-1TYJ680U")
      )
      (libsource (lib "TenergyLibrary") (part "Res 68 2512"))
    )
    (comp (ref "R63")
      (value "510K")
      (footprint "6-0805_N")
      (description "RES 510K OHM 1/8W 5% SM0805")
      (fields
        (field (name "MANUFACTURER") "Yageo")
        (field (name "MANUFACTURER PART NUMBER") "RC0805JR-07510KL")
      )
      (libsource (lib "TenergyLibrary") (part "Res 510K 0805"))
    )
    (comp (ref "R64")
      (value "1")
      (footprint "1608[0603]")
      (description "RESISTOR, 1R, 100MW, 5%")
      (libsource (lib "TenergyLibrary") (part "Res 1 0603"))
    )
    (comp (ref "R65")
      (value "330")
      (footprint "1608[0603]")
      (description "RES 330 OHM 1/10W 5% 0603 SMD")
      (fields
        (field (name "MANUFACTURER") "Yageo")
        (field (name "MANUFACTURER PART NUMBER") "RC0603JR-07330RL")
      )
      (libsource (lib "TenergyLibrary") (part "Res 330 0603"))
    )
    (comp (ref "R66A")
      (value "68")
      (footprint "RES SM2512 W/ HEATSINK")
      (description "RES 68 OHM 1W 5% 2512 SMD")
      (fields
        (field (name "MANUFACTURER") "Panasonic Electronic Components")
        (field (name "MANUFACTURER PART NUMBER") "ERJ-1TYJ680U")
      )
      (libsource (lib "TenergyLibrary") (part "Res 68 2512"))
    )
    (comp (ref "R66B")
      (value "68")
      (footprint "RES SM2512 W/ HEATSINK")
      (description "RES 68 OHM 1W 5% 2512 SMD")
      (fields
        (field (name "MANUFACTURER") "Panasonic Electronic Components")
        (field (name "MANUFACTURER PART NUMBER") "ERJ-1TYJ680U")
      )
      (libsource (lib "TenergyLibrary") (part "Res 68 2512"))
    )
    (comp (ref "R66C")
      (value "68")
      (footprint "RES SM2512 W/ HEATSINK")
      (description "RES 68 OHM 1W 5% 2512 SMD")
      (fields
        (field (name "MANUFACTURER") "Panasonic Electronic Components")
        (field (name "MANUFACTURER PART NUMBER") "ERJ-1TYJ680U")
      )
      (libsource (lib "TenergyLibrary") (part "Res 68 2512"))
    )
    (comp (ref "R68")
      (value "51")
      (footprint "1608[0603]")
      (description "RES 51 OHM 1/10W 5% SM0603")
      (fields
        (field (name "MANUFACTURER") "Yageo")
        (field (name "MANUFACTURER PART NUMBER") "RC0603JR-0751RL")
      )
      (libsource (lib "TenergyLibrary") (part "Res 51 0603"))
    )
    (comp (ref "R69")
      (value "330")
      (footprint "1608[0603]")
      (description "RES 330 OHM 1/10W 5% 0603 SMD")
      (fields
        (field (name "MANUFACTURER") "Yageo")
        (field (name "MANUFACTURER PART NUMBER") "RC0603JR-07330RL")
      )
      (libsource (lib "TenergyLibrary") (part "Res 330 0603"))
    )
    (comp (ref "R70")
      (value "1K")
      (footprint "1608[0603]")
      (description "RES 1.00K OHM 1/10W 1% 0603 SMD")
      (fields (field (name "TOLERANCE") "¡À1%") (field (name "MANUFACTURER PART NUMBER") "RC0603FR-071KL"))
      (libsource (lib "TenergyLibrary") (part "Res 1K 0603"))
    )
    (comp (ref "R71")
      (value "1K")
      (footprint "1608[0603]")
      (description "RES 1.00K OHM 1/10W 1% 0603 SMD")
      (fields (field (name "TOLERANCE") "¡À1%") (field (name "MANUFACTURER PART NUMBER") "RC0603FR-071KL"))
      (libsource (lib "TenergyLibrary") (part "Res 1K 0603"))
    )
    (comp (ref "R72A")
      (value "68")
      (footprint "RES SM2512 W/ HEATSINK")
      (description "RES 68 OHM 1W 5% 2512 SMD")
      (fields
        (field (name "MANUFACTURER") "Panasonic Electronic Components")
        (field (name "MANUFACTURER PART NUMBER") "ERJ-1TYJ680U")
      )
      (libsource (lib "TenergyLibrary") (part "Res 68 2512"))
    )
    (comp (ref "R72B")
      (value "68")
      (footprint "RES SM2512 W/ HEATSINK")
      (description "RES 68 OHM 1W 5% 2512 SMD")
      (fields
        (field (name "MANUFACTURER") "Panasonic Electronic Components")
        (field (name "MANUFACTURER PART NUMBER") "ERJ-1TYJ680U")
      )
      (libsource (lib "TenergyLibrary") (part "Res 68 2512"))
    )
    (comp (ref "R72C")
      (value "68")
      (footprint "RES SM2512 W/ HEATSINK")
      (description "RES 68 OHM 1W 5% 2512 SMD")
      (fields
        (field (name "MANUFACTURER") "Panasonic Electronic Components")
        (field (name "MANUFACTURER PART NUMBER") "ERJ-1TYJ680U")
      )
      (libsource (lib "TenergyLibrary") (part "Res 68 2512"))
    )
    (comp (ref "R73")
      (value "330")
      (footprint "1608[0603]")
      (description "RES 330 OHM 1/10W 5% 0603 SMD")
      (fields
        (field (name "MANUFACTURER") "Yageo")
        (field (name "MANUFACTURER PART NUMBER") "RC0603JR-07330RL")
      )
      (libsource (lib "TenergyLibrary") (part "Res 330 0603"))
    )
    (comp (ref "R74A")
      (value "68")
      (footprint "RES SM2512 W/ HEATSINK")
      (description "RES 68 OHM 1W 5% 2512 SMD")
      (fields
        (field (name "MANUFACTURER") "Panasonic Electronic Components")
        (field (name "MANUFACTURER PART NUMBER") "ERJ-1TYJ680U")
      )
      (libsource (lib "TenergyLibrary") (part "Res 68 2512"))
    )
    (comp (ref "R74B")
      (value "68")
      (footprint "RES SM2512 W/ HEATSINK")
      (description "RES 68 OHM 1W 5% 2512 SMD")
      (fields
        (field (name "MANUFACTURER") "Panasonic Electronic Components")
        (field (name "MANUFACTURER PART NUMBER") "ERJ-1TYJ680U")
      )
      (libsource (lib "TenergyLibrary") (part "Res 68 2512"))
    )
    (comp (ref "R74C")
      (value "68")
      (footprint "RES SM2512 W/ HEATSINK")
      (description "RES 68 OHM 1W 5% 2512 SMD")
      (fields
        (field (name "MANUFACTURER") "Panasonic Electronic Components")
        (field (name "MANUFACTURER PART NUMBER") "ERJ-1TYJ680U")
      )
      (libsource (lib "TenergyLibrary") (part "Res 68 2512"))
    )
    (comp (ref "R75")
      (value "2M")
      (footprint "1608[0603]")
      (description "RES 2.0M OHM 1/10W 5% 0603 SMD")
      (fields (field (name "TOLERANCE") "±5%"))
      (libsource (lib "TenergyLibrary") (part "Res 2M 0603"))
    )
    (comp (ref "R76")
      (value "330")
      (footprint "1608[0603]")
      (description "RES 330 OHM 1/10W 5% 0603 SMD")
      (fields
        (field (name "MANUFACTURER") "Yageo")
        (field (name "MANUFACTURER PART NUMBER") "RC0603JR-07330RL")
      )
      (libsource (lib "TenergyLibrary") (part "Res 330 0603"))
    )
    (comp (ref "R77")
      (value "1M")
      (footprint "1608[0603]")
      (description "RES 1.0M OHM 1/10W 5% 0603 SMD")
      (fields (field (name "TOLERANCE") "±5%"))
      (libsource (lib "TenergyLibrary") (part "Res 1M 0603 5%"))
    )
    (comp (ref "R78A")
      (value "68")
      (footprint "RES SM2512 W/ HEATSINK")
      (description "RES 68 OHM 1W 5% 2512 SMD")
      (fields
        (field (name "MANUFACTURER") "Panasonic Electronic Components")
        (field (name "MANUFACTURER PART NUMBER") "ERJ-1TYJ680U")
      )
      (libsource (lib "TenergyLibrary") (part "Res 68 2512"))
    )
    (comp (ref "R78B")
      (value "68")
      (footprint "RES SM2512 W/ HEATSINK")
      (description "RES 68 OHM 1W 5% 2512 SMD")
      (fields
        (field (name "MANUFACTURER") "Panasonic Electronic Components")
        (field (name "MANUFACTURER PART NUMBER") "ERJ-1TYJ680U")
      )
      (libsource (lib "TenergyLibrary") (part "Res 68 2512"))
    )
    (comp (ref "R78C")
      (value "68")
      (footprint "RES SM2512 W/ HEATSINK")
      (description "RES 68 OHM 1W 5% 2512 SMD")
      (fields
        (field (name "MANUFACTURER") "Panasonic Electronic Components")
        (field (name "MANUFACTURER PART NUMBER") "ERJ-1TYJ680U")
      )
      (libsource (lib "TenergyLibrary") (part "Res 68 2512"))
    )
    (comp (ref "R79")
      (value "1M")
      (footprint "1608[0603]")
      (description "RES 1.0M OHM 1/10W 5% 0603 SMD")
      (fields (field (name "TOLERANCE") "±5%"))
      (libsource (lib "TenergyLibrary") (part "Res 1M 0603 5%"))
    )
    (comp (ref "R80")
      (value "2M")
      (footprint "1608[0603]")
      (description "RES 2.0M OHM 1/10W 5% 0603 SMD")
      (fields (field (name "TOLERANCE") "±5%"))
      (libsource (lib "TenergyLibrary") (part "Res 2M 0603"))
    )
    (comp (ref "R81")
      (value "330")
      (footprint "1608[0603]")
      (description "RES 330 OHM 1/10W 5% 0603 SMD")
      (fields
        (field (name "MANUFACTURER") "Yageo")
        (field (name "MANUFACTURER PART NUMBER") "RC0603JR-07330RL")
      )
      (libsource (lib "TenergyLibrary") (part "Res 330 0603"))
    )
    (comp (ref "R82A")
      (value "68")
      (footprint "RES SM2512 W/ HEATSINK")
      (description "RES 68 OHM 1W 5% 2512 SMD")
      (fields
        (field (name "MANUFACTURER") "Panasonic Electronic Components")
        (field (name "MANUFACTURER PART NUMBER") "ERJ-1TYJ680U")
      )
      (libsource (lib "TenergyLibrary") (part "Res 68 2512"))
    )
    (comp (ref "R82B")
      (value "68")
      (footprint "RES SM2512 W/ HEATSINK")
      (description "RES 68 OHM 1W 5% 2512 SMD")
      (fields
        (field (name "MANUFACTURER") "Panasonic Electronic Components")
        (field (name "MANUFACTURER PART NUMBER") "ERJ-1TYJ680U")
      )
      (libsource (lib "TenergyLibrary") (part "Res 68 2512"))
    )
    (comp (ref "R82C")
      (value "68")
      (footprint "RES SM2512 W/ HEATSINK")
      (description "RES 68 OHM 1W 5% 2512 SMD")
      (fields
        (field (name "MANUFACTURER") "Panasonic Electronic Components")
        (field (name "MANUFACTURER PART NUMBER") "ERJ-1TYJ680U")
      )
      (libsource (lib "TenergyLibrary") (part "Res 68 2512"))
    )
    (comp (ref "R83")
      (value "51")
      (footprint "C1206")
      (description "RES 51 OHM 5% 1/4W SM1206")
      (fields
        (field (name "MANUFACTURER") "Yageo")
        (field (name "MANUFACTURER PART NUMBER") "RC1206JR-0751RL")
      )
      (libsource (lib "TenergyLibrary") (part "Res 51 1206"))
    )
    (comp (ref "R84")
      (value "10K")
      (footprint "6-0805_N")
      (description "RES 10K OHM 1/8W 5% 0805 SMD")
      (fields (field (name "TOLERANCE") "±5%"))
      (libsource (lib "TenergyLibrary") (part "Res 10K 0805"))
    )
    (comp (ref "R85")
      (value "10K")
      (footprint "1608[0603]")
      (description "RES 10K OHM 1/10W 5% 0603 SMD")
      (fields (field (name "TOLERANCE") "±5%"))
      (libsource (lib "TenergyLibrary") (part "Res 10K 0603"))
    )
    (comp (ref "R86")
      (value "NP")
      (footprint "1608[0603]")
      (description "Do not Populate")
      (libsource (lib "TenergyLibrary") (part "Res NP 0603"))
    )
    (comp (ref "R87")
      (value "10K")
      (footprint "1608[0603]")
      (description "RES 10K OHM 1/10W 5% 0603 SMD")
      (fields (field (name "TOLERANCE") "±5%"))
      (libsource (lib "TenergyLibrary") (part "Res 10K 0603"))
    )
    (comp (ref "R88")
      (value "10M")
      (footprint "C1206")
      (description "RES 10.0M OHM 1/4W 1% 1206 SMD")
      (fields (field (name "TOLERANCE") "¡À1%"))
      (libsource (lib "TenergyLibrary") (part "Res 10M 1206"))
    )
    (comp (ref "R92")
      (value "2.2M")
      (footprint "C1206")
      (description "RES 2.2M OHM 1/4W 5% 1206 SMD")
      (fields (field (name "TOLERANCE") "±5%"))
      (libsource (lib "TenergyLibrary") (part "Res 2.2M 1206"))
    )
    (comp (ref "R93")
      (value "2.2M")
      (footprint "C1206")
      (description "RES 2.2M OHM 1/4W 5% 1206 SMD")
      (fields (field (name "TOLERANCE") "±5%"))
      (libsource (lib "TenergyLibrary") (part "Res 2.2M 1206"))
    )
    (comp (ref "R100")
      (value "100K")
      (footprint "1608[0603]")
      (description "RES 100K OHM 1/10W 1% 0603 SMD")
      (fields (field (name "TOLERANCE") "¡À1%"))
      (libsource (lib "TenergyLibrary") (part "Res 100K 0603"))
    )
    (comp (ref "R101")
      (value "270")
      (footprint "1608[0603]")
      (description "RES 270 OHM 1/10W 5% 0603 SMD")
      (fields (field (name "TOLERANCE") "±5%"))
      (libsource (lib "TenergyLibrary") (part "Res 270 0603"))
    )
    (comp (ref "R102")
      (value "150K")
      (footprint "1608[0603]")
      (description "RES 150K OHM 1/10W 1% 0603 SMD")
      (fields (field (name "TOLERANCE") "¡À1%") (field (name "MANUFACTURER PART NUMBER") "RC0603FR-07150KL"))
      (libsource (lib "TenergyLibrary") (part "Res 150K 0603"))
    )
    (comp (ref "R103")
      (value "20K")
      (footprint "1608[0603]")
      (description "RES 20.0K OHM 1/10W 1% 0603 SMD")
      (fields (field (name "TOLERANCE") "¡À1%"))
      (libsource (lib "TenergyLibrary") (part "Res 20K 0603"))
    )
    (comp (ref "R104")
      (value "100")
      (footprint "1608[0603]")
      (description "RES 100 OHM 1/10W 5% 0603 SMD")
      (fields (field (name "TOLERANCE") "±5%"))
      (libsource (lib "TenergyLibrary") (part "Res 100 0603"))
    )
    (comp (ref "R105")
      (value "2M")
      (footprint "1608[0603]")
      (description "RES 2.0M OHM 1/10W 5% 0603 SMD")
      (fields (field (name "TOLERANCE") "±5%"))
      (libsource (lib "TenergyLibrary") (part "Res 2M 0603"))
    )
    (comp (ref "R106")
      (value "100")
      (footprint "1608[0603]")
      (description "RES 100 OHM 1/10W 5% 0603 SMD")
      (fields (field (name "TOLERANCE") "±5%"))
      (libsource (lib "TenergyLibrary") (part "Res 100 0603"))
    )
    (comp (ref "R107")
      (value "NP")
      (footprint "1608[0603]")
      (description "Do not Populate")
      (libsource (lib "TenergyLibrary") (part "Res NP 0603"))
    )
    (comp (ref "R108")
      (value "51")
      (footprint "1608[0603]")
      (description "RES 51 OHM 1/10W 5% SM0603")
      (fields
        (field (name "MANUFACTURER") "Yageo")
        (field (name "MANUFACTURER PART NUMBER") "RC0603JR-0751RL")
      )
      (libsource (lib "TenergyLibrary") (part "Res 51 0603"))
    )
    (comp (ref "R109")
      (value "300")
      (footprint "1608[0603]")
      (description "RES 300 OHM 1/10W 5% 0603 SMD")
      (fields (field (name "TOLERANCE") "±5%"))
      (libsource (lib "TenergyLibrary") (part "Res 300 0603"))
    )
    (comp (ref "R110")
      (value "1M")
      (footprint "1608[0603]")
      (description "RES 1.0M OHM 1/10W 5% 0603 SMD")
      (fields (field (name "TOLERANCE") "±5%"))
      (libsource (lib "TenergyLibrary") (part "Res 1M 0603 5%"))
    )
    (comp (ref "R111")
      (value "2M")
      (footprint "1608[0603]")
      (description "RES 2.0M OHM 1/10W 5% 0603 SMD")
      (fields (field (name "TOLERANCE") "±5%"))
      (libsource (lib "TenergyLibrary") (part "Res 2M 0603"))
    )
    (comp (ref "R112")
      (value "1M")
      (footprint "1608[0603]")
      (description "RES 1.0M OHM 1/10W 5% 0603 SMD")
      (fields (field (name "TOLERANCE") "±5%"))
      (libsource (lib "TenergyLibrary") (part "Res 1M 0603 5%"))
    )
    (comp (ref "R113")
      (value "1M")
      (footprint "1608[0603]")
      (description "RES 1.0M OHM 1/10W 5% 0603 SMD")
      (fields (field (name "TOLERANCE") "±5%"))
      (libsource (lib "TenergyLibrary") (part "Res 1M 0603 5%"))
    )
    (comp (ref "R114")
      (value "300")
      (footprint "1608[0603]")
      (description "RES 300 OHM 1/10W 5% 0603 SMD")
      (fields (field (name "TOLERANCE") "±5%"))
      (libsource (lib "TenergyLibrary") (part "Res 300 0603"))
    )
    (comp (ref "R115")
      (value "100")
      (footprint "6-0805_N")
      (description "RES 100 OHM 1/8W 5% 0805 SMD")
      (fields (field (name "TOLERANCE") "±5%"))
      (libsource (lib "TenergyLibrary") (part "Res 100 0805"))
    )
    (comp (ref "R116")
      (value "100")
      (footprint "6-0805_N")
      (description "RES 100 OHM 1/8W 5% 0805 SMD")
      (fields (field (name "TOLERANCE") "±5%"))
      (libsource (lib "TenergyLibrary") (part "Res 100 0805"))
    )
    (comp (ref "R117")
      (value "20K")
      (footprint "1608[0603]")
      (description "RES 20.0K OHM 1/10W 1% 0603 SMD")
      (fields (field (name "TOLERANCE") "¡À1%"))
      (libsource (lib "TenergyLibrary") (part "Res 20K 0603"))
    )
    (comp (ref "R118")
      (value "20K")
      (footprint "1608[0603]")
      (description "RES 20.0K OHM 1/10W 1% 0603 SMD")
      (fields (field (name "TOLERANCE") "¡À1%"))
      (libsource (lib "TenergyLibrary") (part "Res 20K 0603"))
    )
    (comp (ref "R119")
      (value "51")
      (footprint "1608[0603]")
      (description "RES 51 OHM 1/10W 5% SM0603")
      (fields
        (field (name "MANUFACTURER") "Yageo")
        (field (name "MANUFACTURER PART NUMBER") "RC0603JR-0751RL")
      )
      (libsource (lib "TenergyLibrary") (part "Res 51 0603"))
    )
    (comp (ref "R120")
      (value "51")
      (footprint "1608[0603]")
      (description "RES 51 OHM 1/10W 5% SM0603")
      (fields
        (field (name "MANUFACTURER") "Yageo")
        (field (name "MANUFACTURER PART NUMBER") "RC0603JR-0751RL")
      )
      (libsource (lib "TenergyLibrary") (part "Res 51 0603"))
    )
    (comp (ref "R121")
      (value "100")
      (footprint "1608[0603]")
      (description "RES 100 OHM 1/10W 5% 0603 SMD")
      (fields (field (name "TOLERANCE") "±5%"))
      (libsource (lib "TenergyLibrary") (part "Res 100 0603"))
    )
    (comp (ref "R122")
      (value "100")
      (footprint "1608[0603]")
      (description "RES 100 OHM 1/10W 5% 0603 SMD")
      (fields (field (name "TOLERANCE") "±5%"))
      (libsource (lib "TenergyLibrary") (part "Res 100 0603"))
    )
    (comp (ref "R123")
      (value "100K")
      (footprint "1608[0603]")
      (description "RES 100K OHM 1/10W 1% 0603 SMD")
      (fields (field (name "TOLERANCE") "¡À1%"))
      (libsource (lib "TenergyLibrary") (part "Res 100K 0603"))
    )
    (comp (ref "R124")
      (value "10K")
      (footprint "1608[0603]")
      (description "RES 10K OHM 1/10W 5% 0603 SMD")
      (fields (field (name "TOLERANCE") "±5%"))
      (libsource (lib "TenergyLibrary") (part "Res 10K 0603"))
    )
    (comp (ref "R125")
      (value "1K")
      (footprint "1608[0603]")
      (description "RES 1.00K OHM 1/10W 1% 0603 SMD")
      (fields (field (name "TOLERANCE") "¡À1%") (field (name "MANUFACTURER PART NUMBER") "RC0603FR-071KL"))
      (libsource (lib "TenergyLibrary") (part "Res 1K 0603"))
    )
    (comp (ref "R126")
      (value "51")
      (footprint "1608[0603]")
      (description "RES 51 OHM 1/10W 5% SM0603")
      (fields
        (field (name "MANUFACTURER") "Yageo")
        (field (name "MANUFACTURER PART NUMBER") "RC0603JR-0751RL")
      )
      (libsource (lib "TenergyLibrary") (part "Res 51 0603"))
    )
    (comp (ref "R127")
      (value "10K")
      (footprint "1608[0603]")
      (description "RES 10K OHM 1/10W 5% 0603 SMD")
      (fields (field (name "TOLERANCE") "±5%"))
      (libsource (lib "TenergyLibrary") (part "Res 10K 0603"))
    )
    (comp (ref "R128")
      (value "8.2")
      (footprint "C1206")
      (description "RES 8.2 OHM 1/4W 5% 1206 SMD")
      (fields (field (name "TOLERANCE") "±5%"))
      (libsource (lib "TenergyLibrary") (part "Res 8.2 1206"))
    )
    (comp (ref "R129")
      (value "1K")
      (footprint "1608[0603]")
      (description "RES 1.00K OHM 1/10W 1% 0603 SMD")
      (fields (field (name "TOLERANCE") "¡À1%") (field (name "MANUFACTURER PART NUMBER") "RC0603FR-071KL"))
      (libsource (lib "TenergyLibrary") (part "Res 1K 0603"))
    )
    (comp (ref "R130")
      (value "1M")
      (footprint "1608[0603]")
      (description "RES 1.0M OHM 1/10W 5% 0603 SMD")
      (fields (field (name "TOLERANCE") "±5%"))
      (libsource (lib "TenergyLibrary") (part "Res 1M 0603 5%"))
    )
    (comp (ref "R131")
      (value "1M")
      (footprint "1608[0603]")
      (description "RES 1.0M OHM 1/10W 5% 0603 SMD")
      (fields (field (name "TOLERANCE") "±5%"))
      (libsource (lib "TenergyLibrary") (part "Res 1M 0603 5%"))
    )
    (comp (ref "R132")
      (value "NP")
      (footprint "1608[0603]")
      (description "Do not Populate")
      (libsource (lib "TenergyLibrary") (part "Res NP 0603"))
    )
    (comp (ref "R133")
      (value "NP")
      (footprint "6-0805_N")
      (description "Do not Populate")
      (libsource (lib "TenergyLibrary") (part "Res NP 0805"))
    )
    (comp (ref "R134")
      (value "0")
      (footprint "6-0805_N")
      (description "RES 0.0 OHM 1/10W 0603 SMD")
      (fields (field (name "MANUFACTURER PART NUMBER") "ERJ-3GEY0R00V") (field (name "TOLERANCE") "Jumper"))
      (libsource (lib "TenergyLibrary") (part "Res 0 0805"))
    )
    (comp (ref "R135")
      (value "200K")
      (footprint "1608[0603]")
      (description "RES 200K OHM 1/10W 1% 0603 SMD")
      (fields (field (name "TOLERANCE") "¡À1%"))
      (libsource (lib "TenergyLibrary") (part "Res 200K 0603"))
    )
    (comp (ref "R136")
      (value "2M")
      (footprint "1608[0603]")
      (description "RES 2.0M OHM 1/10W 5% 0603 SMD")
      (fields (field (name "TOLERANCE") "±5%"))
      (libsource (lib "TenergyLibrary") (part "Res 2M 0603"))
    )
    (comp (ref "R137")
      (value "2M")
      (footprint "1608[0603]")
      (description "RES 2.0M OHM 1/10W 5% 0603 SMD")
      (fields (field (name "TOLERANCE") "±5%"))
      (libsource (lib "TenergyLibrary") (part "Res 2M 0603"))
    )
    (comp (ref "R138")
      (value "2M")
      (footprint "1608[0603]")
      (description "RES 2.0M OHM 1/10W 5% 0603 SMD")
      (fields (field (name "TOLERANCE") "±5%"))
      (libsource (lib "TenergyLibrary") (part "Res 2M 0603"))
    )
    (comp (ref "R139")
      (value "2M")
      (footprint "1608[0603]")
      (description "RES 2.0M OHM 1/10W 5% 0603 SMD")
      (fields (field (name "TOLERANCE") "±5%"))
      (libsource (lib "TenergyLibrary") (part "Res 2M 0603"))
    )
    (comp (ref "R140")
      (value "510K")
      (footprint "1608[0603]")
      (description "RES 510K OHM 1/10W 5% 0603 SMD")
      (fields (field (name "TOLERANCE") "±5%"))
      (libsource (lib "TenergyLibrary") (part "Res 510K 0603"))
    )
    (comp (ref "R141")
      (value "510K")
      (footprint "1608[0603]")
      (description "RES 510K OHM 1/10W 5% 0603 SMD")
      (fields (field (name "TOLERANCE") "±5%"))
      (libsource (lib "TenergyLibrary") (part "Res 510K 0603"))
    )
    (comp (ref "R142")
      (value "3M")
      (footprint "1608[0603]")
      (description "RES 3M OHM 1/10W 5% 0603 SMD")
      (fields (field (name "TOLERANCE") "±5%"))
      (libsource (lib "TenergyLibrary") (part "Res 3M 0603"))
    )
    (comp (ref "R143")
      (value "3M")
      (footprint "1608[0603]")
      (description "RES 3M OHM 1/10W 5% 0603 SMD")
      (fields (field (name "TOLERANCE") "±5%"))
      (libsource (lib "TenergyLibrary") (part "Res 3M 0603"))
    )
    (comp (ref "R144")
      (value "3M")
      (footprint "1608[0603]")
      (description "RES 3M OHM 1/10W 5% 0603 SMD")
      (fields (field (name "TOLERANCE") "±5%"))
      (libsource (lib "TenergyLibrary") (part "Res 3M 0603"))
    )
    (comp (ref "R145")
      (value "18K")
      (footprint "RES SM2512 W/ HEATSINK")
      (description "RES 18K OHM 1W 5% 2512 SMD")
      (fields (field (name "TOLERANCE") "±5%"))
      (libsource (lib "TenergyLibrary") (part "Res 18K 2512"))
    )
    (comp (ref "R146")
      (value "18K")
      (footprint "RES SM2512 W/ HEATSINK")
      (description "RES 18K OHM 1W 5% 2512 SMD")
      (fields (field (name "TOLERANCE") "±5%"))
      (libsource (lib "TenergyLibrary") (part "Res 18K 2512"))
    )
    (comp (ref "R147")
      (value "18K")
      (footprint "RES SM2512 W/ HEATSINK")
      (description "RES 18K OHM 1W 5% 2512 SMD")
      (fields (field (name "TOLERANCE") "±5%"))
      (libsource (lib "TenergyLibrary") (part "Res 18K 2512"))
    )
    (comp (ref "R148")
      (value "0.008")
      (footprint "C2512")
      (description "RES .008 OHM 1W 1% 2512 SMD")
      (fields (field (name "TOLERANCE") "¡À1%") (field (name "MANUFACTURER PART NUMBER") "WSL25128L000FEA"))
      (libsource (lib "TenergyLibrary") (part "Res 0.008 2512"))
    )
    (comp (ref "R149")
      (value "0.008")
      (footprint "C2512")
      (description "RES .008 OHM 1W 1% 2512 SMD")
      (fields (field (name "TOLERANCE") "¡À1%") (field (name "MANUFACTURER PART NUMBER") "WSL25128L000FEA"))
      (libsource (lib "TenergyLibrary") (part "Res 0.008 2512"))
    )
    (comp (ref "R150")
      (value "0.008")
      (footprint "C2512")
      (description "RES .008 OHM 1W 1% 2512 SMD")
      (fields (field (name "TOLERANCE") "¡À1%") (field (name "MANUFACTURER PART NUMBER") "WSL25128L000FEA"))
      (libsource (lib "TenergyLibrary") (part "Res 0.008 2512"))
    )
    (comp (ref "R151")
      (value "0.008")
      (footprint "C2512")
      (description "RES .008 OHM 1W 1% 2512 SMD")
      (fields (field (name "TOLERANCE") "¡À1%") (field (name "MANUFACTURER PART NUMBER") "WSL25128L000FEA"))
      (libsource (lib "TenergyLibrary") (part "Res 0.008 2512"))
    )
    (comp (ref "R152")
      (value "100K")
      (footprint "1608[0603]")
      (description "RES 100K OHM 1/10W 1% 0603 SMD")
      (fields (field (name "TOLERANCE") "¡À1%"))
      (libsource (lib "TenergyLibrary") (part "Res 100K 0603"))
    )
    (comp (ref "TP1")
      (value "Test Point VIA")
      (footprint "TEST POINT 60/37 .025 VIA")
      (libsource (lib "TenergyLibrary") (part "Test Point VIA"))
    )
    (comp (ref "TP2")
      (value "Test Point VIA")
      (footprint "TEST POINT 60/37 .025 VIA")
      (libsource (lib "TenergyLibrary") (part "Test Point VIA"))
    )
    (comp (ref "TP100")
      (value "Test Point SMT")
      (footprint "TEST_POINT_SM_4.7MMX3.4MM")
      (description "TEST POINT, SMT")
      (fields
        (field (name "MANUFACTURER") "Keystone Electronics")
        (field (name "MANUFACTURER PART NUMBER") "5016")
      )
      (libsource (lib "TenergyLibrary") (part "Test Point SMT"))
    )
    (comp (ref "TP101")
      (value "Test Point VIA")
      (footprint "TEST POINT 60/37 .025 VIA")
      (libsource (lib "TenergyLibrary") (part "Test Point VIA"))
    )
    (comp (ref "TP102")
      (value "Test Point VIA")
      (footprint "TEST POINT 60/37 .025 VIA")
      (libsource (lib "TenergyLibrary") (part "Test Point VIA"))
    )
    (comp (ref "TP103")
      (value "Test Point VIA")
      (footprint "TEST POINT 60/37 .025 VIA")
      (libsource (lib "TenergyLibrary") (part "Test Point VIA"))
    )
    (comp (ref "TP104")
      (value "Test Point VIA")
      (footprint "TEST POINT 60/37 .025 VIA")
      (libsource (lib "TenergyLibrary") (part "Test Point VIA"))
    )
    (comp (ref "TP105")
      (value "Test Point VIA")
      (footprint "TEST POINT 60/37 .025 VIA")
      (libsource (lib "TenergyLibrary") (part "Test Point VIA"))
    )
    (comp (ref "TP106")
      (value "Test Point VIA")
      (footprint "TEST POINT 60/37 .025 VIA")
      (libsource (lib "TenergyLibrary") (part "Test Point VIA"))
    )
    (comp (ref "TP107")
      (value "Test Point VIA")
      (footprint "TEST POINT 60/37 .025 VIA")
      (libsource (lib "TenergyLibrary") (part "Test Point VIA"))
    )
    (comp (ref "TP108")
      (value "Test Point VIA")
      (footprint "TEST POINT 60/37 .025 VIA")
      (libsource (lib "TenergyLibrary") (part "Test Point VIA"))
    )
    (comp (ref "TP109")
      (value "Test Point VIA")
      (footprint "TEST POINT 60/37 .025 VIA")
      (libsource (lib "TenergyLibrary") (part "Test Point VIA"))
    )
    (comp (ref "TP110")
      (value "Test Point VIA")
      (footprint "TEST POINT 60/37 .025 VIA")
      (libsource (lib "TenergyLibrary") (part "Test Point VIA"))
    )
    (comp (ref "TP111")
      (value "Test Point VIA")
      (footprint "TEST POINT 60/37 .025 VIA")
      (libsource (lib "TenergyLibrary") (part "Test Point VIA"))
    )
    (comp (ref "TP112")
      (value "Test Point VIA")
      (footprint "TEST POINT 60/37 .025 VIA")
      (libsource (lib "TenergyLibrary") (part "Test Point VIA"))
    )
    (comp (ref "TP113")
      (value "Test Point VIA")
      (footprint "TEST POINT 60/37 .025 VIA")
      (libsource (lib "TenergyLibrary") (part "Test Point VIA"))
    )
    (comp (ref "TP114")
      (value "Test Point VIA")
      (footprint "TEST POINT 60/37 .025 VIA")
      (libsource (lib "TenergyLibrary") (part "Test Point VIA"))
    )
    (comp (ref "TP115")
      (value "Test Point VIA")
      (footprint "TEST POINT 60/37 .025 VIA")
      (libsource (lib "TenergyLibrary") (part "Test Point VIA"))
    )
    (comp (ref "TP116")
      (value "Test Point VIA")
      (footprint "TEST POINT 60/37 .025 VIA")
      (libsource (lib "TenergyLibrary") (part "Test Point VIA"))
    )
    (comp (ref "TP117")
      (value "Test Point VIA")
      (footprint "TEST POINT 60/37 .025 VIA")
      (libsource (lib "TenergyLibrary") (part "Test Point VIA"))
    )
    (comp (ref "TP118")
      (value "Test Point VIA")
      (footprint "TEST POINT 60/37 .025 VIA")
      (libsource (lib "TenergyLibrary") (part "Test Point VIA"))
    )
    (comp (ref "TP119")
      (value "Test Point VIA")
      (footprint "TEST POINT 60/37 .025 VIA")
      (libsource (lib "TenergyLibrary") (part "Test Point VIA"))
    )
    (comp (ref "TP120")
      (value "Test Point VIA")
      (footprint "TEST POINT 60/37 .025 VIA")
      (libsource (lib "TenergyLibrary") (part "Test Point VIA"))
    )
    (comp (ref "TP121")
      (value "Test Point VIA")
      (footprint "TEST POINT 60/37 .025 VIA")
      (libsource (lib "TenergyLibrary") (part "Test Point VIA"))
    )
    (comp (ref "TP122")
      (value "Test Point VIA")
      (footprint "TEST POINT 60/37 .025 VIA")
      (libsource (lib "TenergyLibrary") (part "Test Point VIA"))
    )
    (comp (ref "TR100")
      (value "10K")
      (footprint "RES SM2512 W/ HEATSINK")
      (description "Thick Film Resistors - SMD 18K OHM 5%")
      (fields (field (name "TOLERANCE") "10 %"))
      (libsource (lib "TenergyLibrary") (part "Thermister 10K"))
    )
    (comp (ref "TR101")
      (value "10K")
      (footprint "RES SM2512 W/ HEATSINK")
      (description "Thick Film Resistors - SMD 18K OHM 5%")
      (fields (field (name "TOLERANCE") "10 %"))
      (libsource (lib "TenergyLibrary") (part "Thermister 10K"))
    )
    (comp (ref "U1")
      (value "R5432")
      (footprint "TSSOP-24 (TSSOP065P600-24N")
      (description "IC, BATTERY PROT, LI+, SSOP-24")
      (fields (field (name "MANUFACTURER") "Ricoh") (field (name "MANUFACTURERS PART NUMBER") "R5432V"))
      (libsource (lib "TenergyLibrary") (part "Battery Protection R5432"))
    )
    (comp (ref "U2")
      (value "LP2901M")
      (footprint "LM2901M (SOP127P600-14N)")
      (description "IC COMPARATOR QUAD LOW POWER 14-SOP")
      (fields
        (field (name "MANUFACTURER") "Texas Instruments")
        (field (name "MANUFACTURER PART NUMBER") "LP2901DR")
      )
      (libsource (lib "TenergyLibrary") (part "Comparator LM2901M"))
    )
    (comp (ref "U3")
      (value "R5432")
      (footprint "TSSOP-24 (TSSOP065P600-24N")
      (description "IC, BATTERY PROT, LI+, SSOP-24")
      (fields (field (name "MANUFACTURER") "Ricoh") (field (name "MANUFACTURERS PART NUMBER") "R5432V"))
      (libsource (lib "TenergyLibrary") (part "Battery Protection R5432"))
    )
    (comp (ref "U4")
      (value "4N25")
      (footprint "4N25SM (SOIC254P1020X460-6N)")
      (description "OPTOCOUPLER TRANS-OUT 6-SMD")
      (fields
        (field (name "MANUFACTURER") "Fairchild Semiconductor")
        (field (name "MANUFACTURER PART NUMBER") "4N25SR2M")
      )
      (libsource (lib "TenergyLibrary") (part "Optocoupler 4N25"))
    )
    (comp (ref "U5")
      (value "R5432")
      (footprint "TSSOP-24 (TSSOP065P600-24N")
      (description "IC, BATTERY PROT, LI+, SSOP-24")
      (fields (field (name "MANUFACTURER") "Ricoh") (field (name "MANUFACTURERS PART NUMBER") "R5432V"))
      (libsource (lib "TenergyLibrary") (part "Battery Protection R5432"))
    )
    (comp (ref "U6")
      (value "BQ34Z100")
      (footprint "BQ34Z100 (TSSOP-14)")
      (description "IC BATT MGMT LIION/LPO4 14TSSOP")
      (fields
        (field (name "MANUFACTURER") "Texas Instruments")
        (field (name "MANUFACTURER PART NUMBER") "BQ34Z100PW")
      )
      (libsource (lib "TenergyLibrary") (part "BQ34Z100"))
    )
    (comp (ref "U7")
      (value "R5432")
      (footprint "TSSOP-24 (TSSOP065P600-24N")
      (description "IC, BATTERY PROT, LI+, SSOP-24")
      (fields (field (name "MANUFACTURER") "Ricoh") (field (name "MANUFACTURERS PART NUMBER") "R5432V"))
      (libsource (lib "TenergyLibrary") (part "Battery Protection R5432"))
    )
    (comp (ref "U100")
      (value "S-812C33BMC")
      (footprint "S-812C (SOT23-5)")
      (description "IC REG LDO 3.3V 50MA SOT23-5")
      (libsource (lib "TenergyLibrary") (part "Regulator S-812C33BMC-C4NT2G"))
    )
    (comp (ref "U101")
      (value "MAX11603EEE")
      (footprint "MAX11603EEE (QSOP0635P600-16N)")
      (description "IC ADC SERIAL 8BIT 8CH 16-QSOP")
      (fields
        (field (name "MANUFACTURER") "Maxim Integrated")
        (field (name "MANUFACTURER PART NUMBER") "MAX11603EEE+")
      )
      (libsource (lib "TenergyLibrary") (part "ADC MAX11603"))
    )
    (comp (ref "U102")
      (value "AT24C08C")
      (footprint "AT24C0xC-STUM-T (SOT23-5)")
      (description "IC EEPROM 8KBIT 400KHZ SOT23-5")
      (fields
        (field (name "MANUFACTURER") "Atmel")
        (field (name "MANUFACTURER PART NUMBER") "AT24C08C-STUM-T")
      )
      (libsource (lib "TenergyLibrary") (part "EEPROM AT24C02C"))
    )
    (comp (ref "U103")
      (value "IXDD609SIA")
      (footprint "SOIC127P600-8AM")
      (description "IC GATE DVR 9A NON-INV 8-SOIC")
      (fields (field (name "MANUFACTURER") "IXYS Integrated Circuits Division"))
      (libsource (lib "TenergyLibrary") (part "Gate DVR IXDD609SIA"))
    )
    (comp (ref "U104")
      (value "IXDD609SIA")
      (footprint "SOIC127P600-8AM")
      (description "IC GATE DVR 9A NON-INV 8-SOIC")
      (fields (field (name "MANUFACTURER") "IXYS Integrated Circuits Division"))
      (libsource (lib "TenergyLibrary") (part "Gate DVR IXDD609SIA"))
    )
  )
  (nets
    (net (code "1") (name "/AL") (class "Default")
      (node (ref "C48") (pin "2") (pinfunction "2_2") (pintype "passive"))
      (node (ref "C49") (pin "1") (pinfunction "1_1") (pintype "passive"))
      (node (ref "R92") (pin "2") (pinfunction "2_2") (pintype "passive"))
      (node (ref "R93") (pin "1") (pinfunction "1_1") (pintype "passive"))
    )
    (net (code "2") (name "/ALUM_PLATE") (class "Default")
      (node (ref "C49") (pin "2") (pinfunction "2_2") (pintype "passive"))
      (node (ref "R93") (pin "2") (pinfunction "2_2") (pintype "passive"))
    )
    (net (code "3") (name "/BATT_VLT_MON") (class "Default")
      (node (ref "C107") (pin "2") (pinfunction "2_2") (pintype "passive"))
      (node (ref "R52") (pin "1") (pinfunction "1_1") (pintype "passive"))
      (node (ref "R58") (pin "2") (pinfunction "2_2") (pintype "passive"))
      (node (ref "U6") (pin "4") (pinfunction "BAT_4") (pintype "input"))
    )
    (net (code "5") (name "/CELL01P") (class "Default")
      (node (ref "C127") (pin "1") (pinfunction "1_1") (pintype "passive"))
      (node (ref "P1") (pin "26") (pinfunction "26_26") (pintype "passive"))
      (node (ref "Q25") (pin "2") (pinfunction "S_2") (pintype "passive"))
      (node (ref "R81") (pin "1") (pinfunction "1_1") (pintype "passive"))
      (node (ref "R82A") (pin "2") (pinfunction "2_2") (pintype "passive"))
      (node (ref "R82B") (pin "2") (pinfunction "2_2") (pintype "passive"))
      (node (ref "R82C") (pin "2") (pinfunction "2_2") (pintype "passive"))
    )
    (net (code "6") (name "/CELL01_DSCHG_EN") (class "Default")
      (node (ref "C128") (pin "2") (pinfunction "2_2") (pintype "passive"))
      (node (ref "Q26") (pin "1") (pinfunction "G_1") (pintype "passive"))
      (node (ref "U7") (pin "16") (pinfunction "CB4_16") (pintype "passive"))
    )
    (net (code "7") (name "/CELL02P") (class "Default")
      (node (ref "C126") (pin "1") (pinfunction "1_1") (pintype "passive"))
      (node (ref "P1") (pin "27") (pinfunction "27_27") (pintype "passive"))
      (node (ref "Q22") (pin "2") (pinfunction "S_2") (pintype "passive"))
      (node (ref "R76") (pin "1") (pinfunction "1_1") (pintype "passive"))
      (node (ref "R78A") (pin "2") (pinfunction "2_2") (pintype "passive"))
      (node (ref "R78B") (pin "2") (pinfunction "2_2") (pintype "passive"))
      (node (ref "R78C") (pin "2") (pinfunction "2_2") (pintype "passive"))
    )
    (net (code "8") (name "/CELL02_DSCHG_EN") (class "Default")
      (node (ref "C127") (pin "2") (pinfunction "2_2") (pintype "passive"))
      (node (ref "Q25") (pin "1") (pinfunction "G_1") (pintype "passive"))
      (node (ref "U7") (pin "18") (pinfunction "CB3_18") (pintype "passive"))
    )
    (net (code "9") (name "/CELL03P") (class "Default")
      (node (ref "C125") (pin "1") (pinfunction "1_1") (pintype "passive"))
      (node (ref "P1") (pin "24") (pinfunction "24_24") (pintype "passive"))
      (node (ref "Q21") (pin "2") (pinfunction "S_2") (pintype "passive"))
      (node (ref "R73") (pin "1") (pinfunction "1_1") (pintype "passive"))
      (node (ref "R74A") (pin "2") (pinfunction "2_2") (pintype "passive"))
      (node (ref "R74B") (pin "2") (pinfunction "2_2") (pintype "passive"))
      (node (ref "R74C") (pin "2") (pinfunction "2_2") (pintype "passive"))
    )
    (net (code "10") (name "/CELL03_DSCHG_EN") (class "Default")
      (node (ref "C126") (pin "2") (pinfunction "2_2") (pintype "passive"))
      (node (ref "Q22") (pin "1") (pinfunction "G_1") (pintype "passive"))
      (node (ref "U7") (pin "20") (pinfunction "CB2_20") (pintype "passive"))
    )
    (net (code "11") (name "/CELL04P") (class "Default")
      (node (ref "C122") (pin "2") (pinfunction "2_2") (pintype "passive"))
      (node (ref "C24") (pin "2") (pinfunction "2_2") (pintype "passive"))
      (node (ref "C37") (pin "1") (pinfunction "1_1") (pintype "passive"))
      (node (ref "C38") (pin "2") (pinfunction "2_2") (pintype "passive"))
      (node (ref "C39") (pin "2") (pinfunction "2_2") (pintype "passive"))
      (node (ref "D112") (pin "2") (pinfunction "A_2") (pintype "passive"))
      (node (ref "D121") (pin "1") (pinfunction "A_1") (pintype "passive"))
      (node (ref "DZ4") (pin "1") (pinfunction "A_1") (pintype "passive"))
      (node (ref "P1") (pin "25") (pinfunction "25_25") (pintype "passive"))
      (node (ref "Q20") (pin "2") (pinfunction "S_2") (pintype "passive"))
      (node (ref "Q23") (pin "2") (pinfunction "S_2") (pintype "passive"))
      (node (ref "R124") (pin "2") (pinfunction "2_2") (pintype "passive"))
      (node (ref "R144") (pin "2") (pinfunction "2_2") (pintype "passive"))
      (node (ref "R68") (pin "1") (pinfunction "1_1") (pintype "passive"))
      (node (ref "R69") (pin "1") (pinfunction "1_1") (pintype "passive"))
      (node (ref "R72A") (pin "2") (pinfunction "2_2") (pintype "passive"))
      (node (ref "R72B") (pin "2") (pinfunction "2_2") (pintype "passive"))
      (node (ref "R72C") (pin "2") (pinfunction "2_2") (pintype "passive"))
      (node (ref "R75") (pin "2") (pinfunction "2_2") (pintype "passive"))
      (node (ref "U5") (pin "11") (pinfunction "CT2_11") (pintype "passive"))
      (node (ref "U5") (pin "12") (pinfunction "SEL1_12") (pintype "passive"))
      (node (ref "U5") (pin "15") (pinfunction "VC5_15") (pintype "passive"))
      (node (ref "U5") (pin "4") (pinfunction "VMP_4") (pintype "passive"))
      (node (ref "U5") (pin "7") (pinfunction "SENS_7") (pintype "passive"))
      (node (ref "U5") (pin "9") (pinfunction "Vss_9") (pintype "passive"))
    )
    (net (code "12") (name "/CELL04_DSCHG_EN") (class "Default")
      (node (ref "C125") (pin "2") (pinfunction "2_2") (pintype "passive"))
      (node (ref "Q21") (pin "1") (pinfunction "G_1") (pintype "passive"))
      (node (ref "U7") (pin "22") (pinfunction "CB1_22") (pintype "passive"))
    )
    (net (code "13") (name "/CELL05P") (class "Default")
      (node (ref "P1") (pin "22") (pinfunction "22_22") (pintype "passive"))
    )
    (net (code "14") (name "/CELL05_DSCHG_EN") (class "Default")
      (node (ref "C122") (pin "1") (pinfunction "1_1") (pintype "passive"))
      (node (ref "Q20") (pin "1") (pinfunction "G_1") (pintype "passive"))
      (node (ref "U5") (pin "16") (pinfunction "CB4_16") (pintype "passive"))
    )
    (net (code "15") (name "/CELL06P") (class "Default")
      (node (ref "P1") (pin "23") (pinfunction "23_23") (pintype "passive"))
    )
    (net (code "16") (name "/CELL06_DSCHG_EN") (class "Default")
      (node (ref "C121") (pin "2") (pinfunction "2_2") (pintype "passive"))
      (node (ref "Q19") (pin "1") (pinfunction "G_1") (pintype "passive"))
      (node (ref "U5") (pin "18") (pinfunction "CB3_18") (pintype "passive"))
    )
    (net (code "17") (name "/CELL07P") (class "Default")
      (node (ref "P1") (pin "20") (pinfunction "20_20") (pintype "passive"))
    )
    (net (code "18") (name "/CELL07_DSCHG_EN") (class "Default")
      (node (ref "C120") (pin "2") (pinfunction "2_2") (pintype "passive"))
      (node (ref "Q17") (pin "1") (pinfunction "G_1") (pintype "passive"))
      (node (ref "U5") (pin "20") (pinfunction "CB2_20") (pintype "passive"))
    )
    (net (code "19") (name "/CELL08P") (class "Default")
      (node (ref "C118") (pin "1") (pinfunction "1_1") (pintype "passive"))
      (node (ref "C13") (pin "2") (pinfunction "2_2") (pintype "passive"))
      (node (ref "C21") (pin "1") (pinfunction "1_1") (pintype "passive"))
      (node (ref "C22") (pin "2") (pinfunction "2_2") (pintype "passive"))
      (node (ref "C23") (pin "2") (pinfunction "2_2") (pintype "passive"))
      (node (ref "D108") (pin "2") (pinfunction "A_2") (pintype "passive"))
      (node (ref "DZ2") (pin "1") (pinfunction "A_1") (pintype "passive"))
      (node (ref "P1") (pin "21") (pinfunction "21_21") (pintype "passive"))
      (node (ref "Q13") (pin "2") (pinfunction "S_2") (pintype "passive"))
      (node (ref "R143") (pin "2") (pinfunction "2_2") (pintype "passive"))
      (node (ref "R40") (pin "1") (pinfunction "1_1") (pintype "passive"))
      (node (ref "R41") (pin "1") (pinfunction "1_1") (pintype "passive"))
      (node (ref "R44A") (pin "2") (pinfunction "2_2") (pintype "passive"))
      (node (ref "R44B") (pin "2") (pinfunction "2_2") (pintype "passive"))
      (node (ref "R44C") (pin "2") (pinfunction "2_2") (pintype "passive"))
      (node (ref "U3") (pin "11") (pinfunction "CT2_11") (pintype "passive"))
      (node (ref "U3") (pin "12") (pinfunction "SEL1_12") (pintype "passive"))
      (node (ref "U3") (pin "15") (pinfunction "VC5_15") (pintype "passive"))
      (node (ref "U3") (pin "4") (pinfunction "VMP_4") (pintype "passive"))
      (node (ref "U3") (pin "7") (pinfunction "SENS_7") (pintype "passive"))
      (node (ref "U3") (pin "9") (pinfunction "Vss_9") (pintype "passive"))
    )
    (net (code "20") (name "/CELL08_DSCHG_EN") (class "Default")
      (node (ref "C119") (pin "2") (pinfunction "2_2") (pintype "passive"))
      (node (ref "Q15") (pin "1") (pinfunction "G_1") (pintype "passive"))
      (node (ref "U5") (pin "22") (pinfunction "CB1_22") (pintype "passive"))
    )
    (net (code "21") (name "/CELL09P") (class "Default")
      (node (ref "P1") (pin "8") (pinfunction "8_8") (pintype "passive"))
    )
    (net (code "22") (name "/CELL09_DSCHG_EN") (class "Default")
      (node (ref "C118") (pin "2") (pinfunction "2_2") (pintype "passive"))
      (node (ref "Q13") (pin "1") (pinfunction "G_1") (pintype "passive"))
      (node (ref "U3") (pin "16") (pinfunction "CB4_16") (pintype "passive"))
    )
    (net (code "23") (name "/CELL10P") (class "Default")
      (node (ref "P1") (pin "7") (pinfunction "7_7") (pintype "passive"))
    )
    (net (code "24") (name "/CELL10_DSCHG_EN") (class "Default")
      (node (ref "C117") (pin "1") (pinfunction "1_1") (pintype "passive"))
      (node (ref "Q12") (pin "1") (pinfunction "G_1") (pintype "passive"))
      (node (ref "U3") (pin "18") (pinfunction "CB3_18") (pintype "passive"))
    )
    (net (code "25") (name "/CELL11P") (class "Default")
      (node (ref "P1") (pin "6") (pinfunction "6_6") (pintype "passive"))
    )
    (net (code "26") (name "/CELL11_DSCHG_EN") (class "Default")
      (node (ref "C116") (pin "1") (pinfunction "1_1") (pintype "passive"))
      (node (ref "Q11") (pin "1") (pinfunction "G_1") (pintype "passive"))
      (node (ref "U3") (pin "20") (pinfunction "CB2_20") (pintype "passive"))
    )
    (net (code "27") (name "/CELL12P") (class "Default")
      (node (ref "P1") (pin "5") (pinfunction "5_5") (pintype "passive"))
    )
    (net (code "28") (name "/CELL12_DSCHG_EN") (class "Default")
      (node (ref "C115") (pin "1") (pinfunction "1_1") (pintype "passive"))
      (node (ref "Q8") (pin "1") (pinfunction "G_1") (pintype "passive"))
      (node (ref "U3") (pin "22") (pinfunction "CB1_22") (pintype "passive"))
    )
    (net (code "29") (name "/CELL13P") (class "Default")
      (node (ref "C111") (pin "1") (pinfunction "1_1") (pintype "passive"))
      (node (ref "P1") (pin "4") (pinfunction "4_4") (pintype "passive"))
      (node (ref "Q4") (pin "2") (pinfunction "S_2") (pintype "passive"))
      (node (ref "R16") (pin "1") (pinfunction "1_1") (pintype "passive"))
      (node (ref "R17A") (pin "2") (pinfunction "2_2") (pintype "passive"))
      (node (ref "R17B") (pin "2") (pinfunction "2_2") (pintype "passive"))
      (node (ref "R17C") (pin "2") (pinfunction "2_2") (pintype "passive"))
    )
    (net (code "30") (name "/CELL13_DSCHG_EN") (class "Default")
      (node (ref "C112") (pin "1") (pinfunction "1_1") (pintype "passive"))
      (node (ref "Q6") (pin "1") (pinfunction "G_1") (pintype "passive"))
      (node (ref "U1") (pin "16") (pinfunction "CB4_16") (pintype "passive"))
    )
    (net (code "31") (name "/CELL14P") (class "Default")
      (node (ref "C110") (pin "1") (pinfunction "1_1") (pintype "passive"))
      (node (ref "P1") (pin "3") (pinfunction "3_3") (pintype "passive"))
      (node (ref "Q2") (pin "2") (pinfunction "S_2") (pintype "passive"))
      (node (ref "R10A") (pin "2") (pinfunction "2_2") (pintype "passive"))
      (node (ref "R10B") (pin "2") (pinfunction "2_2") (pintype "passive"))
      (node (ref "R10C") (pin "2") (pinfunction "2_2") (pintype "passive"))
      (node (ref "R9") (pin "1") (pinfunction "1_1") (pintype "passive"))
    )
    (net (code "32") (name "/CELL14_DSCHG_EN") (class "Default")
      (node (ref "C111") (pin "2") (pinfunction "2_2") (pintype "passive"))
      (node (ref "Q4") (pin "1") (pinfunction "G_1") (pintype "passive"))
      (node (ref "U1") (pin "18") (pinfunction "CB3_18") (pintype "passive"))
    )
    (net (code "33") (name "/CELL15P") (class "Default")
      (node (ref "C109") (pin "1") (pinfunction "1_1") (pintype "passive"))
      (node (ref "P1") (pin "2") (pinfunction "2_2") (pintype "passive"))
      (node (ref "Q1") (pin "2") (pinfunction "S_2") (pintype "passive"))
      (node (ref "R4") (pin "1") (pinfunction "1_1") (pintype "passive"))
      (node (ref "R5A") (pin "2") (pinfunction "2_2") (pintype "passive"))
      (node (ref "R5B") (pin "2") (pinfunction "2_2") (pintype "passive"))
      (node (ref "R5C") (pin "2") (pinfunction "2_2") (pintype "passive"))
    )
    (net (code "34") (name "/CELL15_DSCHG_EN") (class "Default")
      (node (ref "C110") (pin "2") (pinfunction "2_2") (pintype "passive"))
      (node (ref "Q2") (pin "1") (pinfunction "G_1") (pintype "passive"))
      (node (ref "U1") (pin "20") (pinfunction "CB2_20") (pintype "passive"))
    )
    (net (code "35") (name "/CELL16_DSCHG_EN") (class "Default")
      (node (ref "C109") (pin "2") (pinfunction "2_2") (pintype "passive"))
      (node (ref "Q1") (pin "1") (pinfunction "G_1") (pintype "passive"))
      (node (ref "U1") (pin "22") (pinfunction "CB1_22") (pintype "passive"))
    )
    (net (code "36") (name "/CELLN_OUT") (class "Default")
      (node (ref "C30") (pin "1") (pinfunction "1_1") (pintype "passive"))
      (node (ref "F100") (pin "2") (pinfunction "B_2") (pintype "passive"))
      (node (ref "F101") (pin "2") (pinfunction "B_2") (pintype "passive"))
      (node (ref "P2") (pin "1") (pinfunction "1_1") (pintype "passive"))
      (node (ref "P2") (pin "10") (pinfunction "10_10") (pintype "passive"))
      (node (ref "P2") (pin "11") (pinfunction "11_11") (pintype "passive"))
      (node (ref "P2") (pin "12") (pinfunction "12_12") (pintype "passive"))
      (node (ref "P2") (pin "13") (pinfunction "13_13") (pintype "passive"))
      (node (ref "P2") (pin "14") (pinfunction "14_14") (pintype "passive"))
      (node (ref "P2") (pin "15") (pinfunction "15_15") (pintype "passive"))
      (node (ref "P2") (pin "16") (pinfunction "16_16") (pintype "passive"))
      (node (ref "P2") (pin "17") (pinfunction "17_17") (pintype "passive"))
      (node (ref "P2") (pin "18") (pinfunction "18_18") (pintype "passive"))
      (node (ref "P2") (pin "19") (pinfunction "19_19") (pintype "passive"))
      (node (ref "P2") (pin "2") (pinfunction "2_2") (pintype "passive"))
      (node (ref "P2") (pin "20") (pinfunction "20_20") (pintype "passive"))
      (node (ref "P2") (pin "21") (pinfunction "21_21") (pintype "passive"))
      (node (ref "P2") (pin "22") (pinfunction "22_22") (pintype "passive"))
      (node (ref "P2") (pin "23") (pinfunction "23_23") (pintype "passive"))
      (node (ref "P2") (pin "24") (pinfunction "24_24") (pintype "passive"))
      (node (ref "P2") (pin "3") (pinfunction "3_3") (pintype "passive"))
      (node (ref "P2") (pin "4") (pinfunction "4_4") (pintype "passive"))
      (node (ref "P2") (pin "5") (pinfunction "5_5") (pintype "passive"))
      (node (ref "P2") (pin "6") (pinfunction "6_6") (pintype "passive"))
      (node (ref "P2") (pin "7") (pinfunction "7_7") (pintype "passive"))
      (node (ref "P2") (pin "8") (pinfunction "8_8") (pintype "passive"))
      (node (ref "P2") (pin "9") (pinfunction "9_9") (pintype "passive"))
      (node (ref "TP2") (pin "1") (pinfunction "1_1") (pintype "passive"))
    )
    (net (code "37") (name "/CELLN_PROT") (class "Default")
      (node (ref "C130") (pin "1") (pinfunction "1_1") (pintype "passive"))
      (node (ref "C131") (pin "2") (pinfunction "2_2") (pintype "passive"))
      (node (ref "C134") (pin "1") (pinfunction "1_1") (pintype "passive"))
      (node (ref "C51") (pin "1") (pinfunction "1_1") (pintype "passive"))
      (node (ref "D124") (pin "1") (pinfunction "A_1") (pintype "passive"))
      (node (ref "D126") (pin "1") (pinfunction "A_1") (pintype "passive"))
      (node (ref "DZ101") (pin "2") (pinfunction "A_2") (pintype "passive"))
      (node (ref "DZ102") (pin "2") (pinfunction "A_2") (pintype "passive"))
      (node (ref "F100") (pin "1") (pinfunction "A_1") (pintype "passive"))
      (node (ref "F101") (pin "1") (pinfunction "A_1") (pintype "passive"))
      (node (ref "Q28") (pin "3") (pinfunction "S_3") (pintype "passive"))
      (node (ref "Q30") (pin "3") (pinfunction "S_3") (pintype "passive"))
      (node (ref "Q32") (pin "3") (pinfunction "S_3") (pintype "passive"))
      (node (ref "R123") (pin "1") (pinfunction "1_1") (pintype "passive"))
      (node (ref "R86") (pin "2") (pinfunction "2_2") (pintype "passive"))
      (node (ref "R88") (pin "1") (pinfunction "1_1") (pintype "passive"))
      (node (ref "U104") (pin "4") (pinfunction "GND_4") (pintype "passive"))
      (node (ref "U104") (pin "8") (pinfunction "GND_8") (pintype "passive"))
    )
    (net (code "39") (name "/CL01") (class "Default")
      (node (ref "Q26") (pin "3") (pinfunction "D_3") (pintype "passive"))
      (node (ref "R82A") (pin "1") (pinfunction "1_1") (pintype "passive"))
      (node (ref "R82B") (pin "1") (pinfunction "1_1") (pintype "passive"))
      (node (ref "R82C") (pin "1") (pinfunction "1_1") (pintype "passive"))
      (node (ref "TP120") (pin "1") (pinfunction "1_1") (pintype "passive"))
    )
    (net (code "40") (name "/CL02") (class "Default")
      (node (ref "Q25") (pin "3") (pinfunction "D_3") (pintype "passive"))
      (node (ref "R78A") (pin "1") (pinfunction "1_1") (pintype "passive"))
      (node (ref "R78B") (pin "1") (pinfunction "1_1") (pintype "passive"))
      (node (ref "R78C") (pin "1") (pinfunction "1_1") (pintype "passive"))
      (node (ref "TP119") (pin "1") (pinfunction "1_1") (pintype "passive"))
    )
    (net (code "41") (name "/CL03") (class "Default")
      (node (ref "Q22") (pin "3") (pinfunction "D_3") (pintype "passive"))
      (node (ref "R74A") (pin "1") (pinfunction "1_1") (pintype "passive"))
      (node (ref "R74B") (pin "1") (pinfunction "1_1") (pintype "passive"))
      (node (ref "R74C") (pin "1") (pinfunction "1_1") (pintype "passive"))
      (node (ref "TP117") (pin "1") (pinfunction "1_1") (pintype "passive"))
    )
    (net (code "42") (name "/CL04") (class "Default")
      (node (ref "Q21") (pin "3") (pinfunction "D_3") (pintype "passive"))
      (node (ref "R72A") (pin "1") (pinfunction "1_1") (pintype "passive"))
      (node (ref "R72B") (pin "1") (pinfunction "1_1") (pintype "passive"))
      (node (ref "R72C") (pin "1") (pinfunction "1_1") (pintype "passive"))
      (node (ref "TP116") (pin "1") (pinfunction "1_1") (pintype "passive"))
    )
    (net (code "43") (name "/CL05") (class "Default")
      (node (ref "Q20") (pin "3") (pinfunction "D_3") (pintype "passive"))
      (node (ref "R66A") (pin "1") (pinfunction "1_1") (pintype "passive"))
      (node (ref "R66B") (pin "1") (pinfunction "1_1") (pintype "passive"))
      (node (ref "R66C") (pin "1") (pinfunction "1_1") (pintype "passive"))
      (node (ref "TP114") (pin "1") (pinfunction "1_1") (pintype "passive"))
    )
    (net (code "44") (name "/CL06") (class "Default")
      (node (ref "Q19") (pin "3") (pinfunction "D_3") (pintype "passive"))
      (node (ref "R62A") (pin "1") (pinfunction "1_1") (pintype "passive"))
      (node (ref "R62B") (pin "1") (pinfunction "1_1") (pintype "passive"))
      (node (ref "R62C") (pin "1") (pinfunction "1_1") (pintype "passive"))
      (node (ref "TP113") (pin "1") (pinfunction "1_1") (pintype "passive"))
    )
    (net (code "45") (name "/CL07") (class "Default")
      (node (ref "Q17") (pin "3") (pinfunction "D_3") (pintype "passive"))
      (node (ref "R54A") (pin "1") (pinfunction "1_1") (pintype "passive"))
      (node (ref "R54B") (pin "1") (pinfunction "1_1") (pintype "passive"))
      (node (ref "R54C") (pin "1") (pinfunction "1_1") (pintype "passive"))
      (node (ref "TP112") (pin "1") (pinfunction "1_1") (pintype "passive"))
    )
    (net (code "46") (name "/CL08") (class "Default")
      (node (ref "Q15") (pin "3") (pinfunction "D_3") (pintype "passive"))
      (node (ref "R44A") (pin "1") (pinfunction "1_1") (pintype "passive"))
      (node (ref "R44B") (pin "1") (pinfunction "1_1") (pintype "passive"))
      (node (ref "R44C") (pin "1") (pinfunction "1_1") (pintype "passive"))
      (node (ref "TP111") (pin "1") (pinfunction "1_1") (pintype "passive"))
    )
    (net (code "47") (name "/CL09") (class "Default")
      (node (ref "Q13") (pin "3") (pinfunction "D_3") (pintype "passive"))
      (node (ref "R37A") (pin "1") (pinfunction "1_1") (pintype "passive"))
      (node (ref "R37B") (pin "1") (pinfunction "1_1") (pintype "passive"))
      (node (ref "R37C") (pin "1") (pinfunction "1_1") (pintype "passive"))
      (node (ref "TP110") (pin "1") (pinfunction "1_1") (pintype "passive"))
    )
    (net (code "48") (name "/CL10") (class "Default")
      (node (ref "Q12") (pin "3") (pinfunction "D_3") (pintype "passive"))
      (node (ref "R35A") (pin "1") (pinfunction "1_1") (pintype "passive"))
      (node (ref "R35B") (pin "1") (pinfunction "1_1") (pintype "passive"))
      (node (ref "R35C") (pin "1") (pinfunction "1_1") (pintype "passive"))
      (node (ref "TP109") (pin "1") (pinfunction "1_1") (pintype "passive"))
    )
    (net (code "49") (name "/CL11") (class "Default")
      (node (ref "Q11") (pin "3") (pinfunction "D_3") (pintype "passive"))
      (node (ref "R32A") (pin "1") (pinfunction "1_1") (pintype "passive"))
      (node (ref "R32B") (pin "1") (pinfunction "1_1") (pintype "passive"))
      (node (ref "R32C") (pin "1") (pinfunction "1_1") (pintype "passive"))
      (node (ref "TP108") (pin "1") (pinfunction "1_1") (pintype "passive"))
    )
    (net (code "50") (name "/CL12") (class "Default")
      (node (ref "Q8") (pin "3") (pinfunction "D_3") (pintype "passive"))
      (node (ref "R27A") (pin "1") (pinfunction "1_1") (pintype "passive"))
      (node (ref "R27B") (pin "1") (pinfunction "1_1") (pintype "passive"))
      (node (ref "R27C") (pin "1") (pinfunction "1_1") (pintype "passive"))
      (node (ref "TP107") (pin "1") (pinfunction "1_1") (pintype "passive"))
    )
    (net (code "51") (name "/CL13") (class "Default")
      (node (ref "Q6") (pin "3") (pinfunction "D_3") (pintype "passive"))
      (node (ref "R17A") (pin "1") (pinfunction "1_1") (pintype "passive"))
      (node (ref "R17B") (pin "1") (pinfunction "1_1") (pintype "passive"))
      (node (ref "R17C") (pin "1") (pinfunction "1_1") (pintype "passive"))
      (node (ref "TP106") (pin "1") (pinfunction "1_1") (pintype "passive"))
    )
    (net (code "52") (name "/CL14") (class "Default")
      (node (ref "Q4") (pin "3") (pinfunction "D_3") (pintype "passive"))
      (node (ref "R10A") (pin "1") (pinfunction "1_1") (pintype "passive"))
      (node (ref "R10B") (pin "1") (pinfunction "1_1") (pintype "passive"))
      (node (ref "R10C") (pin "1") (pinfunction "1_1") (pintype "passive"))
      (node (ref "TP105") (pin "1") (pinfunction "1_1") (pintype "passive"))
    )
    (net (code "53") (name "/CL15") (class "Default")
      (node (ref "Q2") (pin "3") (pinfunction "D_3") (pintype "passive"))
      (node (ref "R5A") (pin "1") (pinfunction "1_1") (pintype "passive"))
      (node (ref "R5B") (pin "1") (pinfunction "1_1") (pintype "passive"))
      (node (ref "R5C") (pin "1") (pinfunction "1_1") (pintype "passive"))
      (node (ref "TP103") (pin "1") (pinfunction "1_1") (pintype "passive"))
    )
    (net (code "54") (name "/CL16") (class "Default")
      (node (ref "Q1") (pin "3") (pinfunction "D_3") (pintype "passive"))
      (node (ref "R3A") (pin "1") (pinfunction "1_1") (pintype "passive"))
      (node (ref "R3B") (pin "1") (pinfunction "1_1") (pintype "passive"))
      (node (ref "R3C") (pin "1") (pinfunction "1_1") (pintype "passive"))
      (node (ref "TP102") (pin "1") (pinfunction "1_1") (pintype "passive"))
    )
    (net (code "55") (name "/COUT") (class "Default")
      (node (ref "R113") (pin "2") (pinfunction "2_2") (pintype "passive"))
      (node (ref "R79") (pin "1") (pinfunction "1_1") (pintype "passive"))
      (node (ref "U7") (pin "3") (pinfunction "Cout_3") (pintype "passive"))
    )
    (net (code "56") (name "/CTL_C_BOT") (class "Default")
      (node (ref "R71") (pin "1") (pinfunction "1_1") (pintype "passive"))
      (node (ref "U7") (pin "1") (pinfunction "CTLC_1") (pintype "passive"))
    )
    (net (code "57") (name "/CTL_C_MID1") (class "Default")
      (node (ref "R43") (pin "1") (pinfunction "1_1") (pintype "passive"))
      (node (ref "U5") (pin "1") (pinfunction "CTLC_1") (pintype "passive"))
    )
    (net (code "58") (name "/CTL_C_MID2") (class "Default")
      (node (ref "R26") (pin "1") (pinfunction "1_1") (pintype "passive"))
      (node (ref "U3") (pin "1") (pinfunction "CTLC_1") (pintype "passive"))
    )
    (net (code "59") (name "/CTL_C_TOP") (class "Default")
      (node (ref "Q3") (pin "2") (pinfunction "S_2") (pintype "passive"))
      (node (ref "R141") (pin "1") (pinfunction "1_1") (pintype "passive"))
      (node (ref "U1") (pin "1") (pinfunction "CTLC_1") (pintype "passive"))
    )
    (net (code "60") (name "/CTL_D_BOT") (class "Default")
      (node (ref "R70") (pin "1") (pinfunction "1_1") (pintype "passive"))
      (node (ref "U7") (pin "2") (pinfunction "CTLD_2") (pintype "passive"))
    )
    (net (code "61") (name "/CTL_D_MID1") (class "Default")
      (node (ref "R42") (pin "1") (pinfunction "1_1") (pintype "passive"))
      (node (ref "U5") (pin "2") (pinfunction "CTLD_2") (pintype "passive"))
    )
    (net (code "62") (name "/CTL_D_MID2") (class "Default")
      (node (ref "R25") (pin "1") (pinfunction "1_1") (pintype "passive"))
      (node (ref "U3") (pin "2") (pinfunction "CTLD_2") (pintype "passive"))
    )
    (net (code "63") (name "/CTL_D_TOP") (class "Default")
      (node (ref "Q5") (pin "2") (pinfunction "S_2") (pintype "passive"))
      (node (ref "R140") (pin "1") (pinfunction "1_1") (pintype "passive"))
      (node (ref "U1") (pin "2") (pinfunction "CTLD_2") (pintype "passive"))
    )
    (net (code "64") (name "/DFET_SRS") (class "Default")
      (node (ref "C132") (pin "2") (pinfunction "2_2") (pintype "passive"))
      (node (ref "C133") (pin "2") (pinfunction "2_2") (pintype "passive"))
      (node (ref "C50") (pin "2") (pinfunction "2_2") (pintype "passive"))
      (node (ref "D123") (pin "1") (pinfunction "A_1") (pintype "passive"))
      (node (ref "D125") (pin "1") (pinfunction "A_1") (pintype "passive"))
      (node (ref "Q27") (pin "3") (pinfunction "S_3") (pintype "passive"))
      (node (ref "Q29") (pin "3") (pinfunction "S_3") (pintype "passive"))
      (node (ref "Q31") (pin "3") (pinfunction "S_3") (pintype "passive"))
      (node (ref "Q33") (pin "2") (pinfunction "S_2") (pintype "passive"))
      (node (ref "R128") (pin "1") (pinfunction "1_1") (pintype "passive"))
      (node (ref "R148") (pin "2") (pinfunction "2_2") (pintype "passive"))
      (node (ref "R149") (pin "2") (pinfunction "2_2") (pintype "passive"))
      (node (ref "R150") (pin "2") (pinfunction "2_2") (pintype "passive"))
      (node (ref "R151") (pin "2") (pinfunction "2_2") (pintype "passive"))
      (node (ref "R57") (pin "1") (pinfunction "1_1") (pintype "passive"))
      (node (ref "R85") (pin "1") (pinfunction "1_1") (pintype "passive"))
      (node (ref "U103") (pin "4") (pinfunction "GND_4") (pintype "passive"))
      (node (ref "U103") (pin "8") (pinfunction "GND_8") (pintype "passive"))
    )
    (net (code "65") (name "/DRAIN") (class "Default")
      (node (ref "R87") (pin "2") (pinfunction "2_2") (pintype "passive"))
      (node (ref "U7") (pin "5") (pinfunction "DRAIN_5") (pintype "passive"))
    )
    (net (code "66") (name "/EN") (class "Default")
      (node (ref "R100") (pin "1") (pinfunction "1_1") (pintype "passive"))
      (node (ref "R102") (pin "2") (pinfunction "2_2") (pintype "passive"))
      (node (ref "U100") (pin "5") (pinfunction "EN_5") (pintype "passive"))
    )
    (net (code "67") (name "/ENABLE") (class "Default")
      (node (ref "U4") (pin "1") (pinfunction "A_1") (pintype "passive"))
    )
    (net (code "68") (name "/ENABLE_RTN") (class "Default")
      (node (ref "U4") (pin "2") (pinfunction "K_2") (pintype "passive"))
    )
    (net (code "69") (name "/GG_VCC") (class "Default")
      (node (ref "C34") (pin "2") (pinfunction "2_2") (pintype "passive"))
      (node (ref "Q18") (pin "2") (pinfunction "S_2") (pintype "passive"))
      (node (ref "U6") (pin "5") (pinfunction "CE_5") (pintype "input"))
      (node (ref "U6") (pin "6") (pinfunction "REGIN_6") (pintype "passive"))
    )
    (net (code "70") (name "/IN6") (class "Default")
      (node (ref "R136") (pin "2") (pinfunction "2_2") (pintype "passive"))
      (node (ref "R137") (pin "1") (pinfunction "1_1") (pintype "passive"))
      (node (ref "U101") (pin "6") (pinfunction "IN6_6") (pintype "passive"))
    )
    (net (code "71") (name "/IN7") (class "Default")
      (node (ref "U101") (pin "5") (pinfunction "IN7_5") (pintype "passive"))
    )
    (net (code "72") (name "/P2V048") (class "Default")
      (node (ref "C104") (pin "2") (pinfunction "2_2") (pintype "passive"))
      (node (ref "R103") (pin "2") (pinfunction "2_2") (pintype "passive"))
      (node (ref "U101") (pin "1") (pinfunction "REF_1") (pintype "passive"))
    )
    (net (code "73") (name "/SCL") (class "Default")
      (node (ref "C124") (pin "2") (pinfunction "2_2") (pintype "passive"))
      (node (ref "DZ5") (pin "2") (pinfunction "S_2") (pintype "passive"))
      (node (ref "R120") (pin "1") (pinfunction "1_1") (pintype "passive"))
      (node (ref "R126") (pin "2") (pinfunction "2_2") (pintype "passive"))
      (node (ref "R55") (pin "1") (pinfunction "1_1") (pintype "passive"))
      (node (ref "U101") (pin "13") (pinfunction "SCL_13") (pintype "passive"))
      (node (ref "U102") (pin "1") (pinfunction "SCL_1") (pintype "passive"))
    )
    (net (code "74") (name "/SCL_EXT") (class "Default")
      (node (ref "R122") (pin "2") (pinfunction "2_2") (pintype "passive"))
      (node (ref "R126") (pin "1") (pinfunction "1_1") (pintype "passive"))
    )
    (net (code "75") (name "/SDA") (class "Default")
      (node (ref "C123") (pin "2") (pinfunction "2_2") (pintype "passive"))
      (node (ref "DZ5") (pin "1") (pinfunction "G_1") (pintype "passive"))
      (node (ref "R108") (pin "2") (pinfunction "2_2") (pintype "passive"))
      (node (ref "R119") (pin "1") (pinfunction "1_1") (pintype "passive"))
      (node (ref "R53") (pin "1") (pinfunction "1_1") (pintype "passive"))
      (node (ref "U101") (pin "14") (pinfunction "SDA_14") (pintype "passive"))
      (node (ref "U102") (pin "3") (pinfunction "SDA_3") (pintype "passive"))
    )
    (net (code "76") (name "/SDA_EXT") (class "Default")
      (node (ref "R108") (pin "1") (pinfunction "1_1") (pintype "passive"))
      (node (ref "R121") (pin "1") (pinfunction "1_1") (pintype "passive"))
    )
    (net (code "77") (name "/SENSE") (class "Default")
      (node (ref "R132") (pin "2") (pinfunction "2_2") (pintype "passive"))
      (node (ref "R85") (pin "2") (pinfunction "2_2") (pintype "passive"))
      (node (ref "U7") (pin "7") (pinfunction "SENS_7") (pintype "passive"))
    )
    (net (code "78") (name "/SW_REG") (class "Default")
      (node (ref "C7") (pin "2") (pinfunction "2_2") (pintype "passive"))
      (node (ref "R100") (pin "2") (pinfunction "2_2") (pintype "passive"))
      (node (ref "R152") (pin "2") (pinfunction "2_2") (pintype "passive"))
      (node (ref "R38") (pin "2") (pinfunction "2_2") (pintype "passive"))
      (node (ref "U2") (pin "3") (pinfunction "VCC_3") (pintype "passive"))
      (node (ref "U4") (pin "4") (pinfunction "E_4") (pintype "passive"))
    )
    (net (code "79") (name "/THERM1") (class "Default")
      (node (ref "C8") (pin "2") (pinfunction "2_2") (pintype "passive"))
      (node (ref "P1") (pin "17") (pinfunction "17_17") (pintype "passive"))
      (node (ref "R12") (pin "1") (pinfunction "1_1") (pintype "passive"))
      (node (ref "U101") (pin "12") (pinfunction "IN0_12") (pintype "passive"))
      (node (ref "U2") (pin "5") (pinfunction "IN1+_5") (pintype "input"))
    )
    (net (code "80") (name "/THERM2") (class "Default")
      (node (ref "C9") (pin "2") (pinfunction "2_2") (pintype "passive"))
      (node (ref "P1") (pin "16") (pinfunction "16_16") (pintype "passive"))
      (node (ref "R13") (pin "1") (pinfunction "1_1") (pintype "passive"))
      (node (ref "U101") (pin "11") (pinfunction "IN1_11") (pintype "passive"))
      (node (ref "U2") (pin "7") (pinfunction "IN2+_7") (pintype "input"))
    )
    (net (code "81") (name "/THERM3") (class "Default")
      (node (ref "C12") (pin "2") (pinfunction "2_2") (pintype "passive"))
      (node (ref "P1") (pin "12") (pinfunction "12_12") (pintype "passive"))
      (node (ref "R14") (pin "1") (pinfunction "1_1") (pintype "passive"))
      (node (ref "U101") (pin "10") (pinfunction "IN2_10") (pintype "passive"))
      (node (ref "U2") (pin "9") (pinfunction "IN3+_9") (pintype "input"))
    )
    (net (code "82") (name "/THERM4") (class "Default")
      (node (ref "C15") (pin "2") (pinfunction "2_2") (pintype "passive"))
      (node (ref "P1") (pin "11") (pinfunction "11_11") (pintype "passive"))
      (node (ref "R15") (pin "1") (pinfunction "1_1") (pintype "passive"))
      (node (ref "U101") (pin "9") (pinfunction "IN3_9") (pintype "passive"))
      (node (ref "U2") (pin "11") (pinfunction "IN4+_11") (pintype "input"))
    )
    (net (code "83") (name "/THERM5") (class "Default")
      (node (ref "C113") (pin "2") (pinfunction "2_2") (pintype "passive"))
      (node (ref "R118") (pin "1") (pinfunction "1_1") (pintype "passive"))
      (node (ref "TR101") (pin "2") (pinfunction "2_2") (pintype "passive"))
      (node (ref "U101") (pin "7") (pinfunction "IN5_7") (pintype "passive"))
    )
    (net (code "84") (name "/THERM6") (class "Default")
      (node (ref "C114") (pin "2") (pinfunction "2_2") (pintype "passive"))
      (node (ref "R117") (pin "1") (pinfunction "1_1") (pintype "passive"))
      (node (ref "TR100") (pin "2") (pinfunction "2_2") (pintype "passive"))
      (node (ref "U101") (pin "8") (pinfunction "IN4_8") (pintype "passive"))
    )
    (net (code "85") (name "/THERM_GG") (class "Default")
      (node (ref "C106") (pin "2") (pinfunction "2_2") (pintype "passive"))
      (node (ref "P1") (pin "13") (pinfunction "13_13") (pintype "passive"))
      (node (ref "U6") (pin "11") (pinfunction "P6/TS_11") (pintype "input"))
    )
    (net (code "86") (name "/THRM_SHTDN_L") (class "Default")
      (node (ref "C4") (pin "2") (pinfunction "2_2") (pintype "passive"))
      (node (ref "DZ100") (pin "2") (pinfunction "A_2") (pintype "passive"))
      (node (ref "Q3") (pin "1") (pinfunction "G_1") (pintype "passive"))
      (node (ref "Q5") (pin "1") (pinfunction "G_1") (pintype "passive"))
      (node (ref "R18") (pin "2") (pinfunction "2_2") (pintype "passive"))
      (node (ref "R6") (pin "1") (pinfunction "1_1") (pintype "passive"))
    )
    (net (code "87") (name "/VDD_BOT") (class "Default")
      (node (ref "C40") (pin "1") (pinfunction "1_1") (pintype "passive"))
      (node (ref "DZ7") (pin "2") (pinfunction "K_2") (pintype "passive"))
      (node (ref "R68") (pin "2") (pinfunction "2_2") (pintype "passive"))
      (node (ref "U7") (pin "13") (pinfunction "SEL2_13") (pintype "passive"))
      (node (ref "U7") (pin "24") (pinfunction "Vdd_24") (pintype "passive"))
    )
    (net (code "88") (name "/VDD_MID1") (class "Default")
      (node (ref "C24") (pin "1") (pinfunction "1_1") (pintype "passive"))
      (node (ref "DZ4") (pin "2") (pinfunction "K_2") (pintype "passive"))
      (node (ref "R40") (pin "2") (pinfunction "2_2") (pintype "passive"))
      (node (ref "U5") (pin "13") (pinfunction "SEL2_13") (pintype "passive"))
      (node (ref "U5") (pin "24") (pinfunction "Vdd_24") (pintype "passive"))
    )
    (net (code "89") (name "/VDD_MID2") (class "Default")
      (node (ref "C13") (pin "1") (pinfunction "1_1") (pintype "passive"))
      (node (ref "DZ2") (pin "2") (pinfunction "K_2") (pintype "passive"))
      (node (ref "R23") (pin "2") (pinfunction "2_2") (pintype "passive"))
      (node (ref "U3") (pin "13") (pinfunction "SEL2_13") (pintype "passive"))
      (node (ref "U3") (pin "24") (pinfunction "Vdd_24") (pintype "passive"))
    )
    (net (code "90") (name "/VDD_TOP") (class "Default")
      (node (ref "C1") (pin "1") (pinfunction "1_1") (pintype "passive"))
      (node (ref "C4") (pin "1") (pinfunction "1_1") (pintype "passive"))
      (node (ref "DZ1") (pin "2") (pinfunction "K_2") (pintype "passive"))
      (node (ref "DZ100") (pin "1") (pinfunction "K_1") (pintype "passive"))
      (node (ref "R1") (pin "2") (pinfunction "2_2") (pintype "passive"))
      (node (ref "R140") (pin "2") (pinfunction "2_2") (pintype "passive"))
      (node (ref "R141") (pin "2") (pinfunction "2_2") (pintype "passive"))
      (node (ref "R6") (pin "2") (pinfunction "2_2") (pintype "passive"))
      (node (ref "U1") (pin "13") (pinfunction "SEL2_13") (pintype "passive"))
      (node (ref "U1") (pin "24") (pinfunction "Vdd_24") (pintype "passive"))
    )
    (net (code "91") (name "/VLT_DIV_EN") (class "Default")
      (node (ref "Q16") (pin "1") (pinfunction "G_1") (pintype "passive"))
      (node (ref "U6") (pin "2") (pinfunction "VEN_2") (pintype "passive"))
    )
    (net (code "92") (name "/VMP") (class "Default")
      (node (ref "DZ9") (pin "1") (pinfunction "K_1") (pintype "passive"))
      (node (ref "R88") (pin "2") (pinfunction "2_2") (pintype "passive"))
      (node (ref "U7") (pin "4") (pinfunction "VMP_4") (pintype "passive"))
    )
    (net (code "93") (name "/VREF_GG") (class "Default")
      (node (ref "C33") (pin "2") (pinfunction "2_2") (pintype "passive"))
      (node (ref "P1") (pin "15") (pinfunction "15_15") (pintype "passive"))
      (node (ref "U6") (pin "7") (pinfunction "REG25_7") (pintype "passive"))
    )
    (net (code "95") (name "CELL1N_SNS") (class "Default")
      (node (ref "C100") (pin "2") (pinfunction "2_2") (pintype "passive"))
      (node (ref "C101") (pin "2") (pinfunction "2_2") (pintype "passive"))
      (node (ref "C102") (pin "2") (pinfunction "2_2") (pintype "passive"))
      (node (ref "C103") (pin "1") (pinfunction "1_1") (pintype "passive"))
      (node (ref "C104") (pin "1") (pinfunction "1_1") (pintype "passive"))
      (node (ref "C105") (pin "1") (pinfunction "1_1") (pintype "passive"))
      (node (ref "C106") (pin "1") (pinfunction "1_1") (pintype "passive"))
      (node (ref "C107") (pin "1") (pinfunction "1_1") (pintype "passive"))
      (node (ref "C108") (pin "1") (pinfunction "1_1") (pintype "passive"))
      (node (ref "C113") (pin "1") (pinfunction "1_1") (pintype "passive"))
      (node (ref "C114") (pin "1") (pinfunction "1_1") (pintype "passive"))
      (node (ref "C12") (pin "1") (pinfunction "1_1") (pintype "passive"))
      (node (ref "C123") (pin "1") (pinfunction "1_1") (pintype "passive"))
      (node (ref "C124") (pin "1") (pinfunction "1_1") (pintype "passive"))
      (node (ref "C128") (pin "1") (pinfunction "1_1") (pintype "passive"))
      (node (ref "C15") (pin "1") (pinfunction "1_1") (pintype "passive"))
      (node (ref "C16") (pin "2") (pinfunction "2_2") (pintype "passive"))
      (node (ref "C18") (pin "1") (pinfunction "1_1") (pintype "passive"))
      (node (ref "C19") (pin "1") (pinfunction "1_1") (pintype "passive"))
      (node (ref "C31") (pin "2") (pinfunction "2_2") (pintype "passive"))
      (node (ref "C32") (pin "1") (pinfunction "1_1") (pintype "passive"))
      (node (ref "C33") (pin "1") (pinfunction "1_1") (pintype "passive"))
      (node (ref "C34") (pin "1") (pinfunction "1_1") (pintype "passive"))
      (node (ref "C36") (pin "1") (pinfunction "1_1") (pintype "passive"))
      (node (ref "C40") (pin "2") (pinfunction "2_2") (pintype "passive"))
      (node (ref "C44") (pin "1") (pinfunction "1_1") (pintype "passive"))
      (node (ref "C45") (pin "2") (pinfunction "2_2") (pintype "passive"))
      (node (ref "C46") (pin "2") (pinfunction "2_2") (pintype "passive"))
      (node (ref "C47") (pin "2") (pinfunction "2_2") (pintype "passive"))
      (node (ref "C48") (pin "1") (pinfunction "1_1") (pintype "passive"))
      (node (ref "C52") (pin "1") (pinfunction "1_1") (pintype "passive"))
      (node (ref "C7") (pin "1") (pinfunction "1_1") (pintype "passive"))
      (node (ref "C8") (pin "1") (pinfunction "1_1") (pintype "passive"))
      (node (ref "C9") (pin "1") (pinfunction "1_1") (pintype "passive"))
      (node (ref "D103") (pin "2") (pinfunction "K_2") (pintype "passive"))
      (node (ref "D116") (pin "2") (pinfunction "A_2") (pintype "passive"))
      (node (ref "DZ3") (pin "2") (pinfunction "A_2") (pintype "passive"))
      (node (ref "DZ5") (pin "3") (pinfunction "D_3") (pintype "passive"))
      (node (ref "DZ6") (pin "2") (pinfunction "A_2") (pintype "passive"))
      (node (ref "DZ7") (pin "1") (pinfunction "A_1") (pintype "passive"))
      (node (ref "DZ9") (pin "2") (pinfunction "A_2") (pintype "passive"))
      (node (ref "P1") (pin "14") (pinfunction "14_14") (pintype "passive"))
      (node (ref "P2") (pin "27") (pinfunction "27_27") (pintype "passive"))
      (node (ref "P2") (pin "28") (pinfunction "28_28") (pintype "passive"))
      (node (ref "P2") (pin "29") (pinfunction "29_29") (pintype "passive"))
      (node (ref "P2") (pin "30") (pinfunction "30_30") (pintype "passive"))
      (node (ref "P2") (pin "31") (pinfunction "31_31") (pintype "passive"))
      (node (ref "P2") (pin "32") (pinfunction "32_32") (pintype "passive"))
      (node (ref "P2") (pin "33") (pinfunction "33_33") (pintype "passive"))
      (node (ref "P2") (pin "34") (pinfunction "34_34") (pintype "passive"))
      (node (ref "P2") (pin "35") (pinfunction "35_35") (pintype "passive"))
      (node (ref "P2") (pin "36") (pinfunction "36_36") (pintype "passive"))
      (node (ref "P2") (pin "37") (pinfunction "37_37") (pintype "passive"))
      (node (ref "P2") (pin "38") (pinfunction "38_38") (pintype "passive"))
      (node (ref "P2") (pin "39") (pinfunction "39_39") (pintype "passive"))
      (node (ref "P2") (pin "40") (pinfunction "40_40") (pintype "passive"))
      (node (ref "P2") (pin "41") (pinfunction "41_41") (pintype "passive"))
      (node (ref "P2") (pin "42") (pinfunction "42_42") (pintype "passive"))
      (node (ref "P2") (pin "43") (pinfunction "43_43") (pintype "passive"))
      (node (ref "P2") (pin "44") (pinfunction "44_44") (pintype "passive"))
      (node (ref "P2") (pin "45") (pinfunction "45_45") (pintype "passive"))
      (node (ref "P2") (pin "46") (pinfunction "46_46") (pintype "passive"))
      (node (ref "P2") (pin "47") (pinfunction "47_47") (pintype "passive"))
      (node (ref "P2") (pin "48") (pinfunction "48_48") (pintype "passive"))
      (node (ref "P2") (pin "49") (pinfunction "49_49") (pintype "passive"))
      (node (ref "P2") (pin "50") (pinfunction "50_50") (pintype "passive"))
      (node (ref "Q10") (pin "2") (pinfunction "S_2") (pintype "passive"))
      (node (ref "Q100") (pin "2") (pinfunction "S_2") (pintype "passive"))
      (node (ref "Q101") (pin "2") (pinfunction "S_2") (pintype "passive"))
      (node (ref "Q102") (pin "2") (pinfunction "S_2") (pintype "passive"))
      (node (ref "Q103") (pin "2") (pinfunction "S_2") (pintype "passive"))
      (node (ref "Q16") (pin "2") (pinfunction "S_2") (pintype "passive"))
      (node (ref "Q24") (pin "2") (pinfunction "S_2") (pintype "passive"))
      (node (ref "Q26") (pin "2") (pinfunction "S_2") (pintype "passive"))
      (node (ref "Q7") (pin "2") (pinfunction "S_2") (pintype "passive"))
      (node (ref "R102") (pin "1") (pinfunction "1_1") (pintype "passive"))
      (node (ref "R104") (pin "1") (pinfunction "1_1") (pintype "passive"))
      (node (ref "R105") (pin "2") (pinfunction "2_2") (pintype "passive"))
      (node (ref "R111") (pin "2") (pinfunction "2_2") (pintype "passive"))
      (node (ref "R132") (pin "1") (pinfunction "1_1") (pintype "passive"))
      (node (ref "R136") (pin "1") (pinfunction "1_1") (pintype "passive"))
      (node (ref "R138") (pin "1") (pinfunction "1_1") (pintype "passive"))
      (node (ref "R148") (pin "1") (pinfunction "1_1") (pintype "passive"))
      (node (ref "R149") (pin "1") (pinfunction "1_1") (pintype "passive"))
      (node (ref "R150") (pin "1") (pinfunction "1_1") (pintype "passive"))
      (node (ref "R151") (pin "1") (pinfunction "1_1") (pintype "passive"))
      (node (ref "R22") (pin "1") (pinfunction "1_1") (pintype "passive"))
      (node (ref "R29") (pin "1") (pinfunction "1_1") (pintype "passive"))
      (node (ref "R53") (pin "2") (pinfunction "2_2") (pintype "passive"))
      (node (ref "R55") (pin "2") (pinfunction "2_2") (pintype "passive"))
      (node (ref "R56") (pin "1") (pinfunction "1_1") (pintype "passive"))
      (node (ref "R58") (pin "1") (pinfunction "1_1") (pintype "passive"))
      (node (ref "R61") (pin "1") (pinfunction "1_1") (pintype "passive"))
      (node (ref "R80") (pin "2") (pinfunction "2_2") (pintype "passive"))
      (node (ref "R83") (pin "1") (pinfunction "1_1") (pintype "passive"))
      (node (ref "R83") (pin "2") (pinfunction "2_2") (pintype "passive"))
      (node (ref "R92") (pin "1") (pinfunction "1_1") (pintype "passive"))
      (node (ref "TP1") (pin "1") (pinfunction "1_1") (pintype "passive"))
      (node (ref "TP100") (pin "1") (pinfunction "1_1") (pintype "passive"))
      (node (ref "TR100") (pin "1") (pinfunction "1_1") (pintype "passive"))
      (node (ref "TR101") (pin "1") (pinfunction "1_1") (pintype "passive"))
      (node (ref "U100") (pin "1") (pinfunction "GND_1") (pintype "passive"))
      (node (ref "U101") (pin "15") (pinfunction "GND_15") (pintype "passive"))
      (node (ref "U102") (pin "2") (pinfunction "GND_2") (pintype "passive"))
      (node (ref "U2") (pin "12") (pinfunction "GND_12") (pintype "passive"))
      (node (ref "U6") (pin "1") (pinfunction "P2_1") (pintype "passive"))
      (node (ref "U6") (pin "3") (pinfunction "P1_3") (pintype "passive"))
      (node (ref "U6") (pin "8") (pinfunction "VSS_8") (pintype "passive"))
      (node (ref "U7") (pin "12") (pinfunction "SEL1_12") (pintype "passive"))
      (node (ref "U7") (pin "15") (pinfunction "VC5_15") (pintype "passive"))
      (node (ref "U7") (pin "9") (pinfunction "Vss_9") (pintype "passive"))
    )
    (net (code "96") (name "CELL16P") (class "Default")
      (node (ref "C27") (pin "2") (pinfunction "2_2") (pintype "passive"))
      (node (ref "P1") (pin "1") (pinfunction "1_1") (pintype "passive"))
      (node (ref "Q14") (pin "2") (pinfunction "S_2") (pintype "passive"))
      (node (ref "R1") (pin "1") (pinfunction "1_1") (pintype "passive"))
      (node (ref "R107") (pin "2") (pinfunction "2_2") (pintype "passive"))
      (node (ref "R115") (pin "2") (pinfunction "2_2") (pintype "passive"))
      (node (ref "R2") (pin "1") (pinfunction "1_1") (pintype "passive"))
      (node (ref "R3A") (pin "2") (pinfunction "2_2") (pintype "passive"))
      (node (ref "R3B") (pin "2") (pinfunction "2_2") (pintype "passive"))
      (node (ref "R3C") (pin "2") (pinfunction "2_2") (pintype "passive"))
      (node (ref "R45") (pin "2") (pinfunction "2_2") (pintype "passive"))
      (node (ref "R60") (pin "2") (pinfunction "2_2") (pintype "passive"))
    )
    (net (code "97") (name "Net-(C19-Pad2)") (class "Default")
      (node (ref "C19") (pin "2") (pinfunction "2_2") (pintype "passive"))
      (node (ref "R33") (pin "1") (pinfunction "1_1") (pintype "passive"))
    )
    (net (code "98") (name "Net-(C27-Pad1)") (class "Default")
      (node (ref "C27") (pin "1") (pinfunction "1_1") (pintype "passive"))
      (node (ref "C30") (pin "2") (pinfunction "2_2") (pintype "passive"))
    )
    (net (code "99") (name "Net-(C36-Pad2)") (class "Default")
      (node (ref "C36") (pin "2") (pinfunction "2_2") (pintype "passive"))
      (node (ref "R64") (pin "1") (pinfunction "1_1") (pintype "passive"))
    )
    (net (code "100") (name "Net-(C50-Pad1)") (class "Default")
      (node (ref "C50") (pin "1") (pinfunction "1_1") (pintype "passive"))
      (node (ref "C51") (pin "2") (pinfunction "2_2") (pintype "passive"))
    )
    (net (code "101") (name "Net-(C108-Pad2)") (class "Default")
      (node (ref "C108") (pin "2") (pinfunction "2_2") (pintype "passive"))
      (node (ref "R116") (pin "1") (pinfunction "1_1") (pintype "passive"))
    )
    (net (code "102") (name "Net-(C129-Pad1)") (class "Default")
      (node (ref "C129") (pin "1") (pinfunction "1_1") (pintype "passive"))
      (node (ref "C130") (pin "2") (pinfunction "2_2") (pintype "passive"))
    )
    (net (code "103") (name "Net-(C129-Pad2)") (class "Default")
      (node (ref "C129") (pin "2") (pinfunction "2_2") (pintype "passive"))
      (node (ref "R128") (pin "2") (pinfunction "2_2") (pintype "passive"))
    )
    (net (code "104") (name "Net-(C132-Pad1)") (class "Default")
      (node (ref "C132") (pin "1") (pinfunction "1_1") (pintype "passive"))
      (node (ref "C133") (pin "1") (pinfunction "1_1") (pintype "passive"))
      (node (ref "R124") (pin "1") (pinfunction "1_1") (pintype "passive"))
      (node (ref "R125") (pin "2") (pinfunction "2_2") (pintype "passive"))
      (node (ref "U103") (pin "1") (pinfunction "VCC_1") (pintype "passive"))
      (node (ref "U103") (pin "5") (pinfunction "VCC_5") (pintype "passive"))
    )
    (net (code "105") (name "Net-(D1-A)") (class "Default")
      (node (ref "D1") (pin "1") (pinfunction "A_1") (pintype "passive"))
      (node (ref "Q23") (pin "3") (pinfunction "D_3") (pintype "passive"))
    )
    (net (code "106") (name "Net-(D1-K)") (class "Default")
      (node (ref "D1") (pin "3") (pinfunction "K_3") (pintype "passive"))
      (node (ref "R84") (pin "2") (pinfunction "2_2") (pintype "passive"))
    )
    (net (code "107") (name "Net-(D100-A)") (class "Default")
      (node (ref "C2") (pin "1") (pinfunction "1_1") (pintype "passive"))
      (node (ref "C3") (pin "2") (pinfunction "2_2") (pintype "passive"))
      (node (ref "D100") (pin "2") (pinfunction "A_2") (pintype "passive"))
      (node (ref "D101") (pin "1") (pinfunction "K_1") (pintype "passive"))
      (node (ref "R4") (pin "2") (pinfunction "2_2") (pintype "passive"))
      (node (ref "U1") (pin "21") (pinfunction "VC2_21") (pintype "passive"))
    )
    (net (code "108") (name "Net-(D100-K)") (class "Default")
      (node (ref "C2") (pin "2") (pinfunction "2_2") (pintype "passive"))
      (node (ref "D100") (pin "1") (pinfunction "K_1") (pintype "passive"))
      (node (ref "R2") (pin "2") (pinfunction "2_2") (pintype "passive"))
      (node (ref "U1") (pin "23") (pinfunction "VC1_23") (pintype "passive"))
    )
    (net (code "109") (name "Net-(D101-A)") (class "Default")
      (node (ref "C3") (pin "1") (pinfunction "1_1") (pintype "passive"))
      (node (ref "C5") (pin "2") (pinfunction "2_2") (pintype "passive"))
      (node (ref "D101") (pin "2") (pinfunction "A_2") (pintype "passive"))
      (node (ref "D102") (pin "1") (pinfunction "K_1") (pintype "passive"))
      (node (ref "R9") (pin "2") (pinfunction "2_2") (pintype "passive"))
      (node (ref "U1") (pin "19") (pinfunction "VC3_19") (pintype "passive"))
    )
    (net (code "110") (name "Net-(D102-A)") (class "Default")
      (node (ref "C5") (pin "1") (pinfunction "1_1") (pintype "passive"))
      (node (ref "C6") (pin "2") (pinfunction "2_2") (pintype "passive"))
      (node (ref "D102") (pin "2") (pinfunction "A_2") (pintype "passive"))
      (node (ref "D104") (pin "1") (pinfunction "K_1") (pintype "passive"))
      (node (ref "R16") (pin "2") (pinfunction "2_2") (pintype "passive"))
      (node (ref "U1") (pin "17") (pinfunction "VC4_17") (pintype "passive"))
    )
    (net (code "111") (name "Net-(D103-A)") (class "Default")
      (node (ref "D103") (pin "1") (pinfunction "A_1") (pintype "passive"))
      (node (ref "R101") (pin "2") (pinfunction "2_2") (pintype "passive"))
    )
    (net (code "112") (name "Net-(D104-A)") (class "Default")
      (node (ref "C1") (pin "2") (pinfunction "2_2") (pintype "passive"))
      (node (ref "C10") (pin "2") (pinfunction "2_2") (pintype "passive"))
      (node (ref "C11") (pin "2") (pinfunction "2_2") (pintype "passive"))
      (node (ref "C112") (pin "2") (pinfunction "2_2") (pintype "passive"))
      (node (ref "C6") (pin "1") (pinfunction "1_1") (pintype "passive"))
      (node (ref "D104") (pin "2") (pinfunction "A_2") (pintype "passive"))
      (node (ref "DZ1") (pin "1") (pinfunction "A_1") (pintype "passive"))
      (node (ref "Q3") (pin "3") (pinfunction "D_3") (pintype "passive"))
      (node (ref "Q5") (pin "3") (pinfunction "D_3") (pintype "passive"))
      (node (ref "Q6") (pin "2") (pinfunction "S_2") (pintype "passive"))
      (node (ref "R142") (pin "2") (pinfunction "2_2") (pintype "passive"))
      (node (ref "R23") (pin "1") (pinfunction "1_1") (pintype "passive"))
      (node (ref "R24") (pin "1") (pinfunction "1_1") (pintype "passive"))
      (node (ref "R27A") (pin "2") (pinfunction "2_2") (pintype "passive"))
      (node (ref "R27B") (pin "2") (pinfunction "2_2") (pintype "passive"))
      (node (ref "R27C") (pin "2") (pinfunction "2_2") (pintype "passive"))
      (node (ref "U1") (pin "11") (pinfunction "CT2_11") (pintype "passive"))
      (node (ref "U1") (pin "12") (pinfunction "SEL1_12") (pintype "passive"))
      (node (ref "U1") (pin "15") (pinfunction "VC5_15") (pintype "passive"))
      (node (ref "U1") (pin "4") (pinfunction "VMP_4") (pintype "passive"))
      (node (ref "U1") (pin "7") (pinfunction "SENS_7") (pintype "passive"))
      (node (ref "U1") (pin "9") (pinfunction "Vss_9") (pintype "passive"))
    )
    (net (code "113") (name "Net-(D105-A)") (class "Default")
      (node (ref "C14") (pin "1") (pinfunction "1_1") (pintype "passive"))
      (node (ref "C17") (pin "2") (pinfunction "2_2") (pintype "passive"))
      (node (ref "D105") (pin "2") (pinfunction "A_2") (pintype "passive"))
      (node (ref "D106") (pin "1") (pinfunction "K_1") (pintype "passive"))
      (node (ref "R30") (pin "2") (pinfunction "2_2") (pintype "passive"))
      (node (ref "U3") (pin "21") (pinfunction "VC2_21") (pintype "passive"))
    )
    (net (code "114") (name "Net-(D105-K)") (class "Default")
      (node (ref "C14") (pin "2") (pinfunction "2_2") (pintype "passive"))
      (node (ref "D105") (pin "1") (pinfunction "K_1") (pintype "passive"))
      (node (ref "R24") (pin "2") (pinfunction "2_2") (pintype "passive"))
      (node (ref "U3") (pin "23") (pinfunction "VC1_23") (pintype "passive"))
    )
    (net (code "115") (name "Net-(D106-A)") (class "Default")
      (node (ref "C17") (pin "1") (pinfunction "1_1") (pintype "passive"))
      (node (ref "C20") (pin "2") (pinfunction "2_2") (pintype "passive"))
      (node (ref "D106") (pin "2") (pinfunction "A_2") (pintype "passive"))
      (node (ref "D107") (pin "1") (pinfunction "K_1") (pintype "passive"))
      (node (ref "R34") (pin "2") (pinfunction "2_2") (pintype "passive"))
      (node (ref "U3") (pin "19") (pinfunction "VC3_19") (pintype "passive"))
    )
    (net (code "116") (name "Net-(D107-A)") (class "Default")
      (node (ref "C20") (pin "1") (pinfunction "1_1") (pintype "passive"))
      (node (ref "C21") (pin "2") (pinfunction "2_2") (pintype "passive"))
      (node (ref "D107") (pin "2") (pinfunction "A_2") (pintype "passive"))
      (node (ref "D108") (pin "1") (pinfunction "K_1") (pintype "passive"))
      (node (ref "R36") (pin "2") (pinfunction "2_2") (pintype "passive"))
      (node (ref "U3") (pin "17") (pinfunction "VC4_17") (pintype "passive"))
    )
    (net (code "117") (name "Net-(D109-A)") (class "Default")
      (node (ref "C25") (pin "1") (pinfunction "1_1") (pintype "passive"))
      (node (ref "C26") (pin "2") (pinfunction "2_2") (pintype "passive"))
      (node (ref "D109") (pin "2") (pinfunction "A_2") (pintype "passive"))
      (node (ref "D110") (pin "1") (pinfunction "K_1") (pintype "passive"))
      (node (ref "R51") (pin "2") (pinfunction "2_2") (pintype "passive"))
      (node (ref "U5") (pin "21") (pinfunction "VC2_21") (pintype "passive"))
    )
    (net (code "118") (name "Net-(D109-K)") (class "Default")
      (node (ref "C25") (pin "2") (pinfunction "2_2") (pintype "passive"))
      (node (ref "D109") (pin "1") (pinfunction "K_1") (pintype "passive"))
      (node (ref "R41") (pin "2") (pinfunction "2_2") (pintype "passive"))
      (node (ref "U5") (pin "23") (pinfunction "VC1_23") (pintype "passive"))
    )
    (net (code "119") (name "Net-(D110-A)") (class "Default")
      (node (ref "C26") (pin "1") (pinfunction "1_1") (pintype "passive"))
      (node (ref "C29") (pin "2") (pinfunction "2_2") (pintype "passive"))
      (node (ref "D110") (pin "2") (pinfunction "A_2") (pintype "passive"))
      (node (ref "D111") (pin "1") (pinfunction "K_1") (pintype "passive"))
      (node (ref "R59") (pin "2") (pinfunction "2_2") (pintype "passive"))
      (node (ref "U5") (pin "19") (pinfunction "VC3_19") (pintype "passive"))
    )
    (net (code "120") (name "Net-(D111-A)") (class "Default")
      (node (ref "C29") (pin "1") (pinfunction "1_1") (pintype "passive"))
      (node (ref "C37") (pin "2") (pinfunction "2_2") (pintype "passive"))
      (node (ref "D111") (pin "2") (pinfunction "A_2") (pintype "passive"))
      (node (ref "D112") (pin "1") (pinfunction "K_1") (pintype "passive"))
      (node (ref "R65") (pin "2") (pinfunction "2_2") (pintype "passive"))
      (node (ref "U5") (pin "17") (pinfunction "VC4_17") (pintype "passive"))
    )
    (net (code "121") (name "Net-(D113-A)") (class "Default")
      (node (ref "C41") (pin "1") (pinfunction "1_1") (pintype "passive"))
      (node (ref "C42") (pin "2") (pinfunction "2_2") (pintype "passive"))
      (node (ref "D113") (pin "2") (pinfunction "A_2") (pintype "passive"))
      (node (ref "D114") (pin "1") (pinfunction "K_1") (pintype "passive"))
      (node (ref "R73") (pin "2") (pinfunction "2_2") (pintype "passive"))
      (node (ref "U7") (pin "21") (pinfunction "VC2_21") (pintype "passive"))
    )
    (net (code "122") (name "Net-(D113-K)") (class "Default")
      (node (ref "C41") (pin "2") (pinfunction "2_2") (pintype "passive"))
      (node (ref "D113") (pin "1") (pinfunction "K_1") (pintype "passive"))
      (node (ref "R69") (pin "2") (pinfunction "2_2") (pintype "passive"))
      (node (ref "U7") (pin "23") (pinfunction "VC1_23") (pintype "passive"))
    )
    (net (code "123") (name "Net-(D114-A)") (class "Default")
      (node (ref "C42") (pin "1") (pinfunction "1_1") (pintype "passive"))
      (node (ref "C43") (pin "2") (pinfunction "2_2") (pintype "passive"))
      (node (ref "D114") (pin "2") (pinfunction "A_2") (pintype "passive"))
      (node (ref "D115") (pin "1") (pinfunction "K_1") (pintype "passive"))
      (node (ref "R76") (pin "2") (pinfunction "2_2") (pintype "passive"))
      (node (ref "U7") (pin "19") (pinfunction "VC3_19") (pintype "passive"))
    )
    (net (code "124") (name "Net-(D115-A)") (class "Default")
      (node (ref "C43") (pin "1") (pinfunction "1_1") (pintype "passive"))
      (node (ref "C44") (pin "2") (pinfunction "2_2") (pintype "passive"))
      (node (ref "D115") (pin "2") (pinfunction "A_2") (pintype "passive"))
      (node (ref "D116") (pin "1") (pinfunction "K_1") (pintype "passive"))
      (node (ref "R81") (pin "2") (pinfunction "2_2") (pintype "passive"))
      (node (ref "U7") (pin "17") (pinfunction "VC4_17") (pintype "passive"))
    )
    (net (code "125") (name "Net-(D117-A)") (class "Default")
      (node (ref "D117") (pin "1") (pinfunction "A_1") (pintype "passive"))
      (node (ref "R109") (pin "1") (pinfunction "1_1") (pintype "passive"))
    )
    (net (code "126") (name "Net-(D117-K)") (class "Default")
      (node (ref "D117") (pin "2") (pinfunction "K_2") (pintype "passive"))
      (node (ref "Q101") (pin "3") (pinfunction "D_3") (pintype "passive"))
    )
    (net (code "127") (name "Net-(D118-A)") (class "Default")
      (node (ref "D118") (pin "1") (pinfunction "A_1") (pintype "passive"))
      (node (ref "R114") (pin "1") (pinfunction "1_1") (pintype "passive"))
    )
    (net (code "128") (name "Net-(D118-K)") (class "Default")
      (node (ref "D118") (pin "2") (pinfunction "K_2") (pintype "passive"))
      (node (ref "Q100") (pin "3") (pinfunction "D_3") (pintype "passive"))
    )
    (net (code "129") (name "Net-(D121-K)") (class "Default")
      (node (ref "D121") (pin "3") (pinfunction "K_3") (pintype "passive"))
      (node (ref "R127") (pin "2") (pinfunction "2_2") (pintype "passive"))
    )
    (net (code "130") (name "Net-(D123-K)") (class "Default")
      (node (ref "D123") (pin "2") (pinfunction "K_2") (pintype "passive"))
      (node (ref "D124") (pin "2") (pinfunction "K_2") (pintype "passive"))
      (node (ref "Q27") (pin "T") (pinfunction "D_T") (pintype "passive"))
      (node (ref "Q28") (pin "T") (pinfunction "D_T") (pintype "passive"))
      (node (ref "Q29") (pin "T") (pinfunction "D_T") (pintype "passive"))
      (node (ref "Q30") (pin "T") (pinfunction "D_T") (pintype "passive"))
      (node (ref "Q31") (pin "T") (pinfunction "D_T") (pintype "passive"))
      (node (ref "Q32") (pin "T") (pinfunction "D_T") (pintype "passive"))
      (node (ref "R145") (pin "1") (pinfunction "1_1") (pintype "passive"))
      (node (ref "R146") (pin "2") (pinfunction "2_2") (pintype "passive"))
      (node (ref "R147") (pin "1") (pinfunction "1_1") (pintype "passive"))
    )
    (net (code "131") (name "Net-(D125-K)") (class "Default")
      (node (ref "D125") (pin "2") (pinfunction "K_2") (pintype "passive"))
      (node (ref "Q27") (pin "1") (pinfunction "G_1") (pintype "passive"))
      (node (ref "Q29") (pin "1") (pinfunction "G_1") (pintype "passive"))
      (node (ref "Q31") (pin "1") (pinfunction "G_1") (pintype "passive"))
      (node (ref "R130") (pin "1") (pinfunction "1_1") (pintype "passive"))
      (node (ref "U103") (pin "6") (pinfunction "OUT_6") (pintype "passive"))
      (node (ref "U103") (pin "7") (pinfunction "OUT_7") (pintype "passive"))
    )
    (net (code "132") (name "Net-(D126-K)") (class "Default")
      (node (ref "D126") (pin "2") (pinfunction "K_2") (pintype "passive"))
      (node (ref "Q28") (pin "1") (pinfunction "G_1") (pintype "passive"))
      (node (ref "Q30") (pin "1") (pinfunction "G_1") (pintype "passive"))
      (node (ref "Q32") (pin "1") (pinfunction "G_1") (pintype "passive"))
      (node (ref "R131") (pin "1") (pinfunction "1_1") (pintype "passive"))
      (node (ref "R133") (pin "1") (pinfunction "1_1") (pintype "passive"))
      (node (ref "R134") (pin "1") (pinfunction "1_1") (pintype "passive"))
      (node (ref "R86") (pin "1") (pinfunction "1_1") (pintype "passive"))
    )
    (net (code "133") (name "Net-(DZ3-K)") (class "Default")
      (node (ref "DZ3") (pin "1") (pinfunction "K_1") (pintype "passive"))
      (node (ref "Q9") (pin "1") (pinfunction "G_1") (pintype "passive"))
      (node (ref "R31") (pin "1") (pinfunction "1_1") (pintype "passive"))
      (node (ref "R33") (pin "2") (pinfunction "2_2") (pintype "passive"))
    )
    (net (code "134") (name "Net-(DZ6-K)") (class "Default")
      (node (ref "DZ6") (pin "1") (pinfunction "K_1") (pintype "passive"))
      (node (ref "Q18") (pin "1") (pinfunction "G_1") (pintype "passive"))
      (node (ref "R63") (pin "1") (pinfunction "1_1") (pintype "passive"))
      (node (ref "R64") (pin "2") (pinfunction "2_2") (pintype "passive"))
    )
    (net (code "135") (name "Net-(DZ101-K)") (class "Default")
      (node (ref "DZ101") (pin "1") (pinfunction "K_1") (pintype "passive"))
      (node (ref "R123") (pin "2") (pinfunction "2_2") (pintype "passive"))
      (node (ref "R133") (pin "2") (pinfunction "2_2") (pintype "passive"))
      (node (ref "R84") (pin "1") (pinfunction "1_1") (pintype "passive"))
      (node (ref "U104") (pin "2") (pinfunction "IN_2") (pintype "passive"))
    )
    (net (code "136") (name "Net-(DZ102-K)") (class "Default")
      (node (ref "C131") (pin "1") (pinfunction "1_1") (pintype "passive"))
      (node (ref "C134") (pin "2") (pinfunction "2_2") (pintype "passive"))
      (node (ref "DZ102") (pin "1") (pinfunction "K_1") (pintype "passive"))
      (node (ref "R127") (pin "1") (pinfunction "1_1") (pintype "passive"))
      (node (ref "R129") (pin "2") (pinfunction "2_2") (pintype "passive"))
      (node (ref "U104") (pin "1") (pinfunction "VCC_1") (pintype "passive"))
      (node (ref "U104") (pin "5") (pinfunction "VCC_5") (pintype "passive"))
    )
    (net (code "137") (name "Net-(Q7-D)") (class "Default")
      (node (ref "Q7") (pin "3") (pinfunction "D_3") (pintype "passive"))
      (node (ref "R19") (pin "1") (pinfunction "1_1") (pintype "passive"))
    )
    (net (code "138") (name "Net-(Q8-S)") (class "Default")
      (node (ref "C115") (pin "2") (pinfunction "2_2") (pintype "passive"))
      (node (ref "Q8") (pin "2") (pinfunction "S_2") (pintype "passive"))
      (node (ref "R30") (pin "1") (pinfunction "1_1") (pintype "passive"))
      (node (ref "R32A") (pin "2") (pinfunction "2_2") (pintype "passive"))
      (node (ref "R32B") (pin "2") (pinfunction "2_2") (pintype "passive"))
      (node (ref "R32C") (pin "2") (pinfunction "2_2") (pintype "passive"))
    )
    (net (code "139") (name "Net-(Q9-D)") (class "Default")
      (node (ref "Q9") (pin "4") (pinfunction "D_4") (pintype "passive"))
      (node (ref "R115") (pin "1") (pinfunction "1_1") (pintype "passive"))
      (node (ref "R116") (pin "2") (pinfunction "2_2") (pintype "passive"))
      (node (ref "R31") (pin "2") (pinfunction "2_2") (pintype "passive"))
    )
    (net (code "140") (name "Net-(Q9-S)") (class "Default")
      (node (ref "C101") (pin "1") (pinfunction "1_1") (pintype "passive"))
      (node (ref "C18") (pin "2") (pinfunction "2_2") (pintype "passive"))
      (node (ref "Q9") (pin "3") (pinfunction "S_3") (pintype "passive"))
      (node (ref "TP101") (pin "1") (pinfunction "1_1") (pintype "passive"))
      (node (ref "U100") (pin "2") (pinfunction "IN_2") (pintype "passive"))
      (node (ref "U4") (pin "5") (pinfunction "C_5") (pintype "passive"))
    )
    (net (code "141") (name "Net-(Q10-D)") (class "Default")
      (node (ref "Q10") (pin "3") (pinfunction "D_3") (pintype "passive"))
      (node (ref "R28") (pin "1") (pinfunction "1_1") (pintype "passive"))
    )
    (net (code "142") (name "Net-(Q10-G)") (class "Default")
      (node (ref "C52") (pin "2") (pinfunction "2_2") (pintype "passive"))
      (node (ref "Q10") (pin "1") (pinfunction "G_1") (pintype "passive"))
      (node (ref "Q7") (pin "1") (pinfunction "G_1") (pintype "passive"))
      (node (ref "R152") (pin "1") (pinfunction "1_1") (pintype "passive"))
      (node (ref "R22") (pin "2") (pinfunction "2_2") (pintype "passive"))
      (node (ref "U2") (pin "1") (pinfunction "OUT2_1") (pintype "passive"))
      (node (ref "U2") (pin "13") (pinfunction "OUT4_13") (pintype "passive"))
      (node (ref "U2") (pin "14") (pinfunction "OUT3_14") (pintype "passive"))
      (node (ref "U2") (pin "2") (pinfunction "OUT1_2") (pintype "passive"))
    )
    (net (code "143") (name "Net-(Q11-S)") (class "Default")
      (node (ref "C116") (pin "2") (pinfunction "2_2") (pintype "passive"))
      (node (ref "Q11") (pin "2") (pinfunction "S_2") (pintype "passive"))
      (node (ref "R34") (pin "1") (pinfunction "1_1") (pintype "passive"))
      (node (ref "R35A") (pin "2") (pinfunction "2_2") (pintype "passive"))
      (node (ref "R35B") (pin "2") (pinfunction "2_2") (pintype "passive"))
      (node (ref "R35C") (pin "2") (pinfunction "2_2") (pintype "passive"))
    )
    (net (code "144") (name "Net-(Q12-S)") (class "Default")
      (node (ref "C117") (pin "2") (pinfunction "2_2") (pintype "passive"))
      (node (ref "Q12") (pin "2") (pinfunction "S_2") (pintype "passive"))
      (node (ref "R36") (pin "1") (pinfunction "1_1") (pintype "passive"))
      (node (ref "R37A") (pin "2") (pinfunction "2_2") (pintype "passive"))
      (node (ref "R37B") (pin "2") (pinfunction "2_2") (pintype "passive"))
      (node (ref "R37C") (pin "2") (pinfunction "2_2") (pintype "passive"))
    )
    (net (code "145") (name "Net-(Q14-D)") (class "Default")
      (node (ref "Q14") (pin "3") (pinfunction "D_3") (pintype "passive"))
      (node (ref "R107") (pin "1") (pinfunction "1_1") (pintype "passive"))
      (node (ref "R52") (pin "2") (pinfunction "2_2") (pintype "passive"))
    )
    (net (code "146") (name "Net-(Q14-G)") (class "Default")
      (node (ref "Q14") (pin "1") (pinfunction "G_1") (pintype "passive"))
      (node (ref "R45") (pin "1") (pinfunction "1_1") (pintype "passive"))
      (node (ref "R50") (pin "2") (pinfunction "2_2") (pintype "passive"))
    )
    (net (code "147") (name "Net-(Q15-S)") (class "Default")
      (node (ref "C119") (pin "1") (pinfunction "1_1") (pintype "passive"))
      (node (ref "Q15") (pin "2") (pinfunction "S_2") (pintype "passive"))
      (node (ref "R51") (pin "1") (pinfunction "1_1") (pintype "passive"))
      (node (ref "R54A") (pin "2") (pinfunction "2_2") (pintype "passive"))
      (node (ref "R54B") (pin "2") (pinfunction "2_2") (pintype "passive"))
      (node (ref "R54C") (pin "2") (pinfunction "2_2") (pintype "passive"))
    )
    (net (code "148") (name "Net-(Q16-D)") (class "Default")
      (node (ref "Q16") (pin "3") (pinfunction "D_3") (pintype "passive"))
      (node (ref "R50") (pin "1") (pinfunction "1_1") (pintype "passive"))
    )
    (net (code "149") (name "Net-(Q17-S)") (class "Default")
      (node (ref "C120") (pin "1") (pinfunction "1_1") (pintype "passive"))
      (node (ref "Q17") (pin "2") (pinfunction "S_2") (pintype "passive"))
      (node (ref "R59") (pin "1") (pinfunction "1_1") (pintype "passive"))
      (node (ref "R62A") (pin "2") (pinfunction "2_2") (pintype "passive"))
      (node (ref "R62B") (pin "2") (pinfunction "2_2") (pintype "passive"))
      (node (ref "R62C") (pin "2") (pinfunction "2_2") (pintype "passive"))
    )
    (net (code "150") (name "Net-(Q18-D)") (class "Default")
      (node (ref "Q18") (pin "3") (pinfunction "D_3") (pintype "passive"))
      (node (ref "R60") (pin "1") (pinfunction "1_1") (pintype "passive"))
      (node (ref "R63") (pin "2") (pinfunction "2_2") (pintype "passive"))
    )
    (net (code "151") (name "Net-(Q19-S)") (class "Default")
      (node (ref "C121") (pin "1") (pinfunction "1_1") (pintype "passive"))
      (node (ref "Q19") (pin "2") (pinfunction "S_2") (pintype "passive"))
      (node (ref "R65") (pin "1") (pinfunction "1_1") (pintype "passive"))
      (node (ref "R66A") (pin "2") (pinfunction "2_2") (pintype "passive"))
      (node (ref "R66B") (pin "2") (pinfunction "2_2") (pintype "passive"))
      (node (ref "R66C") (pin "2") (pinfunction "2_2") (pintype "passive"))
    )
    (net (code "152") (name "Net-(Q23-G)") (class "Default")
      (node (ref "Q23") (pin "1") (pinfunction "G_1") (pintype "passive"))
      (node (ref "R75") (pin "1") (pinfunction "1_1") (pintype "passive"))
      (node (ref "R77") (pin "2") (pinfunction "2_2") (pintype "passive"))
    )
    (net (code "153") (name "Net-(Q24-D)") (class "Default")
      (node (ref "Q24") (pin "3") (pinfunction "D_3") (pintype "passive"))
      (node (ref "R77") (pin "1") (pinfunction "1_1") (pintype "passive"))
    )
    (net (code "154") (name "Net-(Q24-G)") (class "Default")
      (node (ref "Q24") (pin "1") (pinfunction "G_1") (pintype "passive"))
      (node (ref "R79") (pin "2") (pinfunction "2_2") (pintype "passive"))
      (node (ref "R80") (pin "1") (pinfunction "1_1") (pintype "passive"))
    )
    (net (code "155") (name "Net-(Q33-D)") (class "Default")
      (node (ref "Q33") (pin "3") (pinfunction "D_3") (pintype "passive"))
      (node (ref "R145") (pin "2") (pinfunction "2_2") (pintype "passive"))
      (node (ref "R146") (pin "1") (pinfunction "1_1") (pintype "passive"))
      (node (ref "R147") (pin "2") (pinfunction "2_2") (pintype "passive"))
    )
    (net (code "156") (name "Net-(Q33-G)") (class "Default")
      (node (ref "Q33") (pin "1") (pinfunction "G_1") (pintype "passive"))
      (node (ref "R87") (pin "1") (pinfunction "1_1") (pintype "passive"))
    )
    (net (code "157") (name "Net-(Q100-G)") (class "Default")
      (node (ref "Q100") (pin "1") (pinfunction "G_1") (pintype "passive"))
      (node (ref "Q103") (pin "3") (pinfunction "D_3") (pintype "passive"))
      (node (ref "R112") (pin "1") (pinfunction "1_1") (pintype "passive"))
      (node (ref "R139") (pin "2") (pinfunction "2_2") (pintype "passive"))
    )
    (net (code "158") (name "Net-(Q101-G)") (class "Default")
      (node (ref "Q101") (pin "1") (pinfunction "G_1") (pintype "passive"))
      (node (ref "Q102") (pin "3") (pinfunction "D_3") (pintype "passive"))
      (node (ref "R135") (pin "2") (pinfunction "2_2") (pintype "passive"))
      (node (ref "R137") (pin "2") (pinfunction "2_2") (pintype "passive"))
    )
    (net (code "159") (name "Net-(Q102-G)") (class "Default")
      (node (ref "Q102") (pin "1") (pinfunction "G_1") (pintype "passive"))
      (node (ref "R110") (pin "1") (pinfunction "1_1") (pintype "passive"))
      (node (ref "R111") (pin "1") (pinfunction "1_1") (pintype "passive"))
    )
    (net (code "160") (name "Net-(Q103-G)") (class "Default")
      (node (ref "Q103") (pin "1") (pinfunction "G_1") (pintype "passive"))
      (node (ref "R105") (pin "1") (pinfunction "1_1") (pintype "passive"))
      (node (ref "R113") (pin "1") (pinfunction "1_1") (pintype "passive"))
    )
    (net (code "161") (name "Net-(R18-Pad1)") (class "Default")
      (node (ref "R18") (pin "1") (pinfunction "1_1") (pintype "passive"))
      (node (ref "R19") (pin "2") (pinfunction "2_2") (pintype "passive"))
    )
    (net (code "162") (name "Net-(R121-Pad2)") (class "Default")
      (node (ref "R121") (pin "2") (pinfunction "2_2") (pintype "passive"))
      (node (ref "TP115") (pin "1") (pinfunction "1_1") (pintype "passive"))
    )
    (net (code "163") (name "Net-(R122-Pad1)") (class "Default")
      (node (ref "R122") (pin "1") (pinfunction "1_1") (pintype "passive"))
      (node (ref "TP118") (pin "1") (pinfunction "1_1") (pintype "passive"))
    )
    (net (code "164") (name "Net-(R130-Pad2)") (class "Default")
      (node (ref "R130") (pin "2") (pinfunction "2_2") (pintype "passive"))
      (node (ref "TP121") (pin "1") (pinfunction "1_1") (pintype "passive"))
    )
    (net (code "165") (name "Net-(R131-Pad2)") (class "Default")
      (node (ref "R131") (pin "2") (pinfunction "2_2") (pintype "passive"))
      (node (ref "TP122") (pin "1") (pinfunction "1_1") (pintype "passive"))
    )
    (net (code "166") (name "Net-(R134-Pad2)") (class "Default")
      (node (ref "R134") (pin "2") (pinfunction "2_2") (pintype "passive"))
      (node (ref "U104") (pin "6") (pinfunction "OUT_6") (pintype "passive"))
      (node (ref "U104") (pin "7") (pinfunction "OUT_7") (pintype "passive"))
    )
    (net (code "167") (name "Net-(R138-Pad2)") (class "Default")
      (node (ref "R138") (pin "2") (pinfunction "2_2") (pintype "passive"))
      (node (ref "R139") (pin "1") (pinfunction "1_1") (pintype "passive"))
    )
    (net (code "168") (name "Net-(U1-CT1)") (class "Default")
      (node (ref "C11") (pin "1") (pinfunction "1_1") (pintype "passive"))
      (node (ref "U1") (pin "10") (pinfunction "CT1_10") (pintype "passive"))
    )
    (net (code "169") (name "Net-(U1-CTLT)") (class "Default")
      (node (ref "C10") (pin "1") (pinfunction "1_1") (pintype "passive"))
      (node (ref "U1") (pin "8") (pinfunction "CTLT_8") (pintype "passive"))
    )
    (net (code "170") (name "Net-(U1-Cout)") (class "Default")
      (node (ref "R142") (pin "1") (pinfunction "1_1") (pintype "passive"))
      (node (ref "R26") (pin "2") (pinfunction "2_2") (pintype "passive"))
      (node (ref "U1") (pin "3") (pinfunction "Cout_3") (pintype "passive"))
    )
    (net (code "171") (name "Net-(U1-Dout)") (class "Default")
      (node (ref "R25") (pin "2") (pinfunction "2_2") (pintype "passive"))
      (node (ref "U1") (pin "6") (pinfunction "Dout_6") (pintype "passive"))
    )
    (net (code "172") (name "Net-(U2A-IN1-)") (class "Default")
      (node (ref "C16") (pin "1") (pinfunction "1_1") (pintype "passive"))
      (node (ref "R11") (pin "1") (pinfunction "1_1") (pintype "passive"))
      (node (ref "R28") (pin "2") (pinfunction "2_2") (pintype "passive"))
      (node (ref "R29") (pin "2") (pinfunction "2_2") (pintype "passive"))
      (node (ref "U2") (pin "10") (pinfunction "IN4-_10") (pintype "input"))
      (node (ref "U2") (pin "4") (pinfunction "IN1-_4") (pintype "input"))
      (node (ref "U2") (pin "6") (pinfunction "IN2-_6") (pintype "input"))
      (node (ref "U2") (pin "8") (pinfunction "IN3-_8") (pintype "input"))
    )
    (net (code "173") (name "Net-(U3-CT1)") (class "Default")
      (node (ref "C23") (pin "1") (pinfunction "1_1") (pintype "passive"))
      (node (ref "U3") (pin "10") (pinfunction "CT1_10") (pintype "passive"))
    )
    (net (code "174") (name "Net-(U3-CTLT)") (class "Default")
      (node (ref "C22") (pin "1") (pinfunction "1_1") (pintype "passive"))
      (node (ref "U3") (pin "8") (pinfunction "CTLT_8") (pintype "passive"))
    )
    (net (code "175") (name "Net-(U3-Cout)") (class "Default")
      (node (ref "R143") (pin "1") (pinfunction "1_1") (pintype "passive"))
      (node (ref "R43") (pin "2") (pinfunction "2_2") (pintype "passive"))
      (node (ref "U3") (pin "3") (pinfunction "Cout_3") (pintype "passive"))
    )
    (net (code "176") (name "Net-(U3-Dout)") (class "Default")
      (node (ref "R42") (pin "2") (pinfunction "2_2") (pintype "passive"))
      (node (ref "U3") (pin "6") (pinfunction "Dout_6") (pintype "passive"))
    )
    (net (code "177") (name "Net-(U4-B)") (class "Default")
      (node (ref "R38") (pin "1") (pinfunction "1_1") (pintype "passive"))
      (node (ref "U4") (pin "6") (pinfunction "B_6") (pintype "passive"))
    )
    (net (code "178") (name "Net-(U5-CT1)") (class "Default")
      (node (ref "C39") (pin "1") (pinfunction "1_1") (pintype "passive"))
      (node (ref "U5") (pin "10") (pinfunction "CT1_10") (pintype "passive"))
    )
    (net (code "179") (name "Net-(U5-CTLT)") (class "Default")
      (node (ref "C38") (pin "1") (pinfunction "1_1") (pintype "passive"))
      (node (ref "U5") (pin "8") (pinfunction "CTLT_8") (pintype "passive"))
    )
    (net (code "180") (name "Net-(U5-Cout)") (class "Default")
      (node (ref "R144") (pin "1") (pinfunction "1_1") (pintype "passive"))
      (node (ref "R71") (pin "2") (pinfunction "2_2") (pintype "passive"))
      (node (ref "U5") (pin "3") (pinfunction "Cout_3") (pintype "passive"))
    )
    (net (code "181") (name "Net-(U5-Dout)") (class "Default")
      (node (ref "R70") (pin "2") (pinfunction "2_2") (pintype "passive"))
      (node (ref "U5") (pin "6") (pinfunction "Dout_6") (pintype "passive"))
    )
    (net (code "182") (name "Net-(U6-P3{slash}SDA)") (class "Default")
      (node (ref "R119") (pin "2") (pinfunction "2_2") (pintype "passive"))
      (node (ref "U6") (pin "14") (pinfunction "P3/SDA_14") (pintype "passive"))
    )
    (net (code "183") (name "Net-(U6-P4{slash}SCL)") (class "Default")
      (node (ref "R120") (pin "2") (pinfunction "2_2") (pintype "passive"))
      (node (ref "U6") (pin "13") (pinfunction "P4/SCL_13") (pintype "input"))
    )
    (net (code "184") (name "Net-(U6-P5{slash}HDQ)") (class "Default")
      (node (ref "R56") (pin "2") (pinfunction "2_2") (pintype "passive"))
      (node (ref "U6") (pin "12") (pinfunction "P5/HDQ_12") (pintype "passive"))
    )
    (net (code "185") (name "Net-(U6-SRN)") (class "Default")
      (node (ref "C28") (pin "2") (pinfunction "2_2") (pintype "passive"))
      (node (ref "C32") (pin "2") (pinfunction "2_2") (pintype "passive"))
      (node (ref "R57") (pin "2") (pinfunction "2_2") (pintype "passive"))
      (node (ref "U6") (pin "10") (pinfunction "SRN_10") (pintype "input"))
    )
    (net (code "186") (name "Net-(U6-SRP)") (class "Default")
      (node (ref "C28") (pin "1") (pinfunction "1_1") (pintype "passive"))
      (node (ref "C31") (pin "1") (pinfunction "1_1") (pintype "passive"))
      (node (ref "R61") (pin "2") (pinfunction "2_2") (pintype "passive"))
      (node (ref "U6") (pin "9") (pinfunction "SRP_9") (pintype "input"))
    )
    (net (code "187") (name "Net-(U7-CT1)") (class "Default")
      (node (ref "C45") (pin "1") (pinfunction "1_1") (pintype "passive"))
      (node (ref "U7") (pin "10") (pinfunction "CT1_10") (pintype "passive"))
    )
    (net (code "188") (name "Net-(U7-CT2)") (class "Default")
      (node (ref "C47") (pin "1") (pinfunction "1_1") (pintype "passive"))
      (node (ref "U7") (pin "11") (pinfunction "CT2_11") (pintype "passive"))
    )
    (net (code "189") (name "Net-(U7-CTLT)") (class "Default")
      (node (ref "C46") (pin "1") (pinfunction "1_1") (pintype "passive"))
      (node (ref "U7") (pin "8") (pinfunction "CTLT_8") (pintype "passive"))
    )
    (net (code "190") (name "Net-(U101-VDD)") (class "Default")
      (node (ref "C102") (pin "1") (pinfunction "1_1") (pintype "passive"))
      (node (ref "C103") (pin "2") (pinfunction "2_2") (pintype "passive"))
      (node (ref "R106") (pin "2") (pinfunction "2_2") (pintype "passive"))
      (node (ref "U101") (pin "16") (pinfunction "VDD_16") (pintype "passive"))
    )
    (net (code "191") (name "Net-(U102-WP)") (class "Default")
      (node (ref "R104") (pin "2") (pinfunction "2_2") (pintype "passive"))
      (node (ref "U102") (pin "5") (pinfunction "WP_5") (pintype "passive"))
    )
    (net (code "192") (name "Net-(U103-EN)") (class "Default")
      (node (ref "R125") (pin "1") (pinfunction "1_1") (pintype "passive"))
      (node (ref "U103") (pin "3") (pinfunction "EN_3") (pintype "passive"))
    )
    (net (code "193") (name "Net-(U103-IN)") (class "Default")
      (node (ref "R110") (pin "2") (pinfunction "2_2") (pintype "passive"))
      (node (ref "U103") (pin "2") (pinfunction "IN_2") (pintype "passive"))
      (node (ref "U7") (pin "6") (pinfunction "Dout_6") (pintype "passive"))
    )
    (net (code "194") (name "Net-(U104-EN)") (class "Default")
      (node (ref "R129") (pin "1") (pinfunction "1_1") (pintype "passive"))
      (node (ref "U104") (pin "3") (pinfunction "EN_3") (pintype "passive"))
    )
    (net (code "195") (name "P3V3") (class "Default")
      (node (ref "C100") (pin "1") (pinfunction "1_1") (pintype "passive"))
      (node (ref "C105") (pin "2") (pinfunction "2_2") (pintype "passive"))
      (node (ref "R101") (pin "1") (pinfunction "1_1") (pintype "passive"))
      (node (ref "R103") (pin "1") (pinfunction "1_1") (pintype "passive"))
      (node (ref "R106") (pin "1") (pinfunction "1_1") (pintype "passive"))
      (node (ref "R109") (pin "2") (pinfunction "2_2") (pintype "passive"))
      (node (ref "R11") (pin "2") (pinfunction "2_2") (pintype "passive"))
      (node (ref "R112") (pin "2") (pinfunction "2_2") (pintype "passive"))
      (node (ref "R114") (pin "2") (pinfunction "2_2") (pintype "passive"))
      (node (ref "R117") (pin "2") (pinfunction "2_2") (pintype "passive"))
      (node (ref "R118") (pin "2") (pinfunction "2_2") (pintype "passive"))
      (node (ref "R12") (pin "2") (pinfunction "2_2") (pintype "passive"))
      (node (ref "R13") (pin "2") (pinfunction "2_2") (pintype "passive"))
      (node (ref "R135") (pin "1") (pinfunction "1_1") (pintype "passive"))
      (node (ref "R14") (pin "2") (pinfunction "2_2") (pintype "passive"))
      (node (ref "R15") (pin "2") (pinfunction "2_2") (pintype "passive"))
      (node (ref "TP104") (pin "1") (pinfunction "1_1") (pintype "passive"))
      (node (ref "U100") (pin "3") (pinfunction "OUT_3") (pintype "passive"))
      (node (ref "U102") (pin "4") (pinfunction "Vcc_4") (pintype "passive"))
    )
    (net (code "196") (name "unconnected-(P1-Pad9)") (class "Default")
      (node (ref "P1") (pin "9") (pinfunction "9_9") (pintype "passive+no_connect"))
    )
    (net (code "197") (name "unconnected-(P1-Pad10)") (class "Default")
      (node (ref "P1") (pin "10") (pinfunction "10_10") (pintype "passive+no_connect"))
    )
    (net (code "198") (name "unconnected-(P1-Pad18)") (class "Default")
      (node (ref "P1") (pin "18") (pinfunction "18_18") (pintype "passive+no_connect"))
    )
    (net (code "199") (name "unconnected-(P1-Pad19)") (class "Default")
      (node (ref "P1") (pin "19") (pinfunction "19_19") (pintype "passive+no_connect"))
    )
    (net (code "200") (name "unconnected-(P1-Pad28)") (class "Default")
      (node (ref "P1") (pin "28") (pinfunction "28_28") (pintype "passive"))
    )
    (net (code "201") (name "unconnected-(P1-Pad29)") (class "Default")
      (node (ref "P1") (pin "29") (pinfunction "29_29") (pintype "passive"))
    )
    (net (code "202") (name "unconnected-(P1-Pad30)") (class "Default")
      (node (ref "P1") (pin "30") (pinfunction "30_30") (pintype "passive+no_connect"))
    )
    (net (code "203") (name "unconnected-(P2-Pad25)") (class "Default")
      (node (ref "P2") (pin "25") (pinfunction "25_25") (pintype "passive+no_connect"))
    )
    (net (code "204") (name "unconnected-(P2-Pad26)") (class "Default")
      (node (ref "P2") (pin "26") (pinfunction "26_26") (pintype "passive+no_connect"))
    )
    (net (code "205") (name "unconnected-(P100-CLK-Pad1)") (class "Default")
      (node (ref "P100") (pin "1") (pinfunction "CLK_1") (pintype "passive"))
    )
    (net (code "206") (name "unconnected-(P100-CLK_GND-Pad2)") (class "Default")
      (node (ref "P100") (pin "2") (pinfunction "CLK_GND_2") (pintype "passive"))
    )
    (net (code "207") (name "unconnected-(P100-DATA-Pad4)") (class "Default")
      (node (ref "P100") (pin "4") (pinfunction "DATA_4") (pintype "passive"))
    )
    (net (code "208") (name "unconnected-(P100-DATA_GND-Pad3)") (class "Default")
      (node (ref "P100") (pin "3") (pinfunction "DATA_GND_3") (pintype "passive"))
    )
    (net (code "209") (name "unconnected-(P100-ENABLE-Pad8)") (class "Default")
      (node (ref "P100") (pin "8") (pinfunction "ENABLE_8") (pintype "passive"))
    )
    (net (code "210") (name "unconnected-(P100-ENABLE_RTN-Pad7)") (class "Default")
      (node (ref "P100") (pin "7") (pinfunction "ENABLE_RTN_7") (pintype "passive"))
    )
    (net (code "211") (name "unconnected-(P100-NU-Pad5)") (class "Default")
      (node (ref "P100") (pin "5") (pinfunction "NU_5") (pintype "passive"))
    )
    (net (code "212") (name "unconnected-(P100-NU-Pad6)") (class "Default")
      (node (ref "P100") (pin "6") (pinfunction "NU_6") (pintype "passive"))
    )
    (net (code "213") (name "unconnected-(U1-CB5-Pad14)") (class "Default")
      (node (ref "U1") (pin "14") (pinfunction "CB5_14") (pintype "passive+no_connect"))
    )
    (net (code "214") (name "unconnected-(U1-DRAIN-Pad5)") (class "Default")
      (node (ref "U1") (pin "5") (pinfunction "DRAIN_5") (pintype "passive+no_connect"))
    )
    (net (code "215") (name "unconnected-(U3-CB5-Pad14)") (class "Default")
      (node (ref "U3") (pin "14") (pinfunction "CB5_14") (pintype "passive+no_connect"))
    )
    (net (code "216") (name "unconnected-(U3-DRAIN-Pad5)") (class "Default")
      (node (ref "U3") (pin "5") (pinfunction "DRAIN_5") (pintype "passive+no_connect"))
    )
    (net (code "217") (name "unconnected-(U4-NC-Pad3)") (class "Default")
      (node (ref "U4") (pin "3") (pinfunction "NC_3") (pintype "passive"))
    )
    (net (code "218") (name "unconnected-(U5-CB5-Pad14)") (class "Default")
      (node (ref "U5") (pin "14") (pinfunction "CB5_14") (pintype "passive+no_connect"))
    )
    (net (code "219") (name "unconnected-(U5-DRAIN-Pad5)") (class "Default")
      (node (ref "U5") (pin "5") (pinfunction "DRAIN_5") (pintype "passive+no_connect"))
    )
    (net (code "220") (name "unconnected-(U7-CB5-Pad14)") (class "Default")
      (node (ref "U7") (pin "14") (pinfunction "CB5_14") (pintype "passive+no_connect"))
    )
    (net (code "221") (name "unconnected-(U100-NC-Pad4)") (class "Default")
      (node (ref "U100") (pin "4") (pinfunction "NC_4") (pintype "passive+no_connect"))
    )
    (net (code "222") (name "unconnected-(U101-NC-Pad2)") (class "Default")
      (node (ref "U101") (pin "2") (pinfunction "NC_2") (pintype "passive+no_connect"))
    )
    (net (code "223") (name "unconnected-(U101-NC-Pad3)") (class "Default")
      (node (ref "U101") (pin "3") (pinfunction "NC_3") (pintype "passive+no_connect"))
    )
    (net (code "224") (name "unconnected-(U101-NC-Pad4)") (class "Default")
      (node (ref "U101") (pin "4") (pinfunction "NC_4") (pintype "passive+no_connect"))
    )
  )
)
